# Raspberry_Pi_Circuit_Board.net
KiCad netlist of a schematic drawn in EAGLE
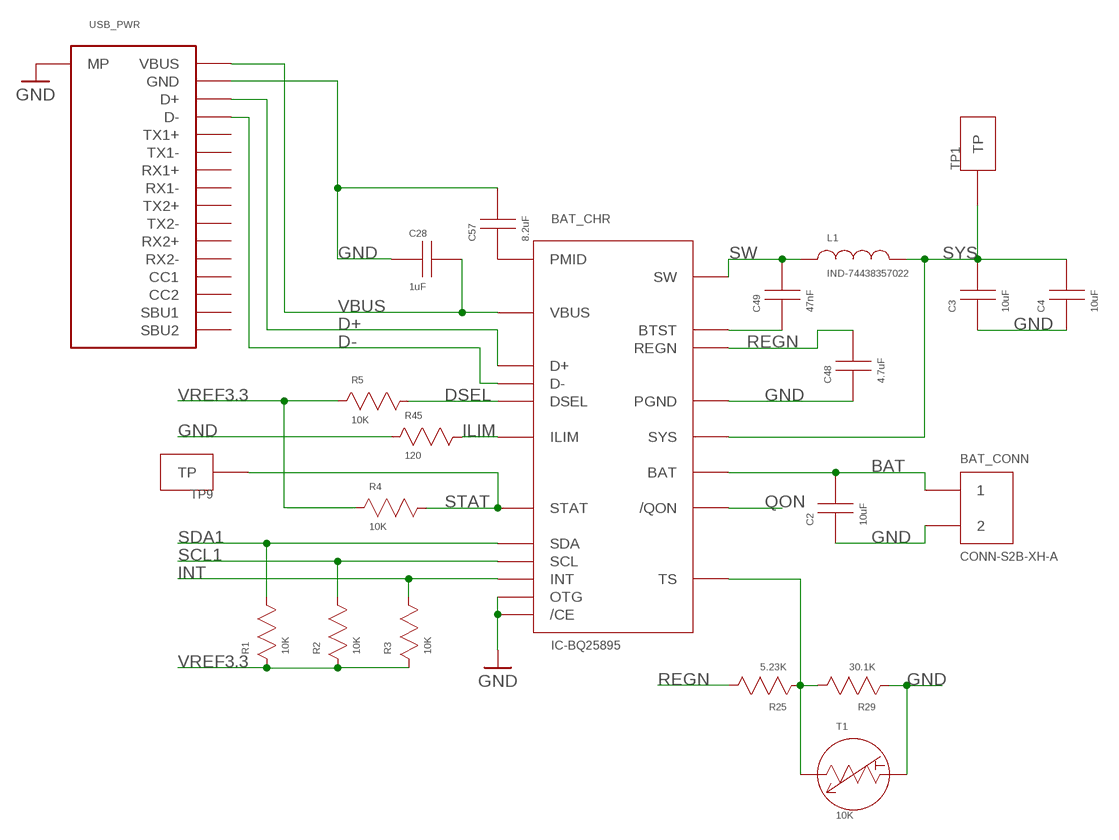
[diagram p0: schematic, sheet 1]
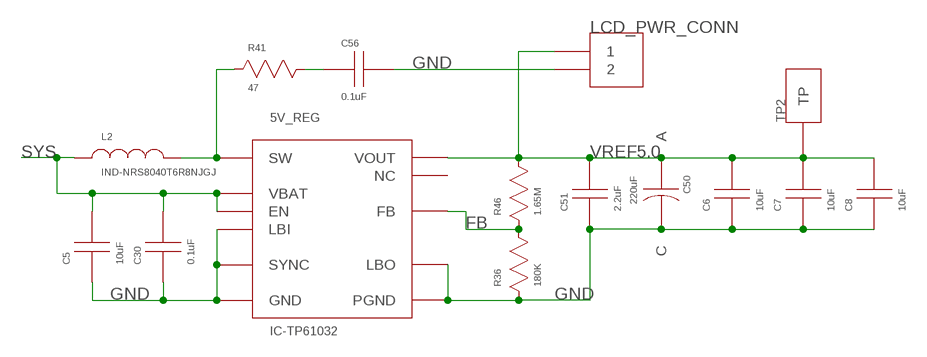
[diagram p1: schematic, sheet 2]
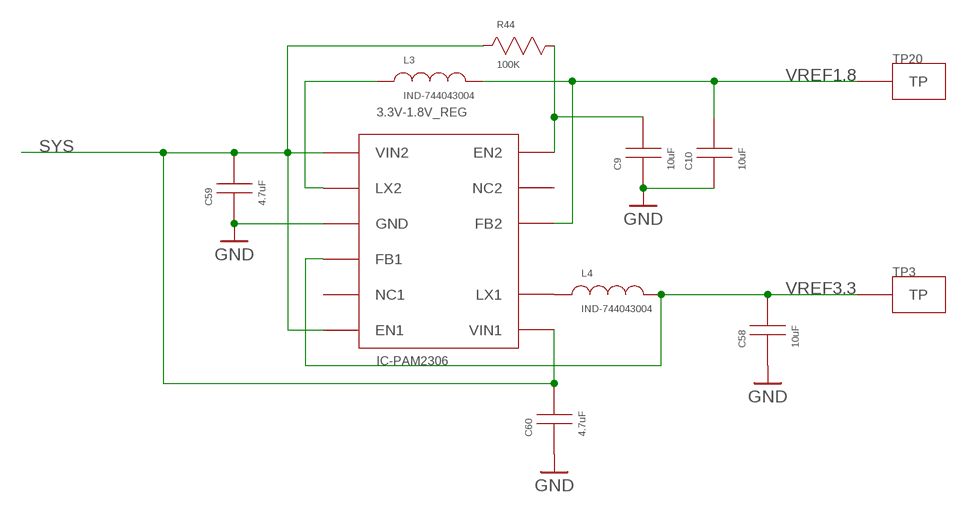
[diagram p2: schematic, sheet 3]
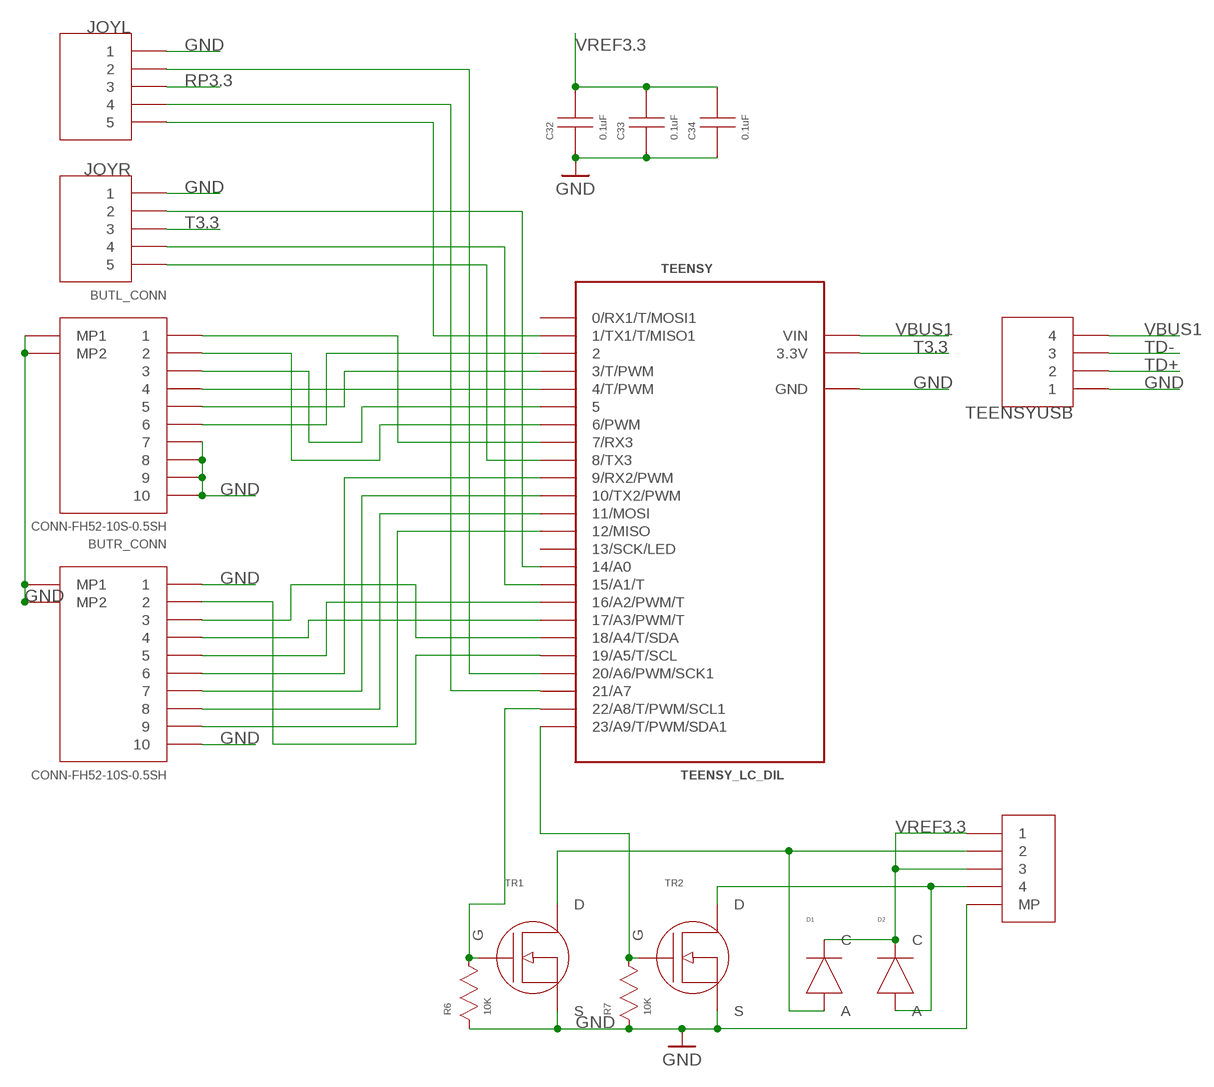
[diagram p3: schematic, sheet 4]
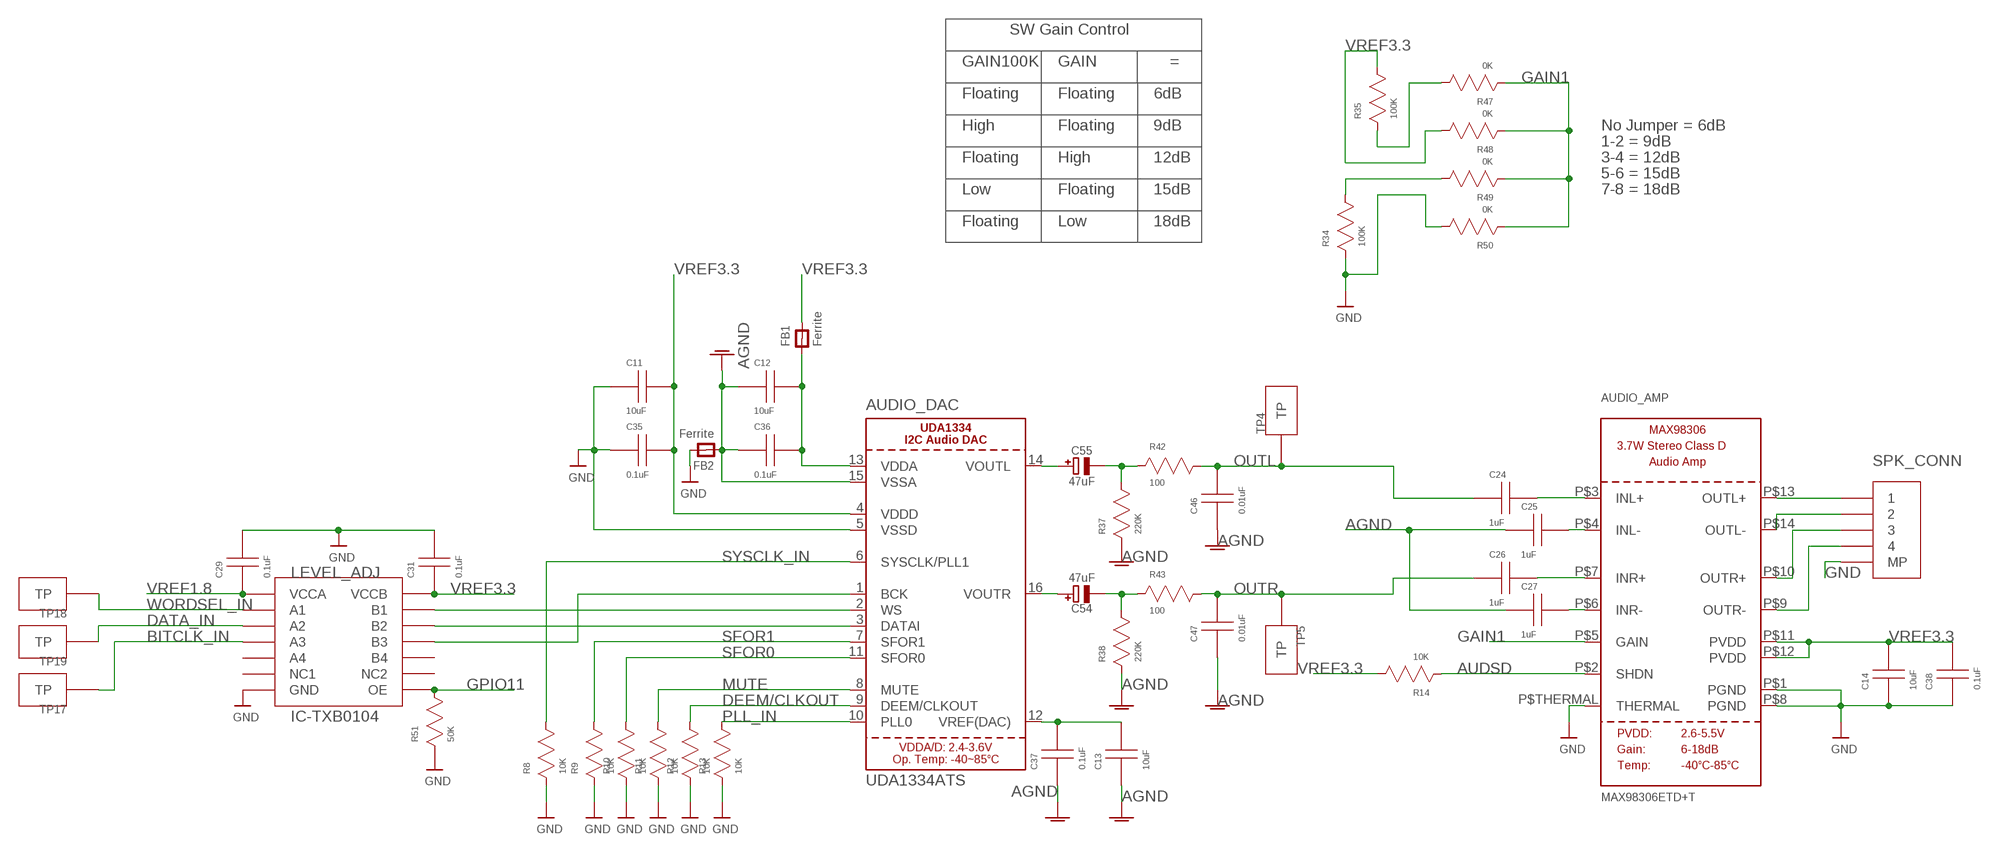
[diagram p4: schematic, sheet 5]
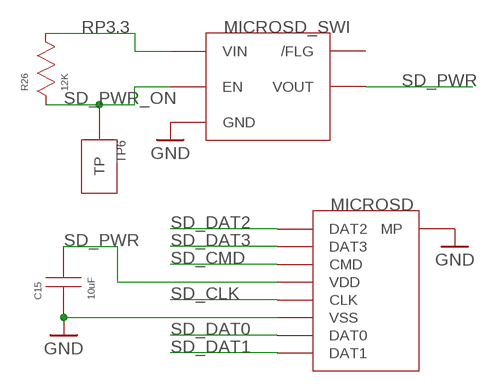
[diagram p5: schematic, sheet 6]
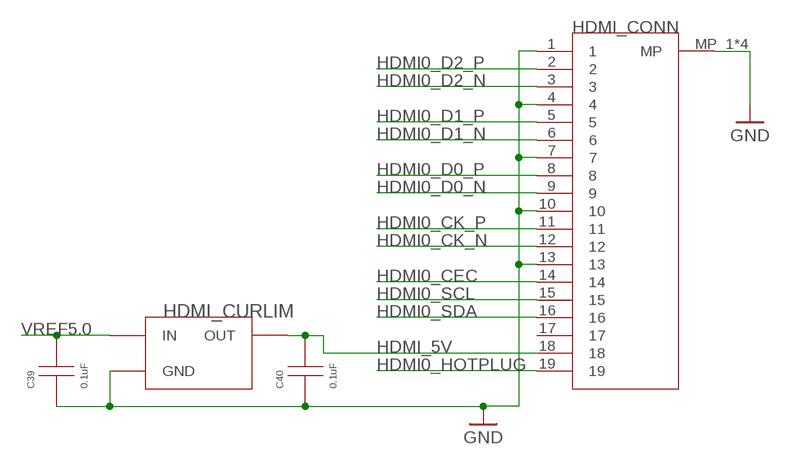
[diagram p6: schematic, sheet 7]
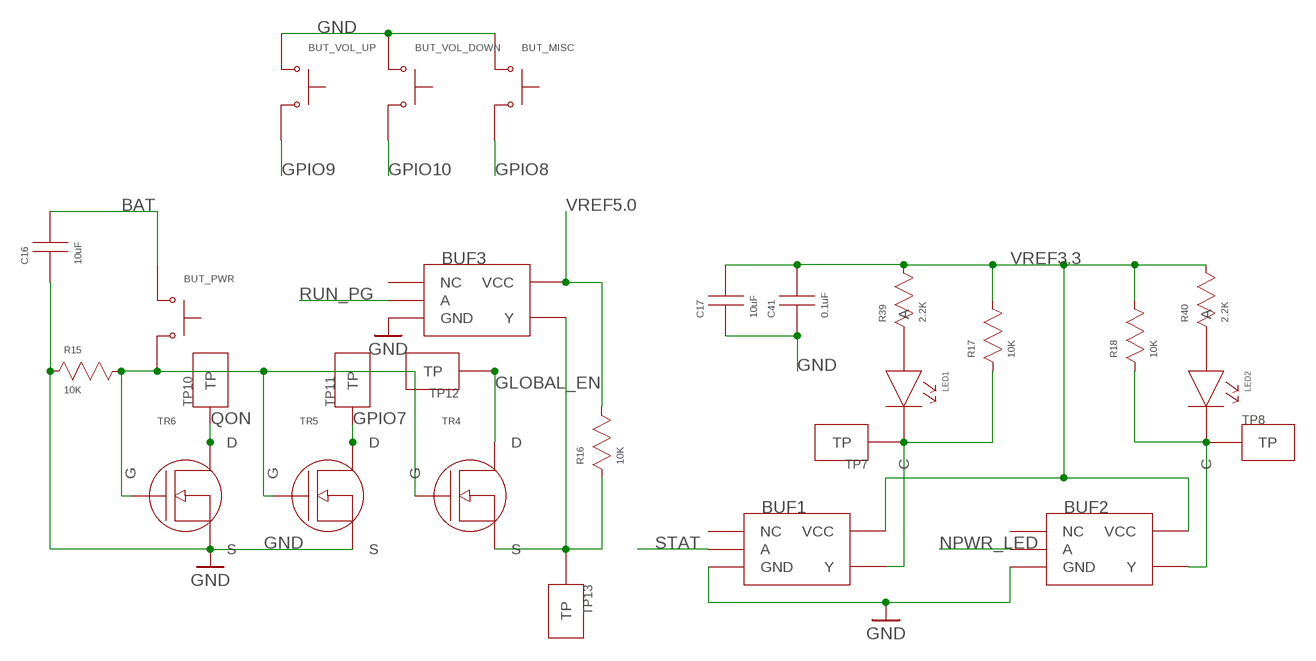
[diagram p7: schematic, sheet 8]
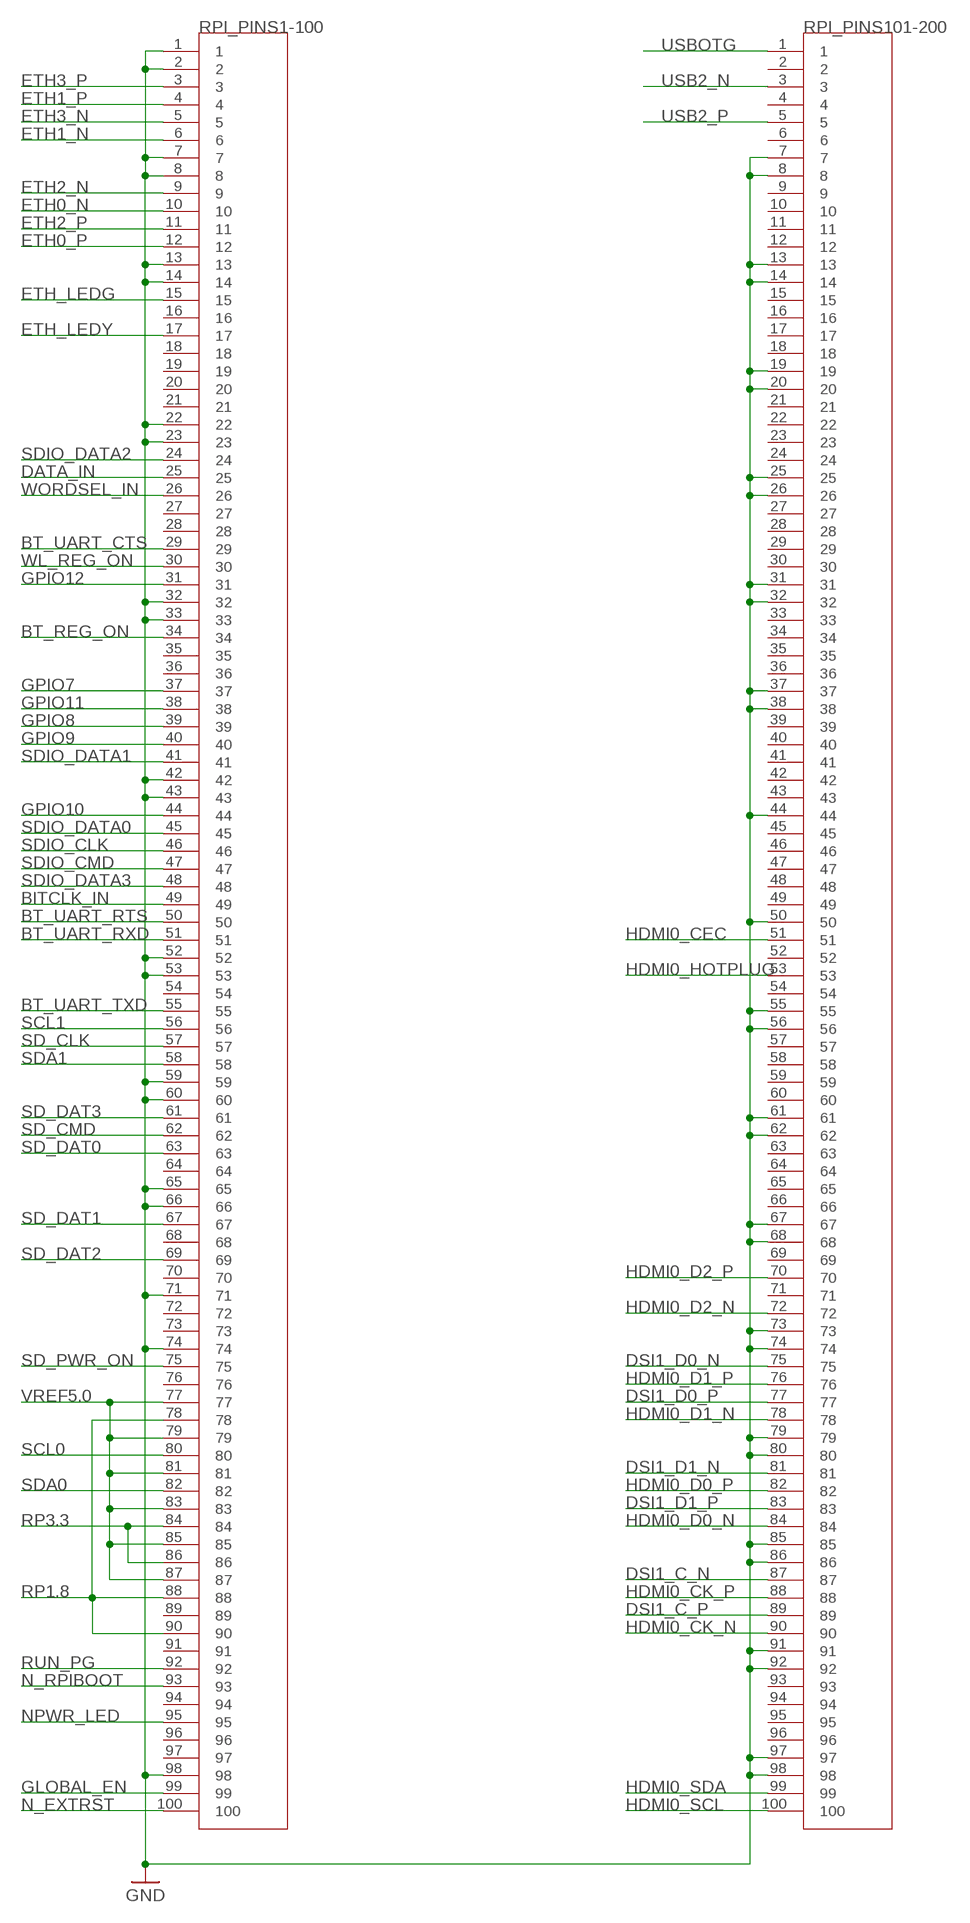
[diagram p8: schematic, sheet 9]
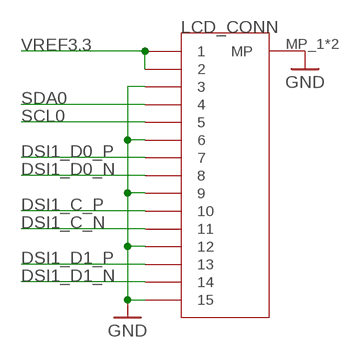
[diagram p9: schematic, sheet 10]
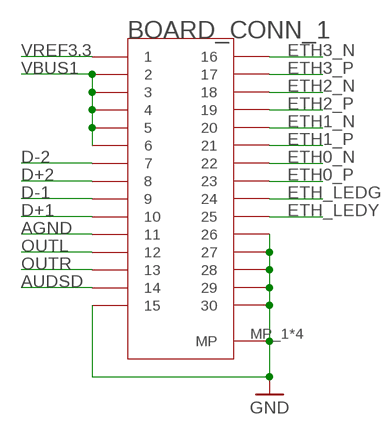
[diagram p10: schematic, sheet 11]
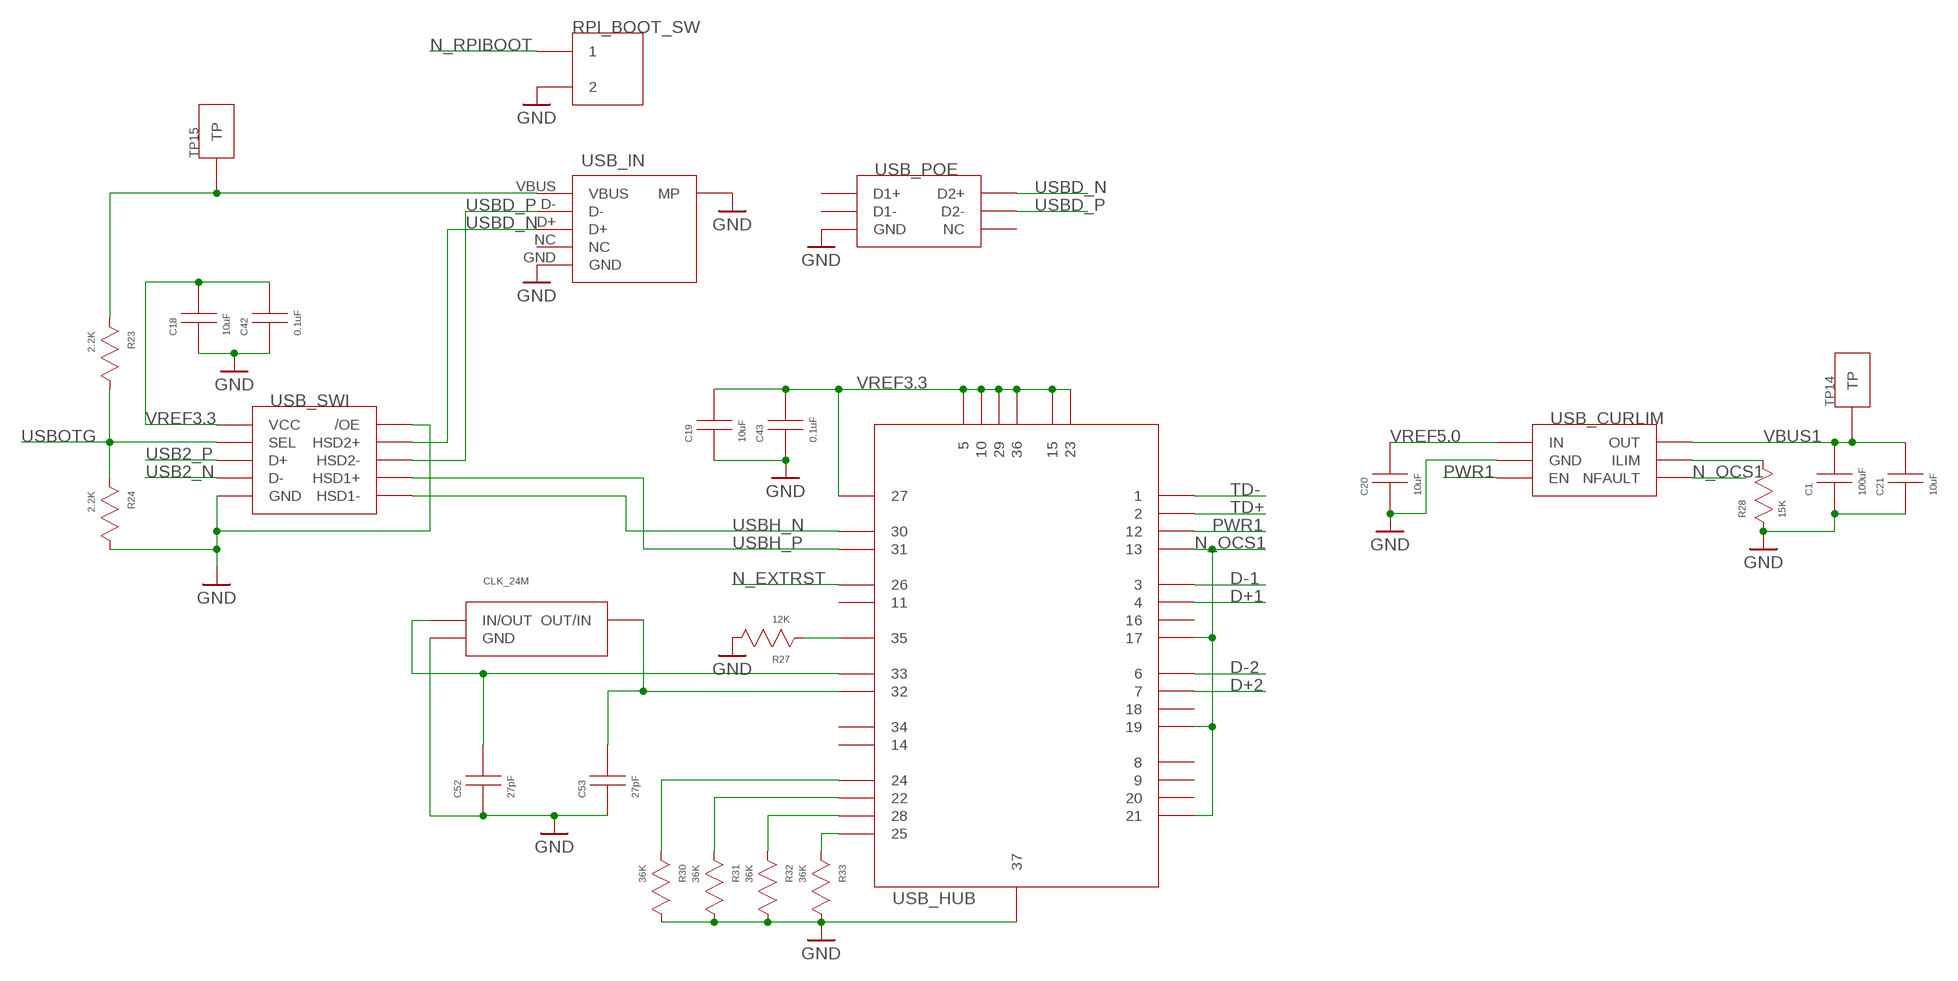
[diagram p11: schematic, sheet 12]
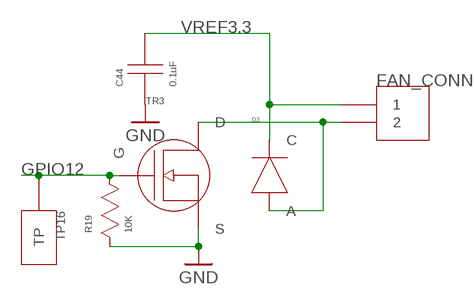
[diagram p12: schematic, sheet 13]
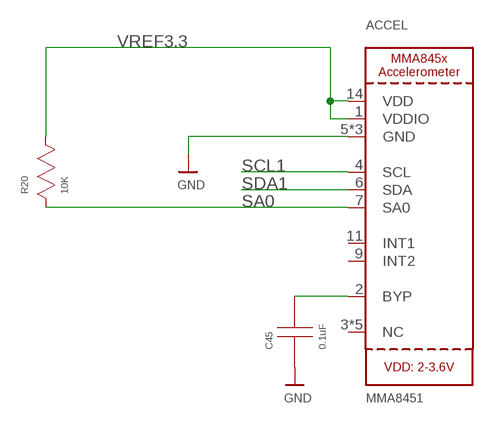
[diagram p13: schematic, sheet 14]
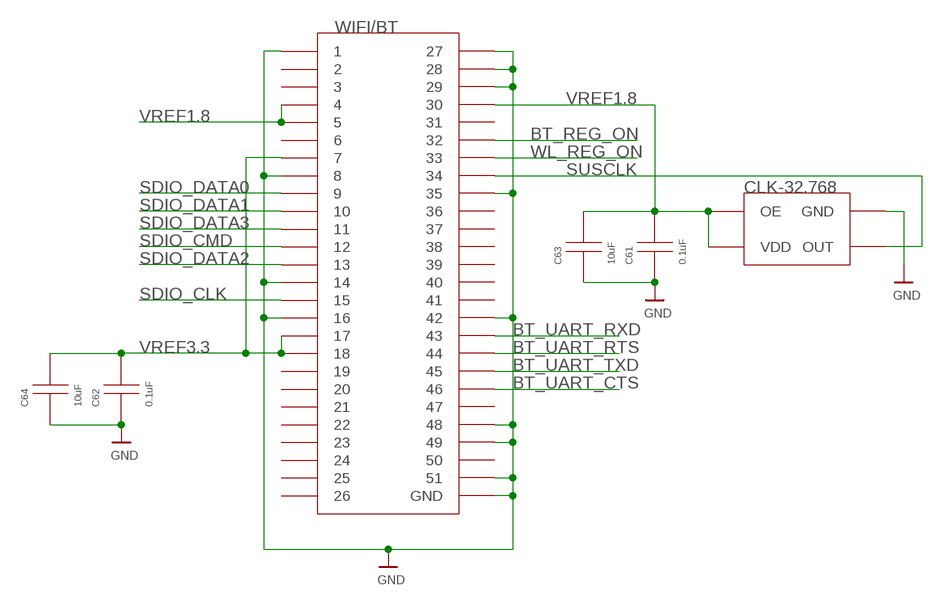
[diagram p14: schematic, sheet 15]

(export (version "E")
  (design (tool "Eeschema 10.0.6"))
  (components
    (comp (ref "C39")
      (value "0.1uF")
      (footprint "eagle-import:CAP-603")
      (libsource (lib "eagle-import") (part "CAP-603"))
    )
    (comp (ref "C40")
      (value "0.1uF")
      (footprint "eagle-import:CAP-603")
      (libsource (lib "eagle-import") (part "CAP-603"))
    )
    (comp (ref "HDMI_CONN")
      (value "HDMI-2001-1-2-21-00-BK")
      (footprint "eagle-import:HDMI-2001-1-2-21-00-BK")
      (libsource (lib "eagle-import") (part "HDMI-2001-1-2-21-00-BK"))
    )
    (comp (ref "HDMI_CURLIM")
      (value "CURLIM-AP2331")
      (footprint "eagle-import:CURLIM-AP2331")
      (libsource (lib "eagle-import") (part "CURLIM-AP2331"))
    )
    (comp (ref "RPI_PINS1-100")
      (value "CONN-DF40_CL0594-5437-8-00_2D")
      (footprint "eagle-import:CONN-DF40_CL0594-5437-8-00_2D")
      (libsource (lib "eagle-import") (part "CONN-DF40_CL0594-5437-8-00_2D"))
    )
    (comp (ref "RPI_PINS101-200")
      (value "CONN-DF40_CL0594-5437-8-00_2D")
      (footprint "eagle-import:CONN-DF40_CL0594-5437-8-00_2D")
      (libsource (lib "eagle-import") (part "CONN-DF40_CL0594-5437-8-00_2D"))
    )
    (comp (ref "BOARD_CONN_1")
      (value "MEZZANINE-AXT630124")
      (footprint "eagle-import:MEZZANINE-AXT630124")
      (libsource (lib "eagle-import") (part "MEZZANINE-AXT630124"))
    )
    (comp (ref "BUF1")
      (value "BUF-74LVC1G07")
      (footprint "eagle-import:BUF-74LVC1G07")
      (libsource (lib "eagle-import") (part "BUF-74LVC1G07"))
    )
    (comp (ref "BUF2")
      (value "BUF-74LVC1G07")
      (footprint "eagle-import:BUF-74LVC1G07")
      (libsource (lib "eagle-import") (part "BUF-74LVC1G07"))
    )
    (comp (ref "BUF3")
      (value "BUF-74LVC1G07")
      (footprint "eagle-import:BUF-74LVC1G07")
      (libsource (lib "eagle-import") (part "BUF-74LVC1G07"))
    )
    (comp (ref "BUT_MISC")
      (value "BUT-KSS331GLFS")
      (footprint "eagle-import:BUT-KSS331GLFS")
      (libsource (lib "eagle-import") (part "BUT-KSS331GLFS"))
    )
    (comp (ref "BUT_PWR")
      (value "BUT-KSS331GLFS")
      (footprint "eagle-import:BUT-KSS331GLFS")
      (libsource (lib "eagle-import") (part "BUT-KSS331GLFS"))
    )
    (comp (ref "BUT_VOL_DOWN")
      (value "BUT-KSS331GLFS")
      (footprint "eagle-import:BUT-KSS331GLFS")
      (libsource (lib "eagle-import") (part "BUT-KSS331GLFS"))
    )
    (comp (ref "BUT_VOL_UP")
      (value "BUT-KSS331GLFS")
      (footprint "eagle-import:BUT-KSS331GLFS")
      (libsource (lib "eagle-import") (part "BUT-KSS331GLFS"))
    )
    (comp (ref "C16")
      (value "10uF")
      (footprint "eagle-import:CAP-603")
      (libsource (lib "eagle-import") (part "Personal_vf.c4yF0r8uTPqxhtoqvO0ekg_CAP-603"))
    )
    (comp (ref "C17")
      (value "10uF")
      (footprint "eagle-import:CAP-603")
      (libsource (lib "eagle-import") (part "Personal_vf.c4yF0r8uTPqxhtoqvO0ekg_CAP-603"))
    )
    (comp (ref "C41")
      (value "0.1uF")
      (footprint "eagle-import:CAP-603")
      (libsource (lib "eagle-import") (part "Personal_vf.c4yF0r8uTPqxhtoqvO0ekg_CAP-603"))
    )
    (comp (ref "LED1")
      (value "LED-SM0805UWC")
      (footprint "eagle-import:LED-SM0805UWC")
      (libsource (lib "eagle-import") (part "LED-SM0805UWC"))
    )
    (comp (ref "LED2")
      (value "LED-SM0805UWC")
      (footprint "eagle-import:LED-SM0805UWC")
      (libsource (lib "eagle-import") (part "LED-SM0805UWC"))
    )
    (comp (ref "R15")
      (value "10K")
      (footprint "eagle-import:RES-603")
      (libsource (lib "eagle-import") (part "Personal_vf.c4yF0r8uTPqxhtoqvO0ekg_RES-603"))
    )
    (comp (ref "R16")
      (value "10K")
      (footprint "eagle-import:RES-603")
      (libsource (lib "eagle-import") (part "Personal_vf.c4yF0r8uTPqxhtoqvO0ekg_RES-603"))
    )
    (comp (ref "R17")
      (value "10K")
      (footprint "eagle-import:RES-603")
      (libsource (lib "eagle-import") (part "RES-603"))
    )
    (comp (ref "R18")
      (value "10K")
      (footprint "eagle-import:RES-603")
      (libsource (lib "eagle-import") (part "RES-603"))
    )
    (comp (ref "R39")
      (value "2.2K")
      (footprint "eagle-import:RES-603")
      (libsource (lib "eagle-import") (part "RES-603"))
    )
    (comp (ref "R40")
      (value "2.2K")
      (footprint "eagle-import:RES-603")
      (libsource (lib "eagle-import") (part "RES-603"))
    )
    (comp (ref "TP7")
      (value "TESTPOINT")
      (footprint "eagle-import:TESTPOINT")
      (libsource (lib "eagle-import") (part "TESTPOINT"))
    )
    (comp (ref "TP8")
      (value "TESTPOINT")
      (footprint "eagle-import:TESTPOINT")
      (libsource (lib "eagle-import") (part "TESTPOINT"))
    )
    (comp (ref "TP10")
      (value "TESTPOINT")
      (footprint "eagle-import:TESTPOINT")
      (libsource (lib "eagle-import") (part "TESTPOINT"))
    )
    (comp (ref "TP11")
      (value "TESTPOINT")
      (footprint "eagle-import:TESTPOINT")
      (libsource (lib "eagle-import") (part "TESTPOINT"))
    )
    (comp (ref "TP12")
      (value "TESTPOINT")
      (footprint "eagle-import:TESTPOINT")
      (libsource (lib "eagle-import") (part "TESTPOINT"))
    )
    (comp (ref "TP13")
      (value "TESTPOINT")
      (footprint "eagle-import:TESTPOINT")
      (libsource (lib "eagle-import") (part "TESTPOINT"))
    )
    (comp (ref "TR4")
      (value "TRAN-DMG2302UKQ")
      (footprint "eagle-import:TRAN-DMG2302UKQ")
      (libsource (lib "eagle-import") (part "TRAN-DMG2302UKQ"))
    )
    (comp (ref "TR5")
      (value "TRAN-DMG2302UKQ")
      (footprint "eagle-import:TRAN-DMG2302UKQ")
      (libsource (lib "eagle-import") (part "TRAN-DMG2302UKQ"))
    )
    (comp (ref "TR6")
      (value "TRAN-DMG2302UKQ")
      (footprint "eagle-import:TRAN-DMG2302UKQ")
      (libsource (lib "eagle-import") (part "TRAN-DMG2302UKQ"))
    )
    (comp (ref "BUTL_CONN")
      (value "CONN-FH52-10S-0.5SH")
      (footprint "eagle-import:CONN-FH52-10S-0.5SH")
      (libsource (lib "eagle-import") (part "CONN-FH52-10S-0.5SH"))
    )
    (comp (ref "BUTR_CONN")
      (value "CONN-FH52-10S-0.5SH")
      (footprint "eagle-import:CONN-FH52-10S-0.5SH")
      (libsource (lib "eagle-import") (part "CONN-FH52-10S-0.5SH"))
    )
    (comp (ref "C32")
      (value "0.1uF")
      (footprint "eagle-import:CAP-603")
      (libsource (lib "eagle-import") (part "CAP-603"))
    )
    (comp (ref "C33")
      (value "0.1uF")
      (footprint "eagle-import:CAP-603")
      (libsource (lib "eagle-import") (part "CAP-603"))
    )
    (comp (ref "C34")
      (value "0.1uF")
      (footprint "eagle-import:CAP-603")
      (libsource (lib "eagle-import") (part "CAP-603"))
    )
    (comp (ref "D1")
      (value "DIODE-X3-WLB1608-2")
      (footprint "eagle-import:DIODE-X3-WLB1608-2")
      (libsource (lib "eagle-import") (part "DIODE-X3-WLB1608-2"))
    )
    (comp (ref "D2")
      (value "DIODE-X3-WLB1608-2")
      (footprint "eagle-import:DIODE-X3-WLB1608-2")
      (libsource (lib "eagle-import") (part "DIODE-X3-WLB1608-2"))
    )
    (comp (ref "JOYL")
      (value "CONN_5PIN")
      (footprint "eagle-import:CONN_5PIN")
      (libsource (lib "eagle-import") (part "CONN_5PIN"))
    )
    (comp (ref "JOYR")
      (value "CONN_5PIN")
      (footprint "eagle-import:CONN_5PIN")
      (libsource (lib "eagle-import") (part "CONN_5PIN"))
    )
    (comp (ref "MOT_CONN")
      (value "CONN-VS4B-ZR-SM4A-TF")
      (footprint "eagle-import:CONN-VS4B-ZR-SM4A-TF")
      (libsource (lib "eagle-import") (part "CONN-VS4B-ZR-SM4A-TF"))
    )
    (comp (ref "R6")
      (value "10K")
      (footprint "eagle-import:RES-603")
      (libsource (lib "eagle-import") (part "Personal_vf.c4yF0r8uTPqxhtoqvO0ekg_RES-603"))
    )
    (comp (ref "R7")
      (value "10K")
      (footprint "eagle-import:RES-603")
      (libsource (lib "eagle-import") (part "Personal_vf.c4yF0r8uTPqxhtoqvO0ekg_RES-603"))
    )
    (comp (ref "TEENSY")
      (value "TEENSY_LC_DIL")
      (footprint "eagle-import:TEENSY_3.0-3.2&LC_DIL")
      (libsource (lib "eagle-import") (part "TEENSY_LC_DIL"))
    )
    (comp (ref "TEENSYUSB")
      (value "CONN_4PIN")
      (footprint "eagle-import:CONN_4PIN")
      (libsource (lib "eagle-import") (part "CONN_4PIN"))
    )
    (comp (ref "TR1")
      (value "TRAN-DMG2302UKQ")
      (footprint "eagle-import:TRAN-DMG2302UKQ")
      (libsource (lib "eagle-import") (part "TRAN-DMG2302UKQ"))
    )
    (comp (ref "TR2")
      (value "TRAN-DMG2302UKQ")
      (footprint "eagle-import:TRAN-DMG2302UKQ")
      (libsource (lib "eagle-import") (part "TRAN-DMG2302UKQ"))
    )
    (comp (ref "3.3V-1.8V_REG")
      (value "IC-PAM2306")
      (footprint "eagle-import:IC-PAM2306")
      (libsource (lib "eagle-import") (part "IC-PAM2306"))
    )
    (comp (ref "C9")
      (value "10uF")
      (footprint "eagle-import:CAP-603")
      (libsource (lib "eagle-import") (part "CAP-603"))
    )
    (comp (ref "C10")
      (value "10uF")
      (footprint "eagle-import:CAP-603")
      (libsource (lib "eagle-import") (part "CAP-603"))
    )
    (comp (ref "C58")
      (value "10uF")
      (footprint "eagle-import:CAP-603")
      (libsource (lib "eagle-import") (part "CAP-603"))
    )
    (comp (ref "C59")
      (value "4.7uF")
      (footprint "eagle-import:CAP-603")
      (libsource (lib "eagle-import") (part "CAP-603"))
    )
    (comp (ref "C60")
      (value "4.7uF")
      (footprint "eagle-import:CAP-603")
      (libsource (lib "eagle-import") (part "CAP-603"))
    )
    (comp (ref "L3")
      (value "IND-744043004")
      (footprint "eagle-import:IND-744043004")
      (libsource (lib "eagle-import") (part "IND-744043004"))
    )
    (comp (ref "L4")
      (value "IND-744043004")
      (footprint "eagle-import:IND-744043004")
      (libsource (lib "eagle-import") (part "IND-744043004"))
    )
    (comp (ref "R44")
      (value "100K")
      (footprint "eagle-import:RES-603")
      (libsource (lib "eagle-import") (part "RES-603"))
    )
    (comp (ref "TP3")
      (value "TESTPOINT")
      (footprint "eagle-import:TESTPOINT")
      (libsource (lib "eagle-import") (part "TESTPOINT"))
    )
    (comp (ref "TP20")
      (value "TESTPOINT")
      (footprint "eagle-import:TESTPOINT")
      (libsource (lib "eagle-import") (part "TESTPOINT"))
    )
    (comp (ref "BAT_CHR")
      (value "IC-BQ25895")
      (footprint "eagle-import:IC-BQ25895")
      (libsource (lib "eagle-import") (part "IC-BQ25895"))
    )
    (comp (ref "BAT_CONN")
      (value "CONN-S2B-XH-A")
      (footprint "eagle-import:CONN-S2B-XH-A")
      (libsource (lib "eagle-import") (part "CONN-S2B-XH-A"))
    )
    (comp (ref "C2")
      (value "10uF")
      (footprint "eagle-import:CAP-603")
      (libsource (lib "eagle-import") (part "CAP-603"))
    )
    (comp (ref "C3")
      (value "10uF")
      (footprint "eagle-import:CAP-603")
      (libsource (lib "eagle-import") (part "CAP-603"))
    )
    (comp (ref "C4")
      (value "10uF")
      (footprint "eagle-import:CAP-603")
      (libsource (lib "eagle-import") (part "CAP-603"))
    )
    (comp (ref "C28")
      (value "1uF")
      (footprint "eagle-import:CAP-603")
      (libsource (lib "eagle-import") (part "CAP-603"))
    )
    (comp (ref "C48")
      (value "4.7uF")
      (footprint "eagle-import:CAP-603")
      (libsource (lib "eagle-import") (part "CAP-603"))
    )
    (comp (ref "C49")
      (value "47nF")
      (footprint "eagle-import:CAP-603")
      (libsource (lib "eagle-import") (part "CAP-603"))
    )
    (comp (ref "C57")
      (value "8.2uF")
      (footprint "eagle-import:CAP-603")
      (libsource (lib "eagle-import") (part "CAP-603"))
    )
    (comp (ref "L1")
      (value "IND-74438357022")
      (footprint "eagle-import:IND-74438357022")
      (libsource (lib "eagle-import") (part "IND-74438357022"))
    )
    (comp (ref "R1")
      (value "10K")
      (footprint "eagle-import:RES-603")
      (libsource (lib "eagle-import") (part "RES-603"))
    )
    (comp (ref "R2")
      (value "10K")
      (footprint "eagle-import:RES-603")
      (libsource (lib "eagle-import") (part "RES-603"))
    )
    (comp (ref "R3")
      (value "10K")
      (footprint "eagle-import:RES-603")
      (libsource (lib "eagle-import") (part "RES-603"))
    )
    (comp (ref "R4")
      (value "10K")
      (footprint "eagle-import:RES-603")
      (libsource (lib "eagle-import") (part "RES-603"))
    )
    (comp (ref "R5")
      (value "10K")
      (footprint "eagle-import:RES-603")
      (libsource (lib "eagle-import") (part "RES-603"))
    )
    (comp (ref "R25")
      (value "5.23K")
      (footprint "eagle-import:RES-603")
      (libsource (lib "eagle-import") (part "RES-603"))
    )
    (comp (ref "R29")
      (value "30.1K")
      (footprint "eagle-import:RES-603")
      (libsource (lib "eagle-import") (part "RES-603"))
    )
    (comp (ref "R45")
      (value "120")
      (footprint "eagle-import:RES-603")
      (libsource (lib "eagle-import") (part "RES-603"))
    )
    (comp (ref "T1")
      (value "10K")
      (footprint "eagle-import:THERM-NTCLE101E3C90173")
      (libsource (lib "eagle-import") (part "THERM-NTCLE101E3C90173"))
    )
    (comp (ref "TP1")
      (value "TESTPOINT")
      (footprint "eagle-import:TESTPOINT")
      (libsource (lib "eagle-import") (part "TESTPOINT"))
    )
    (comp (ref "TP9")
      (value "TESTPOINT")
      (footprint "eagle-import:TESTPOINT")
      (libsource (lib "eagle-import") (part "TESTPOINT"))
    )
    (comp (ref "USB_PWR")
      (value "USBC-USB-C31-S-RA-CS1D-BK-T/R")
      (footprint "eagle-import:USBC-USB-C31-S-RA-CS1D-BK-T_R")
      (libsource (lib "eagle-import") (part "USBC-USB-C31-S-RA-CS1D-BK-T/R"))
    )
    (comp (ref "LCD_CONN")
      (value "FPC-1-84952-5")
      (footprint "eagle-import:FPC-1-84952-5")
      (libsource (lib "eagle-import") (part "FPC-1-84952-5"))
    )
    (comp (ref "ACCEL")
      (value "MMA8451")
      (footprint "eagle-import:MMA845X_QFN_16MM")
      (libsource (lib "eagle-import") (part "ACCEL_MMA845X"))
    )
    (comp (ref "C45")
      (value "0.1uF")
      (footprint "eagle-import:CAP-603")
      (libsource (lib "eagle-import") (part "Personal_vf.c4yF0r8uTPqxhtoqvO0ekg_CAP-603"))
    )
    (comp (ref "R20")
      (value "10K")
      (footprint "eagle-import:RES-603")
      (libsource (lib "eagle-import") (part "Personal_vf.c4yF0r8uTPqxhtoqvO0ekg_RES-603"))
    )
    (comp (ref "C44")
      (value "0.1uF")
      (footprint "eagle-import:CAP-603")
      (libsource (lib "eagle-import") (part "Personal_vf.c4yF0r8uTPqxhtoqvO0ekg_CAP-603"))
    )
    (comp (ref "D3")
      (value "DIODE-X3-WLB1608-2")
      (footprint "eagle-import:DIODE-X3-WLB1608-2")
      (libsource (lib "eagle-import") (part "DIODE-X3-WLB1608-2"))
    )
    (comp (ref "FAN_CONN")
      (value "CONN-282834-2")
      (footprint "eagle-import:CONN-282834-2")
      (libsource (lib "eagle-import") (part "CONN-282834-2"))
    )
    (comp (ref "R19")
      (value "10K")
      (footprint "eagle-import:RES-603")
      (libsource (lib "eagle-import") (part "Personal_vf.c4yF0r8uTPqxhtoqvO0ekg_RES-603"))
    )
    (comp (ref "TP16")
      (value "TESTPOINT")
      (footprint "eagle-import:TESTPOINT")
      (libsource (lib "eagle-import") (part "TESTPOINT"))
    )
    (comp (ref "TR3")
      (value "TRAN-DMG2302UKQ")
      (footprint "eagle-import:TRAN-DMG2302UKQ")
      (libsource (lib "eagle-import") (part "TRAN-DMG2302UKQ"))
    )
    (comp (ref "AUDIO_AMP")
      (value "MAX98306ETD+T")
      (footprint "eagle-import:TDFN14_3X3MM")
      (libsource (lib "eagle-import") (part "AUDIOAMP_MAX98306"))
    )
    (comp (ref "AUDIO_DAC")
      (value "UDA1334ATS")
      (footprint "eagle-import:SSOP16_4.4MM")
      (libsource (lib "eagle-import") (part "AUDIO_I2S_UDA1334{dblquote}{dblquote}"))
    )
    (comp (ref "C11")
      (value "10uF")
      (footprint "eagle-import:CAP-603")
      (libsource (lib "eagle-import") (part "Personal_vf.c4yF0r8uTPqxhtoqvO0ekg_CAP-603"))
    )
    (comp (ref "C12")
      (value "10uF")
      (footprint "eagle-import:CAP-603")
      (libsource (lib "eagle-import") (part "Personal_vf.c4yF0r8uTPqxhtoqvO0ekg_CAP-603"))
    )
    (comp (ref "C13")
      (value "10uF")
      (footprint "eagle-import:CAP-603")
      (libsource (lib "eagle-import") (part "Personal_vf.c4yF0r8uTPqxhtoqvO0ekg_CAP-603"))
    )
    (comp (ref "C14")
      (value "10uF")
      (footprint "eagle-import:CAP-603")
      (libsource (lib "eagle-import") (part "Personal_vf.c4yF0r8uTPqxhtoqvO0ekg_CAP-603"))
    )
    (comp (ref "C24")
      (value "1uF")
      (footprint "eagle-import:CAP-603")
      (libsource (lib "eagle-import") (part "Personal_vf.c4yF0r8uTPqxhtoqvO0ekg_CAP-603"))
    )
    (comp (ref "C25")
      (value "1uF")
      (footprint "eagle-import:CAP-603")
      (libsource (lib "eagle-import") (part "Personal_vf.c4yF0r8uTPqxhtoqvO0ekg_CAP-603"))
    )
    (comp (ref "C26")
      (value "1uF")
      (footprint "eagle-import:CAP-603")
      (libsource (lib "eagle-import") (part "Personal_vf.c4yF0r8uTPqxhtoqvO0ekg_CAP-603"))
    )
    (comp (ref "C27")
      (value "1uF")
      (footprint "eagle-import:CAP-603")
      (libsource (lib "eagle-import") (part "Personal_vf.c4yF0r8uTPqxhtoqvO0ekg_CAP-603"))
    )
    (comp (ref "C29")
      (value "0.1uF")
      (footprint "eagle-import:CAP-603")
      (libsource (lib "eagle-import") (part "Personal_vf.c4yF0r8uTPqxhtoqvO0ekg_CAP-603"))
    )
    (comp (ref "C31")
      (value "0.1uF")
      (footprint "eagle-import:CAP-603")
      (libsource (lib "eagle-import") (part "Personal_vf.c4yF0r8uTPqxhtoqvO0ekg_CAP-603"))
    )
    (comp (ref "C35")
      (value "0.1uF")
      (footprint "eagle-import:CAP-603")
      (libsource (lib "eagle-import") (part "Personal_vf.c4yF0r8uTPqxhtoqvO0ekg_CAP-603"))
    )
    (comp (ref "C36")
      (value "0.1uF")
      (footprint "eagle-import:CAP-603")
      (libsource (lib "eagle-import") (part "Personal_vf.c4yF0r8uTPqxhtoqvO0ekg_CAP-603"))
    )
    (comp (ref "C37")
      (value "0.1uF")
      (footprint "eagle-import:CAP-603")
      (libsource (lib "eagle-import") (part "Personal_vf.c4yF0r8uTPqxhtoqvO0ekg_CAP-603"))
    )
    (comp (ref "C38")
      (value "0.1uF")
      (footprint "eagle-import:CAP-603")
      (libsource (lib "eagle-import") (part "Personal_vf.c4yF0r8uTPqxhtoqvO0ekg_CAP-603"))
    )
    (comp (ref "C46")
      (value "0.01uF")
      (footprint "eagle-import:CAP-603")
      (libsource (lib "eagle-import") (part "Personal_vf.c4yF0r8uTPqxhtoqvO0ekg_CAP-603"))
    )
    (comp (ref "C47")
      (value "0.01uF")
      (footprint "eagle-import:CAP-603")
      (libsource (lib "eagle-import") (part "Personal_vf.c4yF0r8uTPqxhtoqvO0ekg_CAP-603"))
    )
    (comp (ref "C54")
      (value "47uF")
      (footprint "eagle-import:PANASONIC_C")
      (libsource (lib "eagle-import") (part "CAP_ELECTROLYTICPANASONIC_C"))
    )
    (comp (ref "C55")
      (value "47uF")
      (footprint "eagle-import:PANASONIC_C")
      (libsource (lib "eagle-import") (part "CAP_ELECTROLYTICPANASONIC_C"))
    )
    (comp (ref "FB1")
      (value "Ferrite")
      (footprint "eagle-import:0805@1")
      (libsource (lib "eagle-import") (part "FERRITE0805"))
    )
    (comp (ref "FB2")
      (value "Ferrite")
      (footprint "eagle-import:0805@1")
      (libsource (lib "eagle-import") (part "FERRITE0805"))
    )
    (comp (ref "LEVEL_ADJ")
      (value "IC-TXB0104")
      (footprint "eagle-import:IC-TXB0104")
      (libsource (lib "eagle-import") (part "IC-TXB0104"))
    )
    (comp (ref "R8")
      (value "10K")
      (footprint "eagle-import:RES-603")
      (libsource (lib "eagle-import") (part "Personal_vf.c4yF0r8uTPqxhtoqvO0ekg_RES-603"))
    )
    (comp (ref "R9")
      (value "10K")
      (footprint "eagle-import:RES-603")
      (libsource (lib "eagle-import") (part "Personal_vf.c4yF0r8uTPqxhtoqvO0ekg_RES-603"))
    )
    (comp (ref "R10")
      (value "10K")
      (footprint "eagle-import:RES-603")
      (libsource (lib "eagle-import") (part "Personal_vf.c4yF0r8uTPqxhtoqvO0ekg_RES-603"))
    )
    (comp (ref "R11")
      (value "10K")
      (footprint "eagle-import:RES-603")
      (libsource (lib "eagle-import") (part "Personal_vf.c4yF0r8uTPqxhtoqvO0ekg_RES-603"))
    )
    (comp (ref "R12")
      (value "10K")
      (footprint "eagle-import:RES-603")
      (libsource (lib "eagle-import") (part "Personal_vf.c4yF0r8uTPqxhtoqvO0ekg_RES-603"))
    )
    (comp (ref "R13")
      (value "10K")
      (footprint "eagle-import:RES-603")
      (libsource (lib "eagle-import") (part "Personal_vf.c4yF0r8uTPqxhtoqvO0ekg_RES-603"))
    )
    (comp (ref "R14")
      (value "10K")
      (footprint "eagle-import:RES-603")
      (libsource (lib "eagle-import") (part "Personal_vf.c4yF0r8uTPqxhtoqvO0ekg_RES-603"))
    )
    (comp (ref "R34")
      (value "100K")
      (footprint "eagle-import:RES-603")
      (libsource (lib "eagle-import") (part "Personal_vf.c4yF0r8uTPqxhtoqvO0ekg_RES-603"))
    )
    (comp (ref "R35")
      (value "100K")
      (footprint "eagle-import:RES-603")
      (libsource (lib "eagle-import") (part "Personal_vf.c4yF0r8uTPqxhtoqvO0ekg_RES-603"))
    )
    (comp (ref "R37")
      (value "220K")
      (footprint "eagle-import:RES-603")
      (libsource (lib "eagle-import") (part "Personal_vf.c4yF0r8uTPqxhtoqvO0ekg_RES-603"))
    )
    (comp (ref "R38")
      (value "220K")
      (footprint "eagle-import:RES-603")
      (libsource (lib "eagle-import") (part "Personal_vf.c4yF0r8uTPqxhtoqvO0ekg_RES-603"))
    )
    (comp (ref "R42")
      (value "100")
      (footprint "eagle-import:RES-603")
      (libsource (lib "eagle-import") (part "Personal_vf.c4yF0r8uTPqxhtoqvO0ekg_RES-603"))
    )
    (comp (ref "R43")
      (value "100")
      (footprint "eagle-import:RES-603")
      (libsource (lib "eagle-import") (part "Personal_vf.c4yF0r8uTPqxhtoqvO0ekg_RES-603"))
    )
    (comp (ref "R47")
      (value "0K")
      (footprint "eagle-import:RES-603")
      (libsource (lib "eagle-import") (part "Personal_vf.c4yF0r8uTPqxhtoqvO0ekg_RES-603"))
    )
    (comp (ref "R48")
      (value "0K")
      (footprint "eagle-import:RES-603")
      (libsource (lib "eagle-import") (part "Personal_vf.c4yF0r8uTPqxhtoqvO0ekg_RES-603"))
    )
    (comp (ref "R49")
      (value "0K")
      (footprint "eagle-import:RES-603")
      (libsource (lib "eagle-import") (part "Personal_vf.c4yF0r8uTPqxhtoqvO0ekg_RES-603"))
    )
    (comp (ref "R50")
      (value "0K")
      (footprint "eagle-import:RES-603")
      (libsource (lib "eagle-import") (part "Personal_vf.c4yF0r8uTPqxhtoqvO0ekg_RES-603"))
    )
    (comp (ref "R51")
      (value "50K")
      (footprint "eagle-import:RES-603")
      (libsource (lib "eagle-import") (part "Personal_vf.c4yF0r8uTPqxhtoqvO0ekg_RES-603"))
    )
    (comp (ref "SPK_CONN")
      (value "CONN-VS4B-ZR-SM4A-TF")
      (footprint "eagle-import:CONN-VS4B-ZR-SM4A-TF")
      (libsource (lib "eagle-import") (part "CONN-VS4B-ZR-SM4A-TF"))
    )
    (comp (ref "TP4")
      (value "TESTPOINT")
      (footprint "eagle-import:TESTPOINT")
      (libsource (lib "eagle-import") (part "TESTPOINT"))
    )
    (comp (ref "TP5")
      (value "TESTPOINT")
      (footprint "eagle-import:TESTPOINT")
      (libsource (lib "eagle-import") (part "TESTPOINT"))
    )
    (comp (ref "TP17")
      (value "TESTPOINT")
      (footprint "eagle-import:TESTPOINT")
      (libsource (lib "eagle-import") (part "TESTPOINT"))
    )
    (comp (ref "TP18")
      (value "TESTPOINT")
      (footprint "eagle-import:TESTPOINT")
      (libsource (lib "eagle-import") (part "TESTPOINT"))
    )
    (comp (ref "TP19")
      (value "TESTPOINT")
      (footprint "eagle-import:TESTPOINT")
      (libsource (lib "eagle-import") (part "TESTPOINT"))
    )
    (comp (ref "C15")
      (value "10uF")
      (footprint "eagle-import:CAP-603")
      (libsource (lib "eagle-import") (part "CAP-603"))
    )
    (comp (ref "MICROSD")
      (value "MICROSD-5033981892_SD")
      (footprint "eagle-import:MICROSD-5033981892_SD")
      (libsource (lib "eagle-import") (part "MICROSD-5033981892_SD"))
    )
    (comp (ref "MICROSD_SWI")
      (value "IC-RT9742")
      (footprint "eagle-import:IC-RT9742")
      (libsource (lib "eagle-import") (part "IC-RT9742"))
    )
    (comp (ref "R26")
      (value "12K")
      (footprint "eagle-import:RES-603")
      (libsource (lib "eagle-import") (part "Personal_vf.c4yF0r8uTPqxhtoqvO0ekg_RES-603"))
    )
    (comp (ref "TP6")
      (value "TESTPOINT")
      (footprint "eagle-import:TESTPOINT")
      (libsource (lib "eagle-import") (part "TESTPOINT"))
    )
    (comp (ref "C1")
      (value "100uF")
      (footprint "eagle-import:CAP-603")
      (libsource (lib "eagle-import") (part "Personal_vf.c4yF0r8uTPqxhtoqvO0ekg_CAP-603"))
    )
    (comp (ref "C18")
      (value "10uF")
      (footprint "eagle-import:CAP-603")
      (libsource (lib "eagle-import") (part "Personal_vf.c4yF0r8uTPqxhtoqvO0ekg_CAP-603"))
    )
    (comp (ref "C19")
      (value "10uF")
      (footprint "eagle-import:CAP-603")
      (libsource (lib "eagle-import") (part "Personal_vf.c4yF0r8uTPqxhtoqvO0ekg_CAP-603"))
    )
    (comp (ref "C20")
      (value "10uF")
      (footprint "eagle-import:CAP-603")
      (libsource (lib "eagle-import") (part "Personal_vf.c4yF0r8uTPqxhtoqvO0ekg_CAP-603"))
    )
    (comp (ref "C21")
      (value "10uF")
      (footprint "eagle-import:CAP-603")
      (libsource (lib "eagle-import") (part "Personal_vf.c4yF0r8uTPqxhtoqvO0ekg_CAP-603"))
    )
    (comp (ref "C42")
      (value "0.1uF")
      (footprint "eagle-import:CAP-603")
      (libsource (lib "eagle-import") (part "Personal_vf.c4yF0r8uTPqxhtoqvO0ekg_CAP-603"))
    )
    (comp (ref "C43")
      (value "0.1uF")
      (footprint "eagle-import:CAP-603")
      (libsource (lib "eagle-import") (part "Personal_vf.c4yF0r8uTPqxhtoqvO0ekg_CAP-603"))
    )
    (comp (ref "C52")
      (value "27pF")
      (footprint "eagle-import:CAP-603")
      (libsource (lib "eagle-import") (part "Personal_vf.c4yF0r8uTPqxhtoqvO0ekg_CAP-603"))
    )
    (comp (ref "C53")
      (value "27pF")
      (footprint "eagle-import:CAP-603")
      (libsource (lib "eagle-import") (part "Personal_vf.c4yF0r8uTPqxhtoqvO0ekg_CAP-603"))
    )
    (comp (ref "CLK_24M")
      (value "CLK-ECS-240")
      (footprint "eagle-import:CLK-ECS-240")
      (libsource (lib "eagle-import") (part "CLK-ECS-240"))
    )
    (comp (ref "R23")
      (value "2.2K")
      (footprint "eagle-import:RES-603")
      (libsource (lib "eagle-import") (part "RES-603"))
    )
    (comp (ref "R24")
      (value "2.2K")
      (footprint "eagle-import:RES-603")
      (libsource (lib "eagle-import") (part "RES-603"))
    )
    (comp (ref "R27")
      (value "12K")
      (footprint "eagle-import:RES-603")
      (libsource (lib "eagle-import") (part "RES-603"))
    )
    (comp (ref "R28")
      (value "15K")
      (footprint "eagle-import:RES-603")
      (libsource (lib "eagle-import") (part "RES-603"))
    )
    (comp (ref "R30")
      (value "36K")
      (footprint "eagle-import:RES-603")
      (libsource (lib "eagle-import") (part "RES-603"))
    )
    (comp (ref "R31")
      (value "36K")
      (footprint "eagle-import:RES-603")
      (libsource (lib "eagle-import") (part "RES-603"))
    )
    (comp (ref "R32")
      (value "36K")
      (footprint "eagle-import:RES-603")
      (libsource (lib "eagle-import") (part "RES-603"))
    )
    (comp (ref "R33")
      (value "36K")
      (footprint "eagle-import:RES-603")
      (libsource (lib "eagle-import") (part "RES-603"))
    )
    (comp (ref "RPI_BOOT_SW")
      (value "DIP-A6TN-1104")
      (footprint "eagle-import:DIP-A6TN-1104")
      (libsource (lib "eagle-import") (part "DIP-A6TN-1104"))
    )
    (comp (ref "TP14")
      (value "TESTPOINT")
      (footprint "eagle-import:TESTPOINT")
      (libsource (lib "eagle-import") (part "TESTPOINT"))
    )
    (comp (ref "TP15")
      (value "TESTPOINT")
      (footprint "eagle-import:TESTPOINT")
      (libsource (lib "eagle-import") (part "TESTPOINT"))
    )
    (comp (ref "USB_CURLIM")
      (value "CURLIM-AP22653W6")
      (footprint "eagle-import:CURLIM-AP22653W6")
      (libsource (lib "eagle-import") (part "CURLIM-AP22653W6"))
    )
    (comp (ref "USB_HUB")
      (value "USBPORT-USB2514BT-I/M2")
      (footprint "eagle-import:USBPORT-USB2514BT-I_M2")
      (libsource (lib "eagle-import") (part "USBPORT-USB2514BT-I/M2"))
    )
    (comp (ref "USB_IN")
      (value "USB-USB3131-30-0230-A")
      (footprint "eagle-import:USB-USB3131-30-0230-A")
      (libsource (lib "eagle-import") (part "USB-USB3131-30-0230-A"))
    )
    (comp (ref "USB_POE")
      (value "POE_PROT-TPD4EUSB30DQAR")
      (footprint "eagle-import:POE_PROT-TPD4EUSB30DQAR")
      (libsource (lib "eagle-import") (part "POE_PROT-TPD4EUSB30DQAR"))
    )
    (comp (ref "USB_SWI")
      (value "USB_SWITCH-FSUSB42-D")
      (footprint "eagle-import:USB_SWITCH-FSUSB42-D")
      (libsource (lib "eagle-import") (part "USB_SWITCH-FSUSB42-D"))
    )
    (comp (ref "5V_REG")
      (value "IC-TP61032")
      (footprint "eagle-import:IC-TPS61032")
      (libsource (lib "eagle-import") (part "IC-TP61032"))
    )
    (comp (ref "C5")
      (value "10uF")
      (footprint "eagle-import:CAP-603")
      (libsource (lib "eagle-import") (part "CAP-603"))
    )
    (comp (ref "C6")
      (value "10uF")
      (footprint "eagle-import:CAP-603")
      (libsource (lib "eagle-import") (part "Personal_vf.c4yF0r8uTPqxhtoqvO0ekg_CAP-603"))
    )
    (comp (ref "C7")
      (value "10uF")
      (footprint "eagle-import:CAP-603")
      (libsource (lib "eagle-import") (part "Personal_vf.c4yF0r8uTPqxhtoqvO0ekg_CAP-603"))
    )
    (comp (ref "C8")
      (value "10uF")
      (footprint "eagle-import:CAP-603")
      (libsource (lib "eagle-import") (part "Personal_vf.c4yF0r8uTPqxhtoqvO0ekg_CAP-603"))
    )
    (comp (ref "C30")
      (value "0.1uF")
      (footprint "eagle-import:CAP-603")
      (libsource (lib "eagle-import") (part "CAP-603"))
    )
    (comp (ref "C50")
      (value "220uF")
      (footprint "eagle-import:CAP-TAN-1411")
      (libsource (lib "eagle-import") (part "CAP-TAN-1411"))
    )
    (comp (ref "C51")
      (value "2.2uF")
      (footprint "eagle-import:CAP-603")
      (libsource (lib "eagle-import") (part "CAP-603"))
    )
    (comp (ref "C56")
      (value "0.1uF")
      (footprint "eagle-import:CAP-603")
      (libsource (lib "eagle-import") (part "CAP-603"))
    )
    (comp (ref "L2")
      (value "IND-NRS8040T6R8NJGJ")
      (footprint "eagle-import:IND-NRS8040T6R8NJGJ")
      (libsource (lib "eagle-import") (part "IND-NRS8040T6R8NJGJ"))
    )
    (comp (ref "LCD_PWR_CONN")
      (value "CONN-282834-2")
      (footprint "eagle-import:CONN-282834-2")
      (libsource (lib "eagle-import") (part "CONN-282834-2"))
    )
    (comp (ref "R36")
      (value "180K")
      (footprint "eagle-import:RES-603")
      (libsource (lib "eagle-import") (part "RES-603"))
    )
    (comp (ref "R41")
      (value "47")
      (footprint "eagle-import:RES-603")
      (libsource (lib "eagle-import") (part "RES-603"))
    )
    (comp (ref "R46")
      (value "1.65M")
      (footprint "eagle-import:RES-603")
      (libsource (lib "eagle-import") (part "RES-603"))
    )
    (comp (ref "TP2")
      (value "TESTPOINT")
      (footprint "eagle-import:TESTPOINT")
      (libsource (lib "eagle-import") (part "TESTPOINT"))
    )
    (comp (ref "C61")
      (value "0.1uF")
      (footprint "eagle-import:CAP-603")
      (libsource (lib "eagle-import") (part "Personal_vf.c4yF0r8uTPqxhtoqvO0ekg_CAP-603"))
    )
    (comp (ref "C62")
      (value "0.1uF")
      (footprint "eagle-import:CAP-603")
      (libsource (lib "eagle-import") (part "Personal_vf.c4yF0r8uTPqxhtoqvO0ekg_CAP-603"))
    )
    (comp (ref "C63")
      (value "10uF")
      (footprint "eagle-import:CAP-603")
      (libsource (lib "eagle-import") (part "Personal_vf.c4yF0r8uTPqxhtoqvO0ekg_CAP-603"))
    )
    (comp (ref "C64")
      (value "10uF")
      (footprint "eagle-import:CAP-603")
      (libsource (lib "eagle-import") (part "Personal_vf.c4yF0r8uTPqxhtoqvO0ekg_CAP-603"))
    )
    (comp (ref "CLK-32.768")
      (value "CLK-ECS-327")
      (footprint "eagle-import:CLK-ECS-327")
      (libsource (lib "eagle-import") (part "CLK-ECS-327"))
    )
    (comp (ref "WIFI/BT")
      (value "IC-LWB5+")
      (footprint "eagle-import:IC-LWB5+")
      (libsource (lib "eagle-import") (part "IC-LWB5+"))
    )
  )
  (nets
    (net (code "1") (name "AGND") (class "Default")
      (node (ref "AUDIO_DAC") (pin "15") (pinfunction "VSSA_15") (pintype "power_in"))
      (node (ref "BOARD_CONN_1") (pin "11") (pinfunction "11_11") (pintype "bidirectional"))
      (node (ref "C12") (pin "A") (pinfunction "A_A") (pintype "bidirectional"))
      (node (ref "C13") (pin "A") (pinfunction "A_A") (pintype "bidirectional"))
      (node (ref "C25") (pin "A") (pinfunction "A_A") (pintype "bidirectional"))
      (node (ref "C27") (pin "A") (pinfunction "A_A") (pintype "bidirectional"))
      (node (ref "C36") (pin "A") (pinfunction "A_A") (pintype "bidirectional"))
      (node (ref "C37") (pin "A") (pinfunction "A_A") (pintype "bidirectional"))
      (node (ref "C46") (pin "A") (pinfunction "A_A") (pintype "bidirectional"))
      (node (ref "C47") (pin "A") (pinfunction "A_A") (pintype "bidirectional"))
      (node (ref "FB2") (pin "1") (pinfunction "P$1_1") (pintype "passive"))
      (node (ref "R37") (pin "A") (pinfunction "A_A") (pintype "bidirectional"))
      (node (ref "R38") (pin "A") (pinfunction "A_A") (pintype "bidirectional"))
    )
    (net (code "2") (name "AUDSD") (class "Default")
      (node (ref "AUDIO_AMP") (pin "P$2") (pinfunction "SHDN_P$2") (pintype "input"))
      (node (ref "BOARD_CONN_1") (pin "14") (pinfunction "14_14") (pintype "bidirectional"))
      (node (ref "R14") (pin "A") (pinfunction "A_A") (pintype "bidirectional"))
    )
    (net (code "3") (name "BAT") (class "Default")
      (node (ref "BAT_CHR") (pin "BAT1") (pinfunction "BAT_BAT1") (pintype "bidirectional"))
      (node (ref "BAT_CHR") (pin "BAT2") (pinfunction "BAT_BAT2") (pintype "bidirectional"))
      (node (ref "BAT_CONN") (pin "1") (pinfunction "1_1") (pintype "bidirectional"))
      (node (ref "BUT_PWR") (pin "1") (pinfunction "1_1") (pintype "bidirectional"))
      (node (ref "C16") (pin "C") (pinfunction "C_C") (pintype "bidirectional"))
      (node (ref "C2") (pin "C") (pinfunction "C_C") (pintype "bidirectional"))
    )
    (net (code "4") (name "BITCLK_IN") (class "Default")
      (node (ref "LEVEL_ADJ") (pin "A3") (pinfunction "A3_A3") (pintype "bidirectional"))
      (node (ref "RPI_PINS1-100") (pin "49") (pinfunction "49_49") (pintype "bidirectional"))
      (node (ref "TP17") (pin "TP") (pinfunction "TP_TP") (pintype "bidirectional"))
    )
    (net (code "5") (name "BT_REG_ON") (class "Default")
      (node (ref "RPI_PINS1-100") (pin "34") (pinfunction "34_34") (pintype "bidirectional"))
      (node (ref "WIFI/BT") (pin "32") (pinfunction "32_32") (pintype "bidirectional"))
    )
    (net (code "6") (name "BT_UART_CTS") (class "Default")
      (node (ref "RPI_PINS1-100") (pin "29") (pinfunction "29_29") (pintype "bidirectional"))
      (node (ref "WIFI/BT") (pin "46") (pinfunction "46_46") (pintype "bidirectional"))
    )
    (net (code "7") (name "BT_UART_RTS") (class "Default")
      (node (ref "RPI_PINS1-100") (pin "50") (pinfunction "50_50") (pintype "bidirectional"))
      (node (ref "WIFI/BT") (pin "44") (pinfunction "44_44") (pintype "bidirectional"))
    )
    (net (code "8") (name "BT_UART_RXD") (class "Default")
      (node (ref "RPI_PINS1-100") (pin "51") (pinfunction "51_51") (pintype "bidirectional"))
      (node (ref "WIFI/BT") (pin "43") (pinfunction "43_43") (pintype "bidirectional"))
    )
    (net (code "9") (name "BT_UART_TXD") (class "Default")
      (node (ref "RPI_PINS1-100") (pin "55") (pinfunction "55_55") (pintype "bidirectional"))
      (node (ref "WIFI/BT") (pin "45") (pinfunction "45_45") (pintype "bidirectional"))
    )
    (net (code "10") (name "D+") (class "Default")
      (node (ref "BAT_CHR") (pin "D+") (pinfunction "D+_D+") (pintype "bidirectional"))
      (node (ref "USB_PWR") (pin "D+") (pinfunction "D+_D+") (pintype "bidirectional"))
      (node (ref "USB_PWR") (pin "D+_2") (pinfunction "D+_D+_2") (pintype "bidirectional"))
    )
    (net (code "11") (name "D+1") (class "Default")
      (node (ref "BOARD_CONN_1") (pin "10") (pinfunction "10_10") (pintype "bidirectional"))
      (node (ref "USB_HUB") (pin "4") (pinfunction "4_4") (pintype "bidirectional"))
    )
    (net (code "12") (name "D+2") (class "Default")
      (node (ref "BOARD_CONN_1") (pin "8") (pinfunction "8_8") (pintype "bidirectional"))
      (node (ref "USB_HUB") (pin "7") (pinfunction "7_7") (pintype "bidirectional"))
    )
    (net (code "13") (name "D-") (class "Default")
      (node (ref "BAT_CHR") (pin "D-") (pinfunction "D-_D-") (pintype "bidirectional"))
      (node (ref "USB_PWR") (pin "D-") (pinfunction "D-_D-") (pintype "bidirectional"))
      (node (ref "USB_PWR") (pin "D-_2") (pinfunction "D-_D-_2") (pintype "bidirectional"))
    )
    (net (code "14") (name "D-1") (class "Default")
      (node (ref "BOARD_CONN_1") (pin "9") (pinfunction "9_9") (pintype "bidirectional"))
      (node (ref "USB_HUB") (pin "3") (pinfunction "3_3") (pintype "bidirectional"))
    )
    (net (code "15") (name "D-2") (class "Default")
      (node (ref "BOARD_CONN_1") (pin "7") (pinfunction "7_7") (pintype "bidirectional"))
      (node (ref "USB_HUB") (pin "6") (pinfunction "6_6") (pintype "bidirectional"))
    )
    (net (code "16") (name "DATA_IN") (class "Default")
      (node (ref "LEVEL_ADJ") (pin "A2") (pinfunction "A2_A2") (pintype "bidirectional"))
      (node (ref "RPI_PINS1-100") (pin "25") (pinfunction "25_25") (pintype "bidirectional"))
      (node (ref "TP19") (pin "TP") (pinfunction "TP_TP") (pintype "bidirectional"))
    )
    (net (code "17") (name "DEEM{slash}CLKOUT") (class "Default")
      (node (ref "AUDIO_DAC") (pin "9") (pinfunction "DEEM/CLKOUT_9") (pintype "bidirectional"))
      (node (ref "R12") (pin "C") (pinfunction "C_C") (pintype "bidirectional"))
    )
    (net (code "18") (name "DSEL") (class "Default")
      (node (ref "BAT_CHR") (pin "DSEL") (pinfunction "DSEL_DSEL") (pintype "bidirectional"))
      (node (ref "R5") (pin "C") (pinfunction "C_C") (pintype "bidirectional"))
    )
    (net (code "19") (name "DSI1_C_N") (class "Default")
      (node (ref "LCD_CONN") (pin "11") (pinfunction "11_11") (pintype "bidirectional"))
      (node (ref "RPI_PINS101-200") (pin "87") (pinfunction "87_87") (pintype "bidirectional"))
    )
    (net (code "20") (name "DSI1_C_P") (class "Default")
      (node (ref "LCD_CONN") (pin "10") (pinfunction "10_10") (pintype "bidirectional"))
      (node (ref "RPI_PINS101-200") (pin "89") (pinfunction "89_89") (pintype "bidirectional"))
    )
    (net (code "21") (name "DSI1_D0_N") (class "Default")
      (node (ref "LCD_CONN") (pin "8") (pinfunction "8_8") (pintype "bidirectional"))
      (node (ref "RPI_PINS101-200") (pin "75") (pinfunction "75_75") (pintype "bidirectional"))
    )
    (net (code "22") (name "DSI1_D0_P") (class "Default")
      (node (ref "LCD_CONN") (pin "7") (pinfunction "7_7") (pintype "bidirectional"))
      (node (ref "RPI_PINS101-200") (pin "77") (pinfunction "77_77") (pintype "bidirectional"))
    )
    (net (code "23") (name "DSI1_D1_N") (class "Default")
      (node (ref "LCD_CONN") (pin "14") (pinfunction "14_14") (pintype "bidirectional"))
      (node (ref "RPI_PINS101-200") (pin "81") (pinfunction "81_81") (pintype "bidirectional"))
    )
    (net (code "24") (name "DSI1_D1_P") (class "Default")
      (node (ref "LCD_CONN") (pin "13") (pinfunction "13_13") (pintype "bidirectional"))
      (node (ref "RPI_PINS101-200") (pin "83") (pinfunction "83_83") (pintype "bidirectional"))
    )
    (net (code "25") (name "ETH0_N") (class "Default")
      (node (ref "BOARD_CONN_1") (pin "22") (pinfunction "22_22") (pintype "bidirectional"))
      (node (ref "RPI_PINS1-100") (pin "10") (pinfunction "10_10") (pintype "bidirectional"))
    )
    (net (code "26") (name "ETH0_P") (class "Default")
      (node (ref "BOARD_CONN_1") (pin "23") (pinfunction "23_23") (pintype "bidirectional"))
      (node (ref "RPI_PINS1-100") (pin "12") (pinfunction "12_12") (pintype "bidirectional"))
    )
    (net (code "27") (name "ETH1_N") (class "Default")
      (node (ref "BOARD_CONN_1") (pin "20") (pinfunction "20_20") (pintype "bidirectional"))
      (node (ref "RPI_PINS1-100") (pin "6") (pinfunction "6_6") (pintype "bidirectional"))
    )
    (net (code "28") (name "ETH1_P") (class "Default")
      (node (ref "BOARD_CONN_1") (pin "21") (pinfunction "21_21") (pintype "bidirectional"))
      (node (ref "RPI_PINS1-100") (pin "4") (pinfunction "4_4") (pintype "bidirectional"))
    )
    (net (code "29") (name "ETH2_N") (class "Default")
      (node (ref "BOARD_CONN_1") (pin "18") (pinfunction "18_18") (pintype "bidirectional"))
      (node (ref "RPI_PINS1-100") (pin "9") (pinfunction "9_9") (pintype "bidirectional"))
    )
    (net (code "30") (name "ETH2_P") (class "Default")
      (node (ref "BOARD_CONN_1") (pin "19") (pinfunction "19_19") (pintype "bidirectional"))
      (node (ref "RPI_PINS1-100") (pin "11") (pinfunction "11_11") (pintype "bidirectional"))
    )
    (net (code "31") (name "ETH3_N") (class "Default")
      (node (ref "BOARD_CONN_1") (pin "16") (pinfunction "16_16") (pintype "bidirectional"))
      (node (ref "RPI_PINS1-100") (pin "5") (pinfunction "5_5") (pintype "bidirectional"))
    )
    (net (code "32") (name "ETH3_P") (class "Default")
      (node (ref "BOARD_CONN_1") (pin "17") (pinfunction "17_17") (pintype "bidirectional"))
      (node (ref "RPI_PINS1-100") (pin "3") (pinfunction "3_3") (pintype "bidirectional"))
    )
    (net (code "33") (name "ETH_LEDG") (class "Default")
      (node (ref "BOARD_CONN_1") (pin "24") (pinfunction "24_24") (pintype "bidirectional"))
      (node (ref "RPI_PINS1-100") (pin "15") (pinfunction "15_15") (pintype "bidirectional"))
    )
    (net (code "34") (name "ETH_LEDY") (class "Default")
      (node (ref "BOARD_CONN_1") (pin "25") (pinfunction "25_25") (pintype "bidirectional"))
      (node (ref "RPI_PINS1-100") (pin "17") (pinfunction "17_17") (pintype "bidirectional"))
    )
    (net (code "35") (name "FB") (class "Default")
      (node (ref "5V_REG") (pin "FB") (pinfunction "FB_FB") (pintype "bidirectional"))
      (node (ref "R36") (pin "C") (pinfunction "C_C") (pintype "bidirectional"))
      (node (ref "R46") (pin "A") (pinfunction "A_A") (pintype "bidirectional"))
    )
    (net (code "36") (name "GAIN1") (class "Default")
      (node (ref "AUDIO_AMP") (pin "P$5") (pinfunction "GAIN_P$5") (pintype "input"))
      (node (ref "R47") (pin "A") (pinfunction "A_A") (pintype "bidirectional"))
      (node (ref "R48") (pin "A") (pinfunction "A_A") (pintype "bidirectional"))
      (node (ref "R49") (pin "A") (pinfunction "A_A") (pintype "bidirectional"))
      (node (ref "R50") (pin "A") (pinfunction "A_A") (pintype "bidirectional"))
    )
    (net (code "37") (name "GLOBAL_EN") (class "Default")
      (node (ref "RPI_PINS1-100") (pin "99") (pinfunction "99_99") (pintype "bidirectional"))
      (node (ref "TP12") (pin "TP") (pinfunction "TP_TP") (pintype "bidirectional"))
      (node (ref "TR4") (pin "D") (pinfunction "D_D") (pintype "bidirectional"))
    )
    (net (code "38") (name "GND") (class "Default")
      (node (ref "3.3V-1.8V_REG") (pin "GND1") (pinfunction "GND_GND1") (pintype "bidirectional"))
      (node (ref "3.3V-1.8V_REG") (pin "GND2") (pinfunction "GND_GND2") (pintype "bidirectional"))
      (node (ref "3.3V-1.8V_REG") (pin "PWRPAD") (pinfunction "GND_PWRPAD") (pintype "bidirectional"))
      (node (ref "5V_REG") (pin "GND") (pinfunction "GND_GND") (pintype "bidirectional"))
      (node (ref "5V_REG") (pin "LBI") (pinfunction "LBI_LBI") (pintype "bidirectional"))
      (node (ref "5V_REG") (pin "LBO") (pinfunction "LBO_LBO") (pintype "bidirectional"))
      (node (ref "5V_REG") (pin "PGND1") (pinfunction "PGND_PGND1") (pintype "bidirectional"))
      (node (ref "5V_REG") (pin "PGND2") (pinfunction "PGND_PGND2") (pintype "bidirectional"))
      (node (ref "5V_REG") (pin "PGND3") (pinfunction "PGND_PGND3") (pintype "bidirectional"))
      (node (ref "5V_REG") (pin "PWRPAD") (pinfunction "PGND_PWRPAD") (pintype "bidirectional"))
      (node (ref "5V_REG") (pin "SYNC") (pinfunction "SYNC_SYNC") (pintype "bidirectional"))
      (node (ref "ACCEL") (pin "10") (pinfunction "GND_10") (pintype "power_in"))
      (node (ref "ACCEL") (pin "12") (pinfunction "GND_12") (pintype "power_in"))
      (node (ref "ACCEL") (pin "5") (pinfunction "GND_5") (pintype "power_in"))
      (node (ref "AUDIO_AMP") (pin "P$1") (pinfunction "PGND_P$1") (pintype "power_in"))
      (node (ref "AUDIO_AMP") (pin "P$8") (pinfunction "PGND_P$8") (pintype "power_in"))
      (node (ref "AUDIO_AMP") (pin "P$THERMAL") (pinfunction "THERMAL_P$THERMAL") (pintype "power_in"))
      (node (ref "AUDIO_DAC") (pin "5") (pinfunction "VSSD_5") (pintype "power_in"))
      (node (ref "BAT_CHR") (pin "/CE") (pinfunction "/CE_/CE") (pintype "bidirectional"))
      (node (ref "BAT_CHR") (pin "OTG") (pinfunction "OTG_OTG") (pintype "bidirectional"))
      (node (ref "BAT_CHR") (pin "PGND1") (pinfunction "PGND_PGND1") (pintype "bidirectional"))
      (node (ref "BAT_CHR") (pin "PGND2") (pinfunction "PGND_PGND2") (pintype "bidirectional"))
      (node (ref "BAT_CHR") (pin "PWRPAD") (pinfunction "PGND_PWRPAD") (pintype "bidirectional"))
      (node (ref "BAT_CONN") (pin "2") (pinfunction "2_2") (pintype "bidirectional"))
      (node (ref "BOARD_CONN_1") (pin "15") (pinfunction "15_15") (pintype "bidirectional"))
      (node (ref "BOARD_CONN_1") (pin "26") (pinfunction "26_26") (pintype "bidirectional"))
      (node (ref "BOARD_CONN_1") (pin "27") (pinfunction "27_27") (pintype "bidirectional"))
      (node (ref "BOARD_CONN_1") (pin "28") (pinfunction "28_28") (pintype "bidirectional"))
      (node (ref "BOARD_CONN_1") (pin "29") (pinfunction "29_29") (pintype "bidirectional"))
      (node (ref "BOARD_CONN_1") (pin "30") (pinfunction "30_30") (pintype "bidirectional"))
      (node (ref "BOARD_CONN_1") (pin "MP_1") (pinfunction "MP_MP_1") (pintype "bidirectional"))
      (node (ref "BOARD_CONN_1") (pin "MP_2") (pinfunction "MP_MP_2") (pintype "bidirectional"))
      (node (ref "BOARD_CONN_1") (pin "MP_3") (pinfunction "MP_MP_3") (pintype "bidirectional"))
      (node (ref "BOARD_CONN_1") (pin "MP_4") (pinfunction "MP_MP_4") (pintype "bidirectional"))
      (node (ref "BUF1") (pin "GND") (pinfunction "GND_GND") (pintype "bidirectional"))
      (node (ref "BUF2") (pin "GND") (pinfunction "GND_GND") (pintype "bidirectional"))
      (node (ref "BUF3") (pin "GND") (pinfunction "GND_GND") (pintype "bidirectional"))
      (node (ref "BUTL_CONN") (pin "10") (pinfunction "10_10") (pintype "bidirectional"))
      (node (ref "BUTL_CONN") (pin "7") (pinfunction "7_7") (pintype "bidirectional"))
      (node (ref "BUTL_CONN") (pin "8") (pinfunction "8_8") (pintype "bidirectional"))
      (node (ref "BUTL_CONN") (pin "9") (pinfunction "9_9") (pintype "bidirectional"))
      (node (ref "BUTL_CONN") (pin "MP1") (pinfunction "MP1_MP1") (pintype "bidirectional"))
      (node (ref "BUTL_CONN") (pin "MP2") (pinfunction "MP2_MP2") (pintype "bidirectional"))
      (node (ref "BUTR_CONN") (pin "1") (pinfunction "1_1") (pintype "bidirectional"))
      (node (ref "BUTR_CONN") (pin "10") (pinfunction "10_10") (pintype "bidirectional"))
      (node (ref "BUTR_CONN") (pin "MP1") (pinfunction "MP1_MP1") (pintype "bidirectional"))
      (node (ref "BUTR_CONN") (pin "MP2") (pinfunction "MP2_MP2") (pintype "bidirectional"))
      (node (ref "BUT_MISC") (pin "1") (pinfunction "1_1") (pintype "bidirectional"))
      (node (ref "BUT_VOL_DOWN") (pin "1") (pinfunction "1_1") (pintype "bidirectional"))
      (node (ref "BUT_VOL_UP") (pin "1") (pinfunction "1_1") (pintype "bidirectional"))
      (node (ref "C1") (pin "A") (pinfunction "A_A") (pintype "bidirectional"))
      (node (ref "C10") (pin "A") (pinfunction "A_A") (pintype "bidirectional"))
      (node (ref "C11") (pin "A") (pinfunction "A_A") (pintype "bidirectional"))
      (node (ref "C14") (pin "A") (pinfunction "A_A") (pintype "bidirectional"))
      (node (ref "C15") (pin "A") (pinfunction "A_A") (pintype "bidirectional"))
      (node (ref "C16") (pin "A") (pinfunction "A_A") (pintype "bidirectional"))
      (node (ref "C17") (pin "A") (pinfunction "A_A") (pintype "bidirectional"))
      (node (ref "C18") (pin "A") (pinfunction "A_A") (pintype "bidirectional"))
      (node (ref "C19") (pin "A") (pinfunction "A_A") (pintype "bidirectional"))
      (node (ref "C2") (pin "A") (pinfunction "A_A") (pintype "bidirectional"))
      (node (ref "C20") (pin "A") (pinfunction "A_A") (pintype "bidirectional"))
      (node (ref "C21") (pin "A") (pinfunction "A_A") (pintype "bidirectional"))
      (node (ref "C28") (pin "A") (pinfunction "A_A") (pintype "bidirectional"))
      (node (ref "C29") (pin "C") (pinfunction "C_C") (pintype "bidirectional"))
      (node (ref "C3") (pin "A") (pinfunction "A_A") (pintype "bidirectional"))
      (node (ref "C30") (pin "A") (pinfunction "A_A") (pintype "bidirectional"))
      (node (ref "C31") (pin "C") (pinfunction "C_C") (pintype "bidirectional"))
      (node (ref "C32") (pin "A") (pinfunction "A_A") (pintype "bidirectional"))
      (node (ref "C33") (pin "A") (pinfunction "A_A") (pintype "bidirectional"))
      (node (ref "C34") (pin "A") (pinfunction "A_A") (pintype "bidirectional"))
      (node (ref "C35") (pin "A") (pinfunction "A_A") (pintype "bidirectional"))
      (node (ref "C38") (pin "A") (pinfunction "A_A") (pintype "bidirectional"))
      (node (ref "C39") (pin "A") (pinfunction "A_A") (pintype "bidirectional"))
      (node (ref "C4") (pin "A") (pinfunction "A_A") (pintype "bidirectional"))
      (node (ref "C40") (pin "A") (pinfunction "A_A") (pintype "bidirectional"))
      (node (ref "C41") (pin "A") (pinfunction "A_A") (pintype "bidirectional"))
      (node (ref "C42") (pin "A") (pinfunction "A_A") (pintype "bidirectional"))
      (node (ref "C43") (pin "A") (pinfunction "A_A") (pintype "bidirectional"))
      (node (ref "C44") (pin "A") (pinfunction "A_A") (pintype "bidirectional"))
      (node (ref "C45") (pin "A") (pinfunction "A_A") (pintype "bidirectional"))
      (node (ref "C48") (pin "A") (pinfunction "A_A") (pintype "bidirectional"))
      (node (ref "C5") (pin "A") (pinfunction "A_A") (pintype "bidirectional"))
      (node (ref "C50") (pin "C") (pinfunction "C_C") (pintype "bidirectional"))
      (node (ref "C51") (pin "A") (pinfunction "A_A") (pintype "bidirectional"))
      (node (ref "C52") (pin "A") (pinfunction "A_A") (pintype "bidirectional"))
      (node (ref "C53") (pin "A") (pinfunction "A_A") (pintype "bidirectional"))
      (node (ref "C56") (pin "C") (pinfunction "C_C") (pintype "bidirectional"))
      (node (ref "C57") (pin "C") (pinfunction "C_C") (pintype "bidirectional"))
      (node (ref "C58") (pin "A") (pinfunction "A_A") (pintype "bidirectional"))
      (node (ref "C59") (pin "A") (pinfunction "A_A") (pintype "bidirectional"))
      (node (ref "C6") (pin "A") (pinfunction "A_A") (pintype "bidirectional"))
      (node (ref "C60") (pin "A") (pinfunction "A_A") (pintype "bidirectional"))
      (node (ref "C61") (pin "A") (pinfunction "A_A") (pintype "bidirectional"))
      (node (ref "C62") (pin "A") (pinfunction "A_A") (pintype "bidirectional"))
      (node (ref "C63") (pin "A") (pinfunction "A_A") (pintype "bidirectional"))
      (node (ref "C64") (pin "A") (pinfunction "A_A") (pintype "bidirectional"))
      (node (ref "C7") (pin "A") (pinfunction "A_A") (pintype "bidirectional"))
      (node (ref "C8") (pin "A") (pinfunction "A_A") (pintype "bidirectional"))
      (node (ref "C9") (pin "A") (pinfunction "A_A") (pintype "bidirectional"))
      (node (ref "CLK-32.768") (pin "GND") (pinfunction "GND_GND") (pintype "bidirectional"))
      (node (ref "CLK_24M") (pin "GND_1") (pinfunction "GND_GND_1") (pintype "bidirectional"))
      (node (ref "CLK_24M") (pin "GND_2") (pinfunction "GND_GND_2") (pintype "bidirectional"))
      (node (ref "FB2") (pin "2") (pinfunction "P$2_2") (pintype "passive"))
      (node (ref "HDMI_CONN") (pin "1") (pinfunction "1_1") (pintype "bidirectional"))
      (node (ref "HDMI_CONN") (pin "10") (pinfunction "10_10") (pintype "bidirectional"))
      (node (ref "HDMI_CONN") (pin "13") (pinfunction "13_13") (pintype "bidirectional"))
      (node (ref "HDMI_CONN") (pin "4") (pinfunction "4_4") (pintype "bidirectional"))
      (node (ref "HDMI_CONN") (pin "7") (pinfunction "7_7") (pintype "bidirectional"))
      (node (ref "HDMI_CONN") (pin "MP_1") (pinfunction "MP_MP_1") (pintype "bidirectional"))
      (node (ref "HDMI_CONN") (pin "MP_2") (pinfunction "MP_MP_2") (pintype "bidirectional"))
      (node (ref "HDMI_CONN") (pin "MP_3") (pinfunction "MP_MP_3") (pintype "bidirectional"))
      (node (ref "HDMI_CONN") (pin "MP_4") (pinfunction "MP_MP_4") (pintype "bidirectional"))
      (node (ref "HDMI_CURLIM") (pin "GND") (pinfunction "GND_GND") (pintype "bidirectional"))
      (node (ref "JOYL") (pin "1") (pinfunction "1_1") (pintype "bidirectional"))
      (node (ref "JOYR") (pin "1") (pinfunction "1_1") (pintype "bidirectional"))
      (node (ref "LCD_CONN") (pin "12") (pinfunction "12_12") (pintype "bidirectional"))
      (node (ref "LCD_CONN") (pin "15") (pinfunction "15_15") (pintype "bidirectional"))
      (node (ref "LCD_CONN") (pin "3") (pinfunction "3_3") (pintype "bidirectional"))
      (node (ref "LCD_CONN") (pin "6") (pinfunction "6_6") (pintype "bidirectional"))
      (node (ref "LCD_CONN") (pin "9") (pinfunction "9_9") (pintype "bidirectional"))
      (node (ref "LCD_CONN") (pin "MP_1") (pinfunction "MP_MP_1") (pintype "bidirectional"))
      (node (ref "LCD_CONN") (pin "MP_2") (pinfunction "MP_MP_2") (pintype "bidirectional"))
      (node (ref "LCD_PWR_CONN") (pin "2") (pinfunction "2_2") (pintype "bidirectional"))
      (node (ref "LEVEL_ADJ") (pin "GND") (pinfunction "GND_GND") (pintype "bidirectional"))
      (node (ref "MICROSD") (pin "DL") (pinfunction "MP_DL") (pintype "bidirectional"))
      (node (ref "MICROSD") (pin "DS") (pinfunction "MP_DS") (pintype "bidirectional"))
      (node (ref "MICROSD") (pin "MP_1") (pinfunction "MP_MP_1") (pintype "bidirectional"))
      (node (ref "MICROSD") (pin "MP_2") (pinfunction "MP_MP_2") (pintype "bidirectional"))
      (node (ref "MICROSD") (pin "MP_3") (pinfunction "MP_MP_3") (pintype "bidirectional"))
      (node (ref "MICROSD") (pin "MP_4") (pinfunction "MP_MP_4") (pintype "bidirectional"))
      (node (ref "MICROSD") (pin "VSS") (pinfunction "VSS_VSS") (pintype "bidirectional"))
      (node (ref "MICROSD_SWI") (pin "GND") (pinfunction "GND_GND") (pintype "bidirectional"))
      (node (ref "MOT_CONN") (pin "MP_1") (pinfunction "MP_MP_1") (pintype "bidirectional"))
      (node (ref "MOT_CONN") (pin "MP_2") (pinfunction "MP_MP_2") (pintype "bidirectional"))
      (node (ref "R10") (pin "A") (pinfunction "A_A") (pintype "bidirectional"))
      (node (ref "R11") (pin "A") (pinfunction "A_A") (pintype "bidirectional"))
      (node (ref "R12") (pin "A") (pinfunction "A_A") (pintype "bidirectional"))
      (node (ref "R13") (pin "A") (pinfunction "A_A") (pintype "bidirectional"))
      (node (ref "R15") (pin "A") (pinfunction "A_A") (pintype "bidirectional"))
      (node (ref "R19") (pin "A") (pinfunction "A_A") (pintype "bidirectional"))
      (node (ref "R24") (pin "C") (pinfunction "C_C") (pintype "bidirectional"))
      (node (ref "R27") (pin "C") (pinfunction "C_C") (pintype "bidirectional"))
      (node (ref "R28") (pin "A") (pinfunction "A_A") (pintype "bidirectional"))
      (node (ref "R29") (pin "A") (pinfunction "A_A") (pintype "bidirectional"))
      (node (ref "R30") (pin "C") (pinfunction "C_C") (pintype "bidirectional"))
      (node (ref "R31") (pin "C") (pinfunction "C_C") (pintype "bidirectional"))
      (node (ref "R32") (pin "C") (pinfunction "C_C") (pintype "bidirectional"))
      (node (ref "R33") (pin "C") (pinfunction "C_C") (pintype "bidirectional"))
      (node (ref "R34") (pin "A") (pinfunction "A_A") (pintype "bidirectional"))
      (node (ref "R36") (pin "A") (pinfunction "A_A") (pintype "bidirectional"))
      (node (ref "R45") (pin "A") (pinfunction "A_A") (pintype "bidirectional"))
      (node (ref "R50") (pin "C") (pinfunction "C_C") (pintype "bidirectional"))
      (node (ref "R51") (pin "A") (pinfunction "A_A") (pintype "bidirectional"))
      (node (ref "R6") (pin "A") (pinfunction "A_A") (pintype "bidirectional"))
      (node (ref "R7") (pin "A") (pinfunction "A_A") (pintype "bidirectional"))
      (node (ref "R8") (pin "A") (pinfunction "A_A") (pintype "bidirectional"))
      (node (ref "R9") (pin "A") (pinfunction "A_A") (pintype "bidirectional"))
      (node (ref "RPI_BOOT_SW") (pin "2") (pinfunction "2_2") (pintype "bidirectional"))
      (node (ref "RPI_PINS1-100") (pin "1") (pinfunction "1_1") (pintype "bidirectional"))
      (node (ref "RPI_PINS1-100") (pin "13") (pinfunction "13_13") (pintype "bidirectional"))
      (node (ref "RPI_PINS1-100") (pin "14") (pinfunction "14_14") (pintype "bidirectional"))
      (node (ref "RPI_PINS1-100") (pin "2") (pinfunction "2_2") (pintype "bidirectional"))
      (node (ref "RPI_PINS1-100") (pin "22") (pinfunction "22_22") (pintype "bidirectional"))
      (node (ref "RPI_PINS1-100") (pin "23") (pinfunction "23_23") (pintype "bidirectional"))
      (node (ref "RPI_PINS1-100") (pin "32") (pinfunction "32_32") (pintype "bidirectional"))
      (node (ref "RPI_PINS1-100") (pin "33") (pinfunction "33_33") (pintype "bidirectional"))
      (node (ref "RPI_PINS1-100") (pin "42") (pinfunction "42_42") (pintype "bidirectional"))
      (node (ref "RPI_PINS1-100") (pin "43") (pinfunction "43_43") (pintype "bidirectional"))
      (node (ref "RPI_PINS1-100") (pin "52") (pinfunction "52_52") (pintype "bidirectional"))
      (node (ref "RPI_PINS1-100") (pin "53") (pinfunction "53_53") (pintype "bidirectional"))
      (node (ref "RPI_PINS1-100") (pin "59") (pinfunction "59_59") (pintype "bidirectional"))
      (node (ref "RPI_PINS1-100") (pin "60") (pinfunction "60_60") (pintype "bidirectional"))
      (node (ref "RPI_PINS1-100") (pin "65") (pinfunction "65_65") (pintype "bidirectional"))
      (node (ref "RPI_PINS1-100") (pin "66") (pinfunction "66_66") (pintype "bidirectional"))
      (node (ref "RPI_PINS1-100") (pin "7") (pinfunction "7_7") (pintype "bidirectional"))
      (node (ref "RPI_PINS1-100") (pin "71") (pinfunction "71_71") (pintype "bidirectional"))
      (node (ref "RPI_PINS1-100") (pin "74") (pinfunction "74_74") (pintype "bidirectional"))
      (node (ref "RPI_PINS1-100") (pin "8") (pinfunction "8_8") (pintype "bidirectional"))
      (node (ref "RPI_PINS1-100") (pin "98") (pinfunction "98_98") (pintype "bidirectional"))
      (node (ref "RPI_PINS101-200") (pin "13") (pinfunction "13_13") (pintype "bidirectional"))
      (node (ref "RPI_PINS101-200") (pin "14") (pinfunction "14_14") (pintype "bidirectional"))
      (node (ref "RPI_PINS101-200") (pin "19") (pinfunction "19_19") (pintype "bidirectional"))
      (node (ref "RPI_PINS101-200") (pin "20") (pinfunction "20_20") (pintype "bidirectional"))
      (node (ref "RPI_PINS101-200") (pin "25") (pinfunction "25_25") (pintype "bidirectional"))
      (node (ref "RPI_PINS101-200") (pin "26") (pinfunction "26_26") (pintype "bidirectional"))
      (node (ref "RPI_PINS101-200") (pin "31") (pinfunction "31_31") (pintype "bidirectional"))
      (node (ref "RPI_PINS101-200") (pin "32") (pinfunction "32_32") (pintype "bidirectional"))
      (node (ref "RPI_PINS101-200") (pin "37") (pinfunction "37_37") (pintype "bidirectional"))
      (node (ref "RPI_PINS101-200") (pin "38") (pinfunction "38_38") (pintype "bidirectional"))
      (node (ref "RPI_PINS101-200") (pin "44") (pinfunction "44_44") (pintype "bidirectional"))
      (node (ref "RPI_PINS101-200") (pin "50") (pinfunction "50_50") (pintype "bidirectional"))
      (node (ref "RPI_PINS101-200") (pin "55") (pinfunction "55_55") (pintype "bidirectional"))
      (node (ref "RPI_PINS101-200") (pin "56") (pinfunction "56_56") (pintype "bidirectional"))
      (node (ref "RPI_PINS101-200") (pin "61") (pinfunction "61_61") (pintype "bidirectional"))
      (node (ref "RPI_PINS101-200") (pin "62") (pinfunction "62_62") (pintype "bidirectional"))
      (node (ref "RPI_PINS101-200") (pin "67") (pinfunction "67_67") (pintype "bidirectional"))
      (node (ref "RPI_PINS101-200") (pin "68") (pinfunction "68_68") (pintype "bidirectional"))
      (node (ref "RPI_PINS101-200") (pin "7") (pinfunction "7_7") (pintype "bidirectional"))
      (node (ref "RPI_PINS101-200") (pin "73") (pinfunction "73_73") (pintype "bidirectional"))
      (node (ref "RPI_PINS101-200") (pin "74") (pinfunction "74_74") (pintype "bidirectional"))
      (node (ref "RPI_PINS101-200") (pin "79") (pinfunction "79_79") (pintype "bidirectional"))
      (node (ref "RPI_PINS101-200") (pin "8") (pinfunction "8_8") (pintype "bidirectional"))
      (node (ref "RPI_PINS101-200") (pin "80") (pinfunction "80_80") (pintype "bidirectional"))
      (node (ref "RPI_PINS101-200") (pin "85") (pinfunction "85_85") (pintype "bidirectional"))
      (node (ref "RPI_PINS101-200") (pin "86") (pinfunction "86_86") (pintype "bidirectional"))
      (node (ref "RPI_PINS101-200") (pin "91") (pinfunction "91_91") (pintype "bidirectional"))
      (node (ref "RPI_PINS101-200") (pin "92") (pinfunction "92_92") (pintype "bidirectional"))
      (node (ref "RPI_PINS101-200") (pin "97") (pinfunction "97_97") (pintype "bidirectional"))
      (node (ref "RPI_PINS101-200") (pin "98") (pinfunction "98_98") (pintype "bidirectional"))
      (node (ref "SPK_CONN") (pin "MP_1") (pinfunction "MP_MP_1") (pintype "bidirectional"))
      (node (ref "SPK_CONN") (pin "MP_2") (pinfunction "MP_MP_2") (pintype "bidirectional"))
      (node (ref "T1") (pin "2") (pinfunction "2_2") (pintype "bidirectional"))
      (node (ref "TEENSY") (pin "AGND") (pinfunction "GND_AGND") (pintype "power_in"))
      (node (ref "TEENSY") (pin "GND") (pinfunction "GND_GND") (pintype "power_in"))
      (node (ref "TEENSYUSB") (pin "1") (pinfunction "1_1") (pintype "bidirectional"))
      (node (ref "TR1") (pin "S") (pinfunction "S_S") (pintype "bidirectional"))
      (node (ref "TR2") (pin "S") (pinfunction "S_S") (pintype "bidirectional"))
      (node (ref "TR3") (pin "S") (pinfunction "S_S") (pintype "bidirectional"))
      (node (ref "TR5") (pin "S") (pinfunction "S_S") (pintype "bidirectional"))
      (node (ref "TR6") (pin "S") (pinfunction "S_S") (pintype "bidirectional"))
      (node (ref "USB_CURLIM") (pin "GND") (pinfunction "GND_GND") (pintype "bidirectional"))
      (node (ref "USB_HUB") (pin "37") (pinfunction "37_37") (pintype "bidirectional"))
      (node (ref "USB_IN") (pin "GND") (pinfunction "GND_GND") (pintype "bidirectional"))
      (node (ref "USB_IN") (pin "MP_1") (pinfunction "MP_MP_1") (pintype "bidirectional"))
      (node (ref "USB_IN") (pin "MP_2") (pinfunction "MP_MP_2") (pintype "bidirectional"))
      (node (ref "USB_POE") (pin "GND_1") (pinfunction "GND_GND_1") (pintype "bidirectional"))
      (node (ref "USB_POE") (pin "GND_2") (pinfunction "GND_GND_2") (pintype "bidirectional"))
      (node (ref "USB_PWR") (pin "GND_1") (pinfunction "GND_GND_1") (pintype "bidirectional"))
      (node (ref "USB_PWR") (pin "GND_2") (pinfunction "GND_GND_2") (pintype "bidirectional"))
      (node (ref "USB_PWR") (pin "GND_3") (pinfunction "GND_GND_3") (pintype "bidirectional"))
      (node (ref "USB_PWR") (pin "GND_4") (pinfunction "GND_GND_4") (pintype "bidirectional"))
      (node (ref "USB_PWR") (pin "MP_1") (pinfunction "MP_MP_1") (pintype "bidirectional"))
      (node (ref "USB_PWR") (pin "MP_2") (pinfunction "MP_MP_2") (pintype "bidirectional"))
      (node (ref "USB_PWR") (pin "MP_3") (pinfunction "MP_MP_3") (pintype "bidirectional"))
      (node (ref "USB_PWR") (pin "MP_4") (pinfunction "MP_MP_4") (pintype "bidirectional"))
      (node (ref "USB_SWI") (pin "/OE") (pinfunction "/OE_/OE") (pintype "bidirectional"))
      (node (ref "USB_SWI") (pin "GND") (pinfunction "GND_GND") (pintype "bidirectional"))
      (node (ref "WIFI/BT") (pin "1") (pinfunction "1_1") (pintype "bidirectional"))
      (node (ref "WIFI/BT") (pin "14") (pinfunction "14_14") (pintype "bidirectional"))
      (node (ref "WIFI/BT") (pin "16") (pinfunction "16_16") (pintype "bidirectional"))
      (node (ref "WIFI/BT") (pin "27") (pinfunction "27_27") (pintype "bidirectional"))
      (node (ref "WIFI/BT") (pin "28") (pinfunction "28_28") (pintype "bidirectional"))
      (node (ref "WIFI/BT") (pin "29") (pinfunction "29_29") (pintype "bidirectional"))
      (node (ref "WIFI/BT") (pin "35") (pinfunction "35_35") (pintype "bidirectional"))
      (node (ref "WIFI/BT") (pin "42") (pinfunction "42_42") (pintype "bidirectional"))
      (node (ref "WIFI/BT") (pin "48") (pinfunction "48_48") (pintype "bidirectional"))
      (node (ref "WIFI/BT") (pin "49") (pinfunction "49_49") (pintype "bidirectional"))
      (node (ref "WIFI/BT") (pin "51") (pinfunction "51_51") (pintype "bidirectional"))
      (node (ref "WIFI/BT") (pin "8") (pinfunction "8_8") (pintype "bidirectional"))
      (node (ref "WIFI/BT") (pin "G1") (pinfunction "GND_G1") (pintype "bidirectional"))
      (node (ref "WIFI/BT") (pin "G10") (pinfunction "GND_G10") (pintype "bidirectional"))
      (node (ref "WIFI/BT") (pin "G11") (pinfunction "GND_G11") (pintype "bidirectional"))
      (node (ref "WIFI/BT") (pin "G12") (pinfunction "GND_G12") (pintype "bidirectional"))
      (node (ref "WIFI/BT") (pin "G13") (pinfunction "GND_G13") (pintype "bidirectional"))
      (node (ref "WIFI/BT") (pin "G14") (pinfunction "GND_G14") (pintype "bidirectional"))
      (node (ref "WIFI/BT") (pin "G15") (pinfunction "GND_G15") (pintype "bidirectional"))
      (node (ref "WIFI/BT") (pin "G16") (pinfunction "GND_G16") (pintype "bidirectional"))
      (node (ref "WIFI/BT") (pin "G17") (pinfunction "GND_G17") (pintype "bidirectional"))
      (node (ref "WIFI/BT") (pin "G2") (pinfunction "GND_G2") (pintype "bidirectional"))
      (node (ref "WIFI/BT") (pin "G3") (pinfunction "GND_G3") (pintype "bidirectional"))
      (node (ref "WIFI/BT") (pin "G4") (pinfunction "GND_G4") (pintype "bidirectional"))
      (node (ref "WIFI/BT") (pin "G5") (pinfunction "GND_G5") (pintype "bidirectional"))
      (node (ref "WIFI/BT") (pin "G6") (pinfunction "GND_G6") (pintype "bidirectional"))
      (node (ref "WIFI/BT") (pin "G7") (pinfunction "GND_G7") (pintype "bidirectional"))
      (node (ref "WIFI/BT") (pin "G8") (pinfunction "GND_G8") (pintype "bidirectional"))
      (node (ref "WIFI/BT") (pin "G9") (pinfunction "GND_G9") (pintype "bidirectional"))
    )
    (net (code "39") (name "GPIO7") (class "Default")
      (node (ref "RPI_PINS1-100") (pin "37") (pinfunction "37_37") (pintype "bidirectional"))
      (node (ref "TP11") (pin "TP") (pinfunction "TP_TP") (pintype "bidirectional"))
      (node (ref "TR5") (pin "D") (pinfunction "D_D") (pintype "bidirectional"))
    )
    (net (code "40") (name "GPIO8") (class "Default")
      (node (ref "BUT_MISC") (pin "2") (pinfunction "2_2") (pintype "bidirectional"))
      (node (ref "RPI_PINS1-100") (pin "39") (pinfunction "39_39") (pintype "bidirectional"))
    )
    (net (code "41") (name "GPIO9") (class "Default")
      (node (ref "BUT_VOL_UP") (pin "2") (pinfunction "2_2") (pintype "bidirectional"))
      (node (ref "RPI_PINS1-100") (pin "40") (pinfunction "40_40") (pintype "bidirectional"))
    )
    (net (code "42") (name "GPIO10") (class "Default")
      (node (ref "BUT_VOL_DOWN") (pin "2") (pinfunction "2_2") (pintype "bidirectional"))
      (node (ref "RPI_PINS1-100") (pin "44") (pinfunction "44_44") (pintype "bidirectional"))
    )
    (net (code "43") (name "GPIO11") (class "Default")
      (node (ref "LEVEL_ADJ") (pin "OE") (pinfunction "OE_OE") (pintype "bidirectional"))
      (node (ref "R51") (pin "C") (pinfunction "C_C") (pintype "bidirectional"))
      (node (ref "RPI_PINS1-100") (pin "38") (pinfunction "38_38") (pintype "bidirectional"))
    )
    (net (code "44") (name "GPIO12") (class "Default")
      (node (ref "R19") (pin "C") (pinfunction "C_C") (pintype "bidirectional"))
      (node (ref "RPI_PINS1-100") (pin "31") (pinfunction "31_31") (pintype "bidirectional"))
      (node (ref "TP16") (pin "TP") (pinfunction "TP_TP") (pintype "bidirectional"))
      (node (ref "TR3") (pin "G") (pinfunction "G_G") (pintype "bidirectional"))
    )
    (net (code "45") (name "HDMI0_CEC") (class "Default")
      (node (ref "HDMI_CONN") (pin "14") (pinfunction "14_14") (pintype "bidirectional"))
      (node (ref "RPI_PINS101-200") (pin "51") (pinfunction "51_51") (pintype "bidirectional"))
    )
    (net (code "46") (name "HDMI0_CK_N") (class "Default")
      (node (ref "HDMI_CONN") (pin "12") (pinfunction "12_12") (pintype "bidirectional"))
      (node (ref "RPI_PINS101-200") (pin "90") (pinfunction "90_90") (pintype "bidirectional"))
    )
    (net (code "47") (name "HDMI0_CK_P") (class "Default")
      (node (ref "HDMI_CONN") (pin "11") (pinfunction "11_11") (pintype "bidirectional"))
      (node (ref "RPI_PINS101-200") (pin "88") (pinfunction "88_88") (pintype "bidirectional"))
    )
    (net (code "48") (name "HDMI0_D0_N") (class "Default")
      (node (ref "HDMI_CONN") (pin "9") (pinfunction "9_9") (pintype "bidirectional"))
      (node (ref "RPI_PINS101-200") (pin "84") (pinfunction "84_84") (pintype "bidirectional"))
    )
    (net (code "49") (name "HDMI0_D0_P") (class "Default")
      (node (ref "HDMI_CONN") (pin "8") (pinfunction "8_8") (pintype "bidirectional"))
      (node (ref "RPI_PINS101-200") (pin "82") (pinfunction "82_82") (pintype "bidirectional"))
    )
    (net (code "50") (name "HDMI0_D1_N") (class "Default")
      (node (ref "HDMI_CONN") (pin "6") (pinfunction "6_6") (pintype "bidirectional"))
      (node (ref "RPI_PINS101-200") (pin "78") (pinfunction "78_78") (pintype "bidirectional"))
    )
    (net (code "51") (name "HDMI0_D1_P") (class "Default")
      (node (ref "HDMI_CONN") (pin "5") (pinfunction "5_5") (pintype "bidirectional"))
      (node (ref "RPI_PINS101-200") (pin "76") (pinfunction "76_76") (pintype "bidirectional"))
    )
    (net (code "52") (name "HDMI0_D2_N") (class "Default")
      (node (ref "HDMI_CONN") (pin "3") (pinfunction "3_3") (pintype "bidirectional"))
      (node (ref "RPI_PINS101-200") (pin "72") (pinfunction "72_72") (pintype "bidirectional"))
    )
    (net (code "53") (name "HDMI0_D2_P") (class "Default")
      (node (ref "HDMI_CONN") (pin "2") (pinfunction "2_2") (pintype "bidirectional"))
      (node (ref "RPI_PINS101-200") (pin "70") (pinfunction "70_70") (pintype "bidirectional"))
    )
    (net (code "54") (name "HDMI0_HOTPLUG") (class "Default")
      (node (ref "HDMI_CONN") (pin "19") (pinfunction "19_19") (pintype "bidirectional"))
      (node (ref "RPI_PINS101-200") (pin "53") (pinfunction "53_53") (pintype "bidirectional"))
    )
    (net (code "55") (name "HDMI0_SCL") (class "Default")
      (node (ref "HDMI_CONN") (pin "15") (pinfunction "15_15") (pintype "bidirectional"))
      (node (ref "RPI_PINS101-200") (pin "100") (pinfunction "100_100") (pintype "bidirectional"))
    )
    (net (code "56") (name "HDMI0_SDA") (class "Default")
      (node (ref "HDMI_CONN") (pin "16") (pinfunction "16_16") (pintype "bidirectional"))
      (node (ref "RPI_PINS101-200") (pin "99") (pinfunction "99_99") (pintype "bidirectional"))
    )
    (net (code "57") (name "HDMI_5V") (class "Default")
      (node (ref "C40") (pin "C") (pinfunction "C_C") (pintype "bidirectional"))
      (node (ref "HDMI_CONN") (pin "18") (pinfunction "18_18") (pintype "bidirectional"))
      (node (ref "HDMI_CURLIM") (pin "OUT") (pinfunction "OUT_OUT") (pintype "bidirectional"))
    )
    (net (code "58") (name "ILIM") (class "Default")
      (node (ref "BAT_CHR") (pin "ILIM") (pinfunction "ILIM_ILIM") (pintype "bidirectional"))
      (node (ref "R45") (pin "C") (pinfunction "C_C") (pintype "bidirectional"))
    )
    (net (code "59") (name "INT") (class "Default")
      (node (ref "BAT_CHR") (pin "INT") (pinfunction "INT_INT") (pintype "bidirectional"))
      (node (ref "R3") (pin "C") (pinfunction "C_C") (pintype "bidirectional"))
    )
    (net (code "60") (name "MUTE") (class "Default")
      (node (ref "AUDIO_DAC") (pin "8") (pinfunction "MUTE_8") (pintype "input"))
      (node (ref "R11") (pin "C") (pinfunction "C_C") (pintype "bidirectional"))
    )
    (net (code "61") (name "NPWR_LED") (class "Default")
      (node (ref "BUF2") (pin "A") (pinfunction "A_A") (pintype "bidirectional"))
      (node (ref "RPI_PINS1-100") (pin "95") (pinfunction "95_95") (pintype "bidirectional"))
    )
    (net (code "62") (name "N_EXTRST") (class "Default")
      (node (ref "RPI_PINS1-100") (pin "100") (pinfunction "100_100") (pintype "bidirectional"))
      (node (ref "USB_HUB") (pin "26") (pinfunction "26_26") (pintype "bidirectional"))
    )
    (net (code "63") (name "N_OCS1") (class "Default")
      (node (ref "USB_CURLIM") (pin "NFAULT") (pinfunction "NFAULT_NFAULT") (pintype "bidirectional"))
      (node (ref "USB_HUB") (pin "13") (pinfunction "13_13") (pintype "bidirectional"))
      (node (ref "USB_HUB") (pin "17") (pinfunction "17_17") (pintype "bidirectional"))
      (node (ref "USB_HUB") (pin "19") (pinfunction "19_19") (pintype "bidirectional"))
      (node (ref "USB_HUB") (pin "21") (pinfunction "21_21") (pintype "bidirectional"))
    )
    (net (code "64") (name "N_RPIBOOT") (class "Default")
      (node (ref "RPI_BOOT_SW") (pin "1") (pinfunction "1_1") (pintype "bidirectional"))
      (node (ref "RPI_PINS1-100") (pin "93") (pinfunction "93_93") (pintype "bidirectional"))
    )
    (net (code "65") (name "Net-(3.3V-1.8V_REG-PadEN2)") (class "Default")
      (node (ref "3.3V-1.8V_REG") (pin "EN2") (pinfunction "EN2_EN2") (pintype "bidirectional"))
      (node (ref "C9") (pin "C") (pinfunction "C_C") (pintype "bidirectional"))
      (node (ref "R44") (pin "C") (pinfunction "C_C") (pintype "bidirectional"))
    )
    (net (code "66") (name "Net-(3.3V-1.8V_REG-PadLX1)") (class "Default")
      (node (ref "3.3V-1.8V_REG") (pin "LX1") (pinfunction "LX1_LX1") (pintype "bidirectional"))
      (node (ref "L4") (pin "A") (pinfunction "A_A") (pintype "bidirectional"))
    )
    (net (code "67") (name "Net-(3.3V-1.8V_REG-PadLX2)") (class "Default")
      (node (ref "3.3V-1.8V_REG") (pin "LX2") (pinfunction "LX2_LX2") (pintype "bidirectional"))
      (node (ref "L3") (pin "A") (pinfunction "A_A") (pintype "bidirectional"))
    )
    (net (code "68") (name "Net-(5V_REG-SW-PadSW1)") (class "Default")
      (node (ref "5V_REG") (pin "SW1") (pinfunction "SW_SW1") (pintype "bidirectional"))
      (node (ref "5V_REG") (pin "SW2") (pinfunction "SW_SW2") (pintype "bidirectional"))
      (node (ref "L2") (pin "C") (pinfunction "C_C") (pintype "bidirectional"))
      (node (ref "R41") (pin "A") (pinfunction "A_A") (pintype "bidirectional"))
    )
    (net (code "69") (name "Net-(ACCEL-BYP)") (class "Default")
      (node (ref "ACCEL") (pin "2") (pinfunction "BYP_2") (pintype "input"))
      (node (ref "C45") (pin "C") (pinfunction "C_C") (pintype "bidirectional"))
    )
    (net (code "70") (name "Net-(AUDIO_AMP-INL+)") (class "Default")
      (node (ref "AUDIO_AMP") (pin "P$3") (pinfunction "INL+_P$3") (pintype "input"))
      (node (ref "C24") (pin "C") (pinfunction "C_C") (pintype "bidirectional"))
    )
    (net (code "71") (name "Net-(AUDIO_AMP-INL-)") (class "Default")
      (node (ref "AUDIO_AMP") (pin "P$4") (pinfunction "INL-_P$4") (pintype "input"))
      (node (ref "C25") (pin "C") (pinfunction "C_C") (pintype "bidirectional"))
    )
    (net (code "72") (name "Net-(AUDIO_AMP-INR+)") (class "Default")
      (node (ref "AUDIO_AMP") (pin "P$7") (pinfunction "INR+_P$7") (pintype "input"))
      (node (ref "C26") (pin "C") (pinfunction "C_C") (pintype "bidirectional"))
    )
    (net (code "73") (name "Net-(AUDIO_AMP-INR-)") (class "Default")
      (node (ref "AUDIO_AMP") (pin "P$6") (pinfunction "INR-_P$6") (pintype "input"))
      (node (ref "C27") (pin "C") (pinfunction "C_C") (pintype "bidirectional"))
    )
    (net (code "74") (name "Net-(AUDIO_AMP-OUTL+)") (class "Default")
      (node (ref "AUDIO_AMP") (pin "P$13") (pinfunction "OUTL+_P$13") (pintype "output"))
      (node (ref "SPK_CONN") (pin "1") (pinfunction "1_1") (pintype "bidirectional"))
    )
    (net (code "75") (name "Net-(AUDIO_AMP-OUTL-)") (class "Default")
      (node (ref "AUDIO_AMP") (pin "P$14") (pinfunction "OUTL-_P$14") (pintype "output"))
      (node (ref "SPK_CONN") (pin "2") (pinfunction "2_2") (pintype "bidirectional"))
    )
    (net (code "76") (name "Net-(AUDIO_AMP-OUTR+)") (class "Default")
      (node (ref "AUDIO_AMP") (pin "P$10") (pinfunction "OUTR+_P$10") (pintype "output"))
      (node (ref "SPK_CONN") (pin "3") (pinfunction "3_3") (pintype "bidirectional"))
    )
    (net (code "77") (name "Net-(AUDIO_AMP-OUTR-)") (class "Default")
      (node (ref "AUDIO_AMP") (pin "P$9") (pinfunction "OUTR-_P$9") (pintype "output"))
      (node (ref "SPK_CONN") (pin "4") (pinfunction "4_4") (pintype "bidirectional"))
    )
    (net (code "78") (name "Net-(AUDIO_DAC-BCK)") (class "Default")
      (node (ref "AUDIO_DAC") (pin "1") (pinfunction "BCK_1") (pintype "input"))
      (node (ref "LEVEL_ADJ") (pin "B3") (pinfunction "B3_B3") (pintype "bidirectional"))
    )
    (net (code "79") (name "Net-(AUDIO_DAC-DATAI)") (class "Default")
      (node (ref "AUDIO_DAC") (pin "3") (pinfunction "DATAI_3") (pintype "input"))
      (node (ref "LEVEL_ADJ") (pin "B2") (pinfunction "B2_B2") (pintype "bidirectional"))
    )
    (net (code "80") (name "Net-(AUDIO_DAC-VDDA)") (class "Default")
      (node (ref "AUDIO_DAC") (pin "13") (pinfunction "VDDA_13") (pintype "power_in"))
      (node (ref "C12") (pin "C") (pinfunction "C_C") (pintype "bidirectional"))
      (node (ref "C36") (pin "C") (pinfunction "C_C") (pintype "bidirectional"))
      (node (ref "FB1") (pin "1") (pinfunction "P$1_1") (pintype "passive"))
    )
    (net (code "81") (name "Net-(AUDIO_DAC-VOUTL)") (class "Default")
      (node (ref "AUDIO_DAC") (pin "14") (pinfunction "VOUTL_14") (pintype "output"))
      (node (ref "C55") (pin "+") (pinfunction "+_+") (pintype "passive"))
    )
    (net (code "82") (name "Net-(AUDIO_DAC-VOUTR)") (class "Default")
      (node (ref "AUDIO_DAC") (pin "16") (pinfunction "VOUTR_16") (pintype "output"))
      (node (ref "C54") (pin "+") (pinfunction "+_+") (pintype "passive"))
    )
    (net (code "83") (name "Net-(AUDIO_DAC-VREF(DAC))") (class "Default")
      (node (ref "AUDIO_DAC") (pin "12") (pinfunction "VREF(DAC)_12") (pintype "output"))
      (node (ref "C13") (pin "C") (pinfunction "C_C") (pintype "bidirectional"))
      (node (ref "C37") (pin "C") (pinfunction "C_C") (pintype "bidirectional"))
    )
    (net (code "84") (name "Net-(AUDIO_DAC-WS)") (class "Default")
      (node (ref "AUDIO_DAC") (pin "2") (pinfunction "WS_2") (pintype "input"))
      (node (ref "LEVEL_ADJ") (pin "B1") (pinfunction "B1_B1") (pintype "bidirectional"))
    )
    (net (code "85") (name "Net-(BAT_CHR-PadBTST)") (class "Default")
      (node (ref "BAT_CHR") (pin "BTST") (pinfunction "BTST_BTST") (pintype "bidirectional"))
      (node (ref "C49") (pin "A") (pinfunction "A_A") (pintype "bidirectional"))
    )
    (net (code "86") (name "Net-(BAT_CHR-PadPMID)") (class "Default")
      (node (ref "BAT_CHR") (pin "PMID") (pinfunction "PMID_PMID") (pintype "bidirectional"))
      (node (ref "C57") (pin "A") (pinfunction "A_A") (pintype "bidirectional"))
    )
    (net (code "87") (name "Net-(BAT_CHR-PadTS)") (class "Default")
      (node (ref "BAT_CHR") (pin "TS") (pinfunction "TS_TS") (pintype "bidirectional"))
      (node (ref "R25") (pin "A") (pinfunction "A_A") (pintype "bidirectional"))
      (node (ref "R29") (pin "C") (pinfunction "C_C") (pintype "bidirectional"))
      (node (ref "T1") (pin "1") (pinfunction "1_1") (pintype "bidirectional"))
    )
    (net (code "88") (name "Net-(BUF1-PadY)") (class "Default")
      (node (ref "BUF1") (pin "Y") (pinfunction "Y_Y") (pintype "bidirectional"))
      (node (ref "LED1") (pin "C") (pinfunction "C_C") (pintype "bidirectional"))
      (node (ref "R17") (pin "A") (pinfunction "A_A") (pintype "bidirectional"))
      (node (ref "TP7") (pin "TP") (pinfunction "TP_TP") (pintype "bidirectional"))
    )
    (net (code "89") (name "Net-(BUF2-PadY)") (class "Default")
      (node (ref "BUF2") (pin "Y") (pinfunction "Y_Y") (pintype "bidirectional"))
      (node (ref "LED2") (pin "C") (pinfunction "C_C") (pintype "bidirectional"))
      (node (ref "R18") (pin "A") (pinfunction "A_A") (pintype "bidirectional"))
      (node (ref "TP8") (pin "TP") (pinfunction "TP_TP") (pintype "bidirectional"))
    )
    (net (code "90") (name "Net-(BUF3-PadY)") (class "Default")
      (node (ref "BUF3") (pin "Y") (pinfunction "Y_Y") (pintype "bidirectional"))
      (node (ref "R16") (pin "A") (pinfunction "A_A") (pintype "bidirectional"))
      (node (ref "TP13") (pin "TP") (pinfunction "TP_TP") (pintype "bidirectional"))
      (node (ref "TR4") (pin "S") (pinfunction "S_S") (pintype "bidirectional"))
    )
    (net (code "91") (name "Net-(BUTL_CONN-Pad3)") (class "Default")
      (node (ref "BUTL_CONN") (pin "3") (pinfunction "3_3") (pintype "bidirectional"))
      (node (ref "TEENSY") (pin "5") (pinfunction "5_5") (pintype "bidirectional"))
    )
    (net (code "92") (name "Net-(BUTL_CONN-Pad6)") (class "Default")
      (node (ref "BUTL_CONN") (pin "6") (pinfunction "6_6") (pintype "bidirectional"))
      (node (ref "TEENSY") (pin "2") (pinfunction "2_2") (pintype "bidirectional"))
    )
    (net (code "93") (name "Net-(BUT_PWR-Pad2)") (class "Default")
      (node (ref "BUT_PWR") (pin "2") (pinfunction "2_2") (pintype "bidirectional"))
      (node (ref "R15") (pin "C") (pinfunction "C_C") (pintype "bidirectional"))
      (node (ref "TR4") (pin "G") (pinfunction "G_G") (pintype "bidirectional"))
      (node (ref "TR5") (pin "G") (pinfunction "G_G") (pintype "bidirectional"))
      (node (ref "TR6") (pin "G") (pinfunction "G_G") (pintype "bidirectional"))
    )
    (net (code "94") (name "Net-(C52-PadC)") (class "Default")
      (node (ref "C52") (pin "C") (pinfunction "C_C") (pintype "bidirectional"))
      (node (ref "CLK_24M") (pin "IN/OUT") (pinfunction "IN/OUT_IN/OUT") (pintype "bidirectional"))
      (node (ref "USB_HUB") (pin "33") (pinfunction "33_33") (pintype "bidirectional"))
    )
    (net (code "95") (name "Net-(C53-PadC)") (class "Default")
      (node (ref "C53") (pin "C") (pinfunction "C_C") (pintype "bidirectional"))
      (node (ref "CLK_24M") (pin "OUT/IN") (pinfunction "OUT/IN_OUT/IN") (pintype "bidirectional"))
      (node (ref "USB_HUB") (pin "32") (pinfunction "32_32") (pintype "bidirectional"))
    )
    (net (code "96") (name "Net-(C54-Pad-)") (class "Default")
      (node (ref "C54") (pin "-") (pinfunction "-_-") (pintype "passive"))
      (node (ref "R38") (pin "C") (pinfunction "C_C") (pintype "bidirectional"))
      (node (ref "R43") (pin "A") (pinfunction "A_A") (pintype "bidirectional"))
    )
    (net (code "97") (name "Net-(C55-Pad-)") (class "Default")
      (node (ref "C55") (pin "-") (pinfunction "-_-") (pintype "passive"))
      (node (ref "R37") (pin "C") (pinfunction "C_C") (pintype "bidirectional"))
      (node (ref "R42") (pin "A") (pinfunction "A_A") (pintype "bidirectional"))
    )
    (net (code "98") (name "Net-(C56-PadA)") (class "Default")
      (node (ref "C56") (pin "A") (pinfunction "A_A") (pintype "bidirectional"))
      (node (ref "R41") (pin "C") (pinfunction "C_C") (pintype "bidirectional"))
    )
    (net (code "99") (name "Net-(D1-PadA)") (class "Default")
      (node (ref "D1") (pin "A") (pinfunction "A_A") (pintype "bidirectional"))
      (node (ref "MOT_CONN") (pin "2") (pinfunction "2_2") (pintype "bidirectional"))
      (node (ref "TR1") (pin "D") (pinfunction "D_D") (pintype "bidirectional"))
    )
    (net (code "100") (name "Net-(D2-PadA)") (class "Default")
      (node (ref "D2") (pin "A") (pinfunction "A_A") (pintype "bidirectional"))
      (node (ref "MOT_CONN") (pin "4") (pinfunction "4_4") (pintype "bidirectional"))
      (node (ref "TR2") (pin "D") (pinfunction "D_D") (pintype "bidirectional"))
    )
    (net (code "101") (name "Net-(D3-PadA)") (class "Default")
      (node (ref "D3") (pin "A") (pinfunction "A_A") (pintype "bidirectional"))
      (node (ref "FAN_CONN") (pin "2") (pinfunction "2_2") (pintype "bidirectional"))
      (node (ref "TR3") (pin "D") (pinfunction "D_D") (pintype "bidirectional"))
    )
    (net (code "102") (name "Net-(JOYL-Pad4)") (class "Default")
      (node (ref "JOYL") (pin "4") (pinfunction "4_4") (pintype "bidirectional"))
      (node (ref "TEENSY") (pin "21/A7") (pinfunction "21/A7_21/A7") (pintype "bidirectional"))
    )
    (net (code "103") (name "Net-(JOYR-Pad2)") (class "Default")
      (node (ref "JOYR") (pin "2") (pinfunction "2_2") (pintype "bidirectional"))
      (node (ref "TEENSY") (pin "14/A0") (pinfunction "14/A0_14/A0") (pintype "bidirectional"))
    )
    (net (code "104") (name "Net-(LED1-PadA)") (class "Default")
      (node (ref "LED1") (pin "A") (pinfunction "A_A") (pintype "bidirectional"))
      (node (ref "R39") (pin "A") (pinfunction "A_A") (pintype "bidirectional"))
    )
    (net (code "105") (name "Net-(LED2-PadA)") (class "Default")
      (node (ref "LED2") (pin "A") (pinfunction "A_A") (pintype "bidirectional"))
      (node (ref "R40") (pin "A") (pinfunction "A_A") (pintype "bidirectional"))
    )
    (net (code "106") (name "Net-(R23-PadA)") (class "Default")
      (node (ref "R23") (pin "A") (pinfunction "A_A") (pintype "bidirectional"))
      (node (ref "TP15") (pin "TP") (pinfunction "TP_TP") (pintype "bidirectional"))
      (node (ref "USB_IN") (pin "VBUS") (pinfunction "VBUS_VBUS") (pintype "bidirectional"))
    )
    (net (code "107") (name "Net-(R27-PadA)") (class "Default")
      (node (ref "R27") (pin "A") (pinfunction "A_A") (pintype "bidirectional"))
      (node (ref "USB_HUB") (pin "35") (pinfunction "35_35") (pintype "bidirectional"))
    )
    (net (code "108") (name "Net-(R28-PadC)") (class "Default")
      (node (ref "R28") (pin "C") (pinfunction "C_C") (pintype "bidirectional"))
      (node (ref "USB_CURLIM") (pin "ILIM") (pinfunction "ILIM_ILIM") (pintype "bidirectional"))
    )
    (net (code "109") (name "Net-(R30-PadA)") (class "Default")
      (node (ref "R30") (pin "A") (pinfunction "A_A") (pintype "bidirectional"))
      (node (ref "USB_HUB") (pin "24") (pinfunction "24_24") (pintype "bidirectional"))
    )
    (net (code "110") (name "Net-(R31-PadA)") (class "Default")
      (node (ref "R31") (pin "A") (pinfunction "A_A") (pintype "bidirectional"))
      (node (ref "USB_HUB") (pin "22") (pinfunction "22_22") (pintype "bidirectional"))
    )
    (net (code "111") (name "Net-(R32-PadA)") (class "Default")
      (node (ref "R32") (pin "A") (pinfunction "A_A") (pintype "bidirectional"))
      (node (ref "USB_HUB") (pin "28") (pinfunction "28_28") (pintype "bidirectional"))
    )
    (net (code "112") (name "Net-(R33-PadA)") (class "Default")
      (node (ref "R33") (pin "A") (pinfunction "A_A") (pintype "bidirectional"))
      (node (ref "USB_HUB") (pin "25") (pinfunction "25_25") (pintype "bidirectional"))
    )
    (net (code "113") (name "Net-(R34-PadC)") (class "Default")
      (node (ref "R34") (pin "C") (pinfunction "C_C") (pintype "bidirectional"))
      (node (ref "R49") (pin "C") (pinfunction "C_C") (pintype "bidirectional"))
    )
    (net (code "114") (name "Net-(R35-PadA)") (class "Default")
      (node (ref "R35") (pin "A") (pinfunction "A_A") (pintype "bidirectional"))
      (node (ref "R47") (pin "C") (pinfunction "C_C") (pintype "bidirectional"))
    )
    (net (code "115") (name "Net-(TEENSY-1{slash}TX1{slash}T{slash}MISO1)") (class "Default")
      (node (ref "JOYL") (pin "5") (pinfunction "5_5") (pintype "bidirectional"))
      (node (ref "TEENSY") (pin "1") (pinfunction "1/TX1/T/MISO1_1") (pintype "bidirectional"))
    )
    (net (code "116") (name "Net-(TEENSY-3{slash}T{slash}PWM)") (class "Default")
      (node (ref "BUTL_CONN") (pin "5") (pinfunction "5_5") (pintype "bidirectional"))
      (node (ref "TEENSY") (pin "3") (pinfunction "3/T/PWM_3") (pintype "bidirectional"))
    )
    (net (code "117") (name "Net-(TEENSY-4{slash}T{slash}PWM)") (class "Default")
      (node (ref "BUTL_CONN") (pin "4") (pinfunction "4_4") (pintype "bidirectional"))
      (node (ref "TEENSY") (pin "4") (pinfunction "4/T/PWM_4") (pintype "bidirectional"))
    )
    (net (code "118") (name "Net-(TEENSY-6{slash}PWM)") (class "Default")
      (node (ref "BUTL_CONN") (pin "2") (pinfunction "2_2") (pintype "bidirectional"))
      (node (ref "TEENSY") (pin "6") (pinfunction "6/PWM_6") (pintype "bidirectional"))
    )
    (net (code "119") (name "Net-(TEENSY-7{slash}RX3)") (class "Default")
      (node (ref "BUTL_CONN") (pin "1") (pinfunction "1_1") (pintype "bidirectional"))
      (node (ref "TEENSY") (pin "7") (pinfunction "7/RX3_7") (pintype "bidirectional"))
    )
    (net (code "120") (name "Net-(TEENSY-8{slash}TX3)") (class "Default")
      (node (ref "JOYR") (pin "5") (pinfunction "5_5") (pintype "bidirectional"))
      (node (ref "TEENSY") (pin "8") (pinfunction "8/TX3_8") (pintype "bidirectional"))
    )
    (net (code "121") (name "Net-(TEENSY-9{slash}RX2{slash}PWM)") (class "Default")
      (node (ref "BUTR_CONN") (pin "6") (pinfunction "6_6") (pintype "bidirectional"))
      (node (ref "TEENSY") (pin "9") (pinfunction "9/RX2/PWM_9") (pintype "bidirectional"))
    )
    (net (code "122") (name "Net-(TEENSY-10{slash}TX2{slash}PWM)") (class "Default")
      (node (ref "BUTR_CONN") (pin "7") (pinfunction "7_7") (pintype "bidirectional"))
      (node (ref "TEENSY") (pin "10") (pinfunction "10/TX2/PWM_10") (pintype "bidirectional"))
    )
    (net (code "123") (name "Net-(TEENSY-11{slash}MOSI)") (class "Default")
      (node (ref "BUTR_CONN") (pin "8") (pinfunction "8_8") (pintype "bidirectional"))
      (node (ref "TEENSY") (pin "11") (pinfunction "11/MOSI_11") (pintype "bidirectional"))
    )
    (net (code "124") (name "Net-(TEENSY-12{slash}MISO)") (class "Default")
      (node (ref "BUTR_CONN") (pin "9") (pinfunction "9_9") (pintype "bidirectional"))
      (node (ref "TEENSY") (pin "12") (pinfunction "12/MISO_12") (pintype "bidirectional"))
    )
    (net (code "125") (name "Net-(TEENSY-15{slash}A1{slash}T)") (class "Default")
      (node (ref "JOYR") (pin "4") (pinfunction "4_4") (pintype "bidirectional"))
      (node (ref "TEENSY") (pin "15/A1") (pinfunction "15/A1/T_15/A1") (pintype "bidirectional"))
    )
    (net (code "126") (name "Net-(TEENSY-16{slash}A2{slash}PWM{slash}T)") (class "Default")
      (node (ref "BUTR_CONN") (pin "5") (pinfunction "5_5") (pintype "bidirectional"))
      (node (ref "TEENSY") (pin "16/A2") (pinfunction "16/A2/PWM/T_16/A2") (pintype "bidirectional"))
    )
    (net (code "127") (name "Net-(TEENSY-17{slash}A3{slash}PWM{slash}T)") (class "Default")
      (node (ref "BUTR_CONN") (pin "4") (pinfunction "4_4") (pintype "bidirectional"))
      (node (ref "TEENSY") (pin "17/A3") (pinfunction "17/A3/PWM/T_17/A3") (pintype "bidirectional"))
    )
    (net (code "128") (name "Net-(TEENSY-18{slash}A4{slash}T{slash}SDA)") (class "Default")
      (node (ref "BUTR_CONN") (pin "3") (pinfunction "3_3") (pintype "bidirectional"))
      (node (ref "TEENSY") (pin "18/A4") (pinfunction "18/A4/T/SDA_18/A4") (pintype "bidirectional"))
    )
    (net (code "129") (name "Net-(TEENSY-19{slash}A5{slash}T{slash}SCL)") (class "Default")
      (node (ref "BUTR_CONN") (pin "2") (pinfunction "2_2") (pintype "bidirectional"))
      (node (ref "TEENSY") (pin "19/A5") (pinfunction "19/A5/T/SCL_19/A5") (pintype "bidirectional"))
    )
    (net (code "130") (name "Net-(TEENSY-20{slash}A6{slash}PWM{slash}SCK1)") (class "Default")
      (node (ref "JOYL") (pin "2") (pinfunction "2_2") (pintype "bidirectional"))
      (node (ref "TEENSY") (pin "20/A6") (pinfunction "20/A6/PWM/SCK1_20/A6") (pintype "bidirectional"))
    )
    (net (code "131") (name "Net-(TEENSY-22{slash}A8{slash}T{slash}PWM{slash}SCL1)") (class "Default")
      (node (ref "R6") (pin "C") (pinfunction "C_C") (pintype "bidirectional"))
      (node (ref "TEENSY") (pin "22/A8") (pinfunction "22/A8/T/PWM/SCL1_22/A8") (pintype "bidirectional"))
      (node (ref "TR1") (pin "G") (pinfunction "G_G") (pintype "bidirectional"))
    )
    (net (code "132") (name "Net-(TEENSY-23{slash}A9{slash}T{slash}PWM{slash}SDA1)") (class "Default")
      (node (ref "R7") (pin "C") (pinfunction "C_C") (pintype "bidirectional"))
      (node (ref "TEENSY") (pin "23/A9") (pinfunction "23/A9/T/PWM/SDA1_23/A9") (pintype "bidirectional"))
      (node (ref "TR2") (pin "G") (pinfunction "G_G") (pintype "bidirectional"))
    )
    (net (code "133") (name "OUTL") (class "Default")
      (node (ref "BOARD_CONN_1") (pin "12") (pinfunction "12_12") (pintype "bidirectional"))
      (node (ref "C24") (pin "A") (pinfunction "A_A") (pintype "bidirectional"))
      (node (ref "C46") (pin "C") (pinfunction "C_C") (pintype "bidirectional"))
      (node (ref "R42") (pin "C") (pinfunction "C_C") (pintype "bidirectional"))
      (node (ref "TP4") (pin "TP") (pinfunction "TP_TP") (pintype "bidirectional"))
    )
    (net (code "134") (name "OUTR") (class "Default")
      (node (ref "BOARD_CONN_1") (pin "13") (pinfunction "13_13") (pintype "bidirectional"))
      (node (ref "C26") (pin "A") (pinfunction "A_A") (pintype "bidirectional"))
      (node (ref "C47") (pin "C") (pinfunction "C_C") (pintype "bidirectional"))
      (node (ref "R43") (pin "C") (pinfunction "C_C") (pintype "bidirectional"))
      (node (ref "TP5") (pin "TP") (pinfunction "TP_TP") (pintype "bidirectional"))
    )
    (net (code "135") (name "PLL_IN") (class "Default")
      (node (ref "AUDIO_DAC") (pin "10") (pinfunction "PLL0_10") (pintype "input"))
      (node (ref "R13") (pin "C") (pinfunction "C_C") (pintype "bidirectional"))
    )
    (net (code "136") (name "PWR1") (class "Default")
      (node (ref "USB_CURLIM") (pin "EN") (pinfunction "EN_EN") (pintype "bidirectional"))
      (node (ref "USB_HUB") (pin "12") (pinfunction "12_12") (pintype "bidirectional"))
    )
    (net (code "137") (name "QON") (class "Default")
      (node (ref "BAT_CHR") (pin "/QON") (pinfunction "/QON_/QON") (pintype "bidirectional"))
      (node (ref "TP10") (pin "TP") (pinfunction "TP_TP") (pintype "bidirectional"))
      (node (ref "TR6") (pin "D") (pinfunction "D_D") (pintype "bidirectional"))
    )
    (net (code "138") (name "REGN") (class "Default")
      (node (ref "BAT_CHR") (pin "REGN") (pinfunction "REGN_REGN") (pintype "bidirectional"))
      (node (ref "C48") (pin "C") (pinfunction "C_C") (pintype "bidirectional"))
      (node (ref "R25") (pin "C") (pinfunction "C_C") (pintype "bidirectional"))
    )
    (net (code "139") (name "RP1.8") (class "Default")
      (node (ref "RPI_PINS1-100") (pin "78") (pinfunction "78_78") (pintype "bidirectional"))
      (node (ref "RPI_PINS1-100") (pin "88") (pinfunction "88_88") (pintype "bidirectional"))
      (node (ref "RPI_PINS1-100") (pin "90") (pinfunction "90_90") (pintype "bidirectional"))
    )
    (net (code "140") (name "RP3.3") (class "Default")
      (node (ref "JOYL") (pin "3") (pinfunction "3_3") (pintype "bidirectional"))
      (node (ref "MICROSD_SWI") (pin "VIN") (pinfunction "VIN_VIN") (pintype "bidirectional"))
      (node (ref "R26") (pin "C") (pinfunction "C_C") (pintype "bidirectional"))
      (node (ref "RPI_PINS1-100") (pin "84") (pinfunction "84_84") (pintype "bidirectional"))
      (node (ref "RPI_PINS1-100") (pin "86") (pinfunction "86_86") (pintype "bidirectional"))
    )
    (net (code "141") (name "RUN_PG") (class "Default")
      (node (ref "BUF3") (pin "A") (pinfunction "A_A") (pintype "bidirectional"))
      (node (ref "RPI_PINS1-100") (pin "92") (pinfunction "92_92") (pintype "bidirectional"))
    )
    (net (code "142") (name "SA0") (class "Default")
      (node (ref "ACCEL") (pin "7") (pinfunction "SA0_7") (pintype "input"))
      (node (ref "R20") (pin "A") (pinfunction "A_A") (pintype "bidirectional"))
    )
    (net (code "143") (name "SCL0") (class "Default")
      (node (ref "LCD_CONN") (pin "5") (pinfunction "5_5") (pintype "bidirectional"))
      (node (ref "RPI_PINS1-100") (pin "80") (pinfunction "80_80") (pintype "bidirectional"))
    )
    (net (code "144") (name "SCL1") (class "Default")
      (node (ref "ACCEL") (pin "4") (pinfunction "SCL_4") (pintype "open_collector"))
      (node (ref "BAT_CHR") (pin "SCL") (pinfunction "SCL_SCL") (pintype "bidirectional"))
      (node (ref "R2") (pin "C") (pinfunction "C_C") (pintype "bidirectional"))
      (node (ref "RPI_PINS1-100") (pin "56") (pinfunction "56_56") (pintype "bidirectional"))
    )
    (net (code "145") (name "SDA0") (class "Default")
      (node (ref "LCD_CONN") (pin "4") (pinfunction "4_4") (pintype "bidirectional"))
      (node (ref "RPI_PINS1-100") (pin "82") (pinfunction "82_82") (pintype "bidirectional"))
    )
    (net (code "146") (name "SDA1") (class "Default")
      (node (ref "ACCEL") (pin "6") (pinfunction "SDA_6") (pintype "open_collector"))
      (node (ref "BAT_CHR") (pin "SDA") (pinfunction "SDA_SDA") (pintype "bidirectional"))
      (node (ref "R1") (pin "C") (pinfunction "C_C") (pintype "bidirectional"))
      (node (ref "RPI_PINS1-100") (pin "58") (pinfunction "58_58") (pintype "bidirectional"))
    )
    (net (code "147") (name "SDIO_CLK") (class "Default")
      (node (ref "RPI_PINS1-100") (pin "46") (pinfunction "46_46") (pintype "bidirectional"))
      (node (ref "WIFI/BT") (pin "15") (pinfunction "15_15") (pintype "bidirectional"))
    )
    (net (code "148") (name "SDIO_CMD") (class "Default")
      (node (ref "RPI_PINS1-100") (pin "47") (pinfunction "47_47") (pintype "bidirectional"))
      (node (ref "WIFI/BT") (pin "12") (pinfunction "12_12") (pintype "bidirectional"))
    )
    (net (code "149") (name "SDIO_DATA0") (class "Default")
      (node (ref "RPI_PINS1-100") (pin "45") (pinfunction "45_45") (pintype "bidirectional"))
      (node (ref "WIFI/BT") (pin "9") (pinfunction "9_9") (pintype "bidirectional"))
    )
    (net (code "150") (name "SDIO_DATA1") (class "Default")
      (node (ref "RPI_PINS1-100") (pin "41") (pinfunction "41_41") (pintype "bidirectional"))
      (node (ref "WIFI/BT") (pin "10") (pinfunction "10_10") (pintype "bidirectional"))
    )
    (net (code "151") (name "SDIO_DATA2") (class "Default")
      (node (ref "RPI_PINS1-100") (pin "24") (pinfunction "24_24") (pintype "bidirectional"))
      (node (ref "WIFI/BT") (pin "13") (pinfunction "13_13") (pintype "bidirectional"))
    )
    (net (code "152") (name "SDIO_DATA3") (class "Default")
      (node (ref "RPI_PINS1-100") (pin "48") (pinfunction "48_48") (pintype "bidirectional"))
      (node (ref "WIFI/BT") (pin "11") (pinfunction "11_11") (pintype "bidirectional"))
    )
    (net (code "153") (name "SD_CLK") (class "Default")
      (node (ref "MICROSD") (pin "CLK") (pinfunction "CLK_CLK") (pintype "bidirectional"))
      (node (ref "RPI_PINS1-100") (pin "57") (pinfunction "57_57") (pintype "bidirectional"))
    )
    (net (code "154") (name "SD_CMD") (class "Default")
      (node (ref "MICROSD") (pin "CMD") (pinfunction "CMD_CMD") (pintype "bidirectional"))
      (node (ref "RPI_PINS1-100") (pin "62") (pinfunction "62_62") (pintype "bidirectional"))
    )
    (net (code "155") (name "SD_DAT0") (class "Default")
      (node (ref "MICROSD") (pin "DAT0") (pinfunction "DAT0_DAT0") (pintype "bidirectional"))
      (node (ref "RPI_PINS1-100") (pin "63") (pinfunction "63_63") (pintype "bidirectional"))
    )
    (net (code "156") (name "SD_DAT1") (class "Default")
      (node (ref "MICROSD") (pin "DAT1") (pinfunction "DAT1_DAT1") (pintype "bidirectional"))
      (node (ref "RPI_PINS1-100") (pin "67") (pinfunction "67_67") (pintype "bidirectional"))
    )
    (net (code "157") (name "SD_DAT2") (class "Default")
      (node (ref "MICROSD") (pin "DAT2") (pinfunction "DAT2_DAT2") (pintype "bidirectional"))
      (node (ref "RPI_PINS1-100") (pin "69") (pinfunction "69_69") (pintype "bidirectional"))
    )
    (net (code "158") (name "SD_DAT3") (class "Default")
      (node (ref "MICROSD") (pin "DAT3") (pinfunction "DAT3_DAT3") (pintype "bidirectional"))
      (node (ref "RPI_PINS1-100") (pin "61") (pinfunction "61_61") (pintype "bidirectional"))
    )
    (net (code "159") (name "SD_PWR") (class "Default")
      (node (ref "C15") (pin "C") (pinfunction "C_C") (pintype "bidirectional"))
      (node (ref "MICROSD") (pin "VDD") (pinfunction "VDD_VDD") (pintype "bidirectional"))
      (node (ref "MICROSD_SWI") (pin "VOUT") (pinfunction "VOUT_VOUT") (pintype "bidirectional"))
    )
    (net (code "160") (name "SD_PWR_ON") (class "Default")
      (node (ref "MICROSD_SWI") (pin "EN") (pinfunction "EN_EN") (pintype "bidirectional"))
      (node (ref "R26") (pin "A") (pinfunction "A_A") (pintype "bidirectional"))
      (node (ref "RPI_PINS1-100") (pin "75") (pinfunction "75_75") (pintype "bidirectional"))
      (node (ref "TP6") (pin "TP") (pinfunction "TP_TP") (pintype "bidirectional"))
    )
    (net (code "161") (name "SFOR0") (class "Default")
      (node (ref "AUDIO_DAC") (pin "11") (pinfunction "SFOR0_11") (pintype "input"))
      (node (ref "R10") (pin "C") (pinfunction "C_C") (pintype "bidirectional"))
    )
    (net (code "162") (name "SFOR1") (class "Default")
      (node (ref "AUDIO_DAC") (pin "7") (pinfunction "SFOR1_7") (pintype "input"))
      (node (ref "R9") (pin "C") (pinfunction "C_C") (pintype "bidirectional"))
    )
    (net (code "163") (name "STAT") (class "Default")
      (node (ref "BAT_CHR") (pin "STAT") (pinfunction "STAT_STAT") (pintype "bidirectional"))
      (node (ref "BUF1") (pin "A") (pinfunction "A_A") (pintype "bidirectional"))
      (node (ref "R4") (pin "C") (pinfunction "C_C") (pintype "bidirectional"))
      (node (ref "TP9") (pin "TP") (pinfunction "TP_TP") (pintype "bidirectional"))
    )
    (net (code "164") (name "SUSCLK") (class "Default")
      (node (ref "CLK-32.768") (pin "OUT") (pinfunction "OUT_OUT") (pintype "bidirectional"))
      (node (ref "WIFI/BT") (pin "34") (pinfunction "34_34") (pintype "bidirectional"))
    )
    (net (code "165") (name "SW") (class "Default")
      (node (ref "BAT_CHR") (pin "SW1") (pinfunction "SW_SW1") (pintype "bidirectional"))
      (node (ref "BAT_CHR") (pin "SW2") (pinfunction "SW_SW2") (pintype "bidirectional"))
      (node (ref "C49") (pin "C") (pinfunction "C_C") (pintype "bidirectional"))
      (node (ref "L1") (pin "A") (pinfunction "A_A") (pintype "bidirectional"))
    )
    (net (code "166") (name "SYS") (class "Default")
      (node (ref "3.3V-1.8V_REG") (pin "EN1") (pinfunction "EN1_EN1") (pintype "bidirectional"))
      (node (ref "3.3V-1.8V_REG") (pin "VIN1") (pinfunction "VIN1_VIN1") (pintype "bidirectional"))
      (node (ref "3.3V-1.8V_REG") (pin "VIN2") (pinfunction "VIN2_VIN2") (pintype "bidirectional"))
      (node (ref "5V_REG") (pin "EN") (pinfunction "EN_EN") (pintype "bidirectional"))
      (node (ref "5V_REG") (pin "VBAT") (pinfunction "VBAT_VBAT") (pintype "bidirectional"))
      (node (ref "BAT_CHR") (pin "SYS1") (pinfunction "SYS_SYS1") (pintype "bidirectional"))
      (node (ref "BAT_CHR") (pin "SYS2") (pinfunction "SYS_SYS2") (pintype "bidirectional"))
      (node (ref "C3") (pin "C") (pinfunction "C_C") (pintype "bidirectional"))
      (node (ref "C30") (pin "C") (pinfunction "C_C") (pintype "bidirectional"))
      (node (ref "C4") (pin "C") (pinfunction "C_C") (pintype "bidirectional"))
      (node (ref "C5") (pin "C") (pinfunction "C_C") (pintype "bidirectional"))
      (node (ref "C59") (pin "C") (pinfunction "C_C") (pintype "bidirectional"))
      (node (ref "C60") (pin "C") (pinfunction "C_C") (pintype "bidirectional"))
      (node (ref "L1") (pin "C") (pinfunction "C_C") (pintype "bidirectional"))
      (node (ref "L2") (pin "A") (pinfunction "A_A") (pintype "bidirectional"))
      (node (ref "R44") (pin "A") (pinfunction "A_A") (pintype "bidirectional"))
      (node (ref "TP1") (pin "TP") (pinfunction "TP_TP") (pintype "bidirectional"))
    )
    (net (code "167") (name "SYSCLK_IN") (class "Default")
      (node (ref "AUDIO_DAC") (pin "6") (pinfunction "SYSCLK/PLL1_6") (pintype "input"))
      (node (ref "R8") (pin "C") (pinfunction "C_C") (pintype "bidirectional"))
    )
    (net (code "168") (name "T3.3") (class "Default")
      (node (ref "JOYR") (pin "3") (pinfunction "3_3") (pintype "bidirectional"))
      (node (ref "TEENSY") (pin "3.3V") (pinfunction "3.3V_3.3V") (pintype "power_in"))
    )
    (net (code "169") (name "TD+") (class "Default")
      (node (ref "TEENSYUSB") (pin "2") (pinfunction "2_2") (pintype "bidirectional"))
      (node (ref "USB_HUB") (pin "2") (pinfunction "2_2") (pintype "bidirectional"))
    )
    (net (code "170") (name "TD-") (class "Default")
      (node (ref "TEENSYUSB") (pin "3") (pinfunction "3_3") (pintype "bidirectional"))
      (node (ref "USB_HUB") (pin "1") (pinfunction "1_1") (pintype "bidirectional"))
    )
    (net (code "171") (name "USB2_N") (class "Default")
      (node (ref "RPI_PINS101-200") (pin "3") (pinfunction "3_3") (pintype "bidirectional"))
      (node (ref "USB_SWI") (pin "D-") (pinfunction "D-_D-") (pintype "bidirectional"))
    )
    (net (code "172") (name "USB2_P") (class "Default")
      (node (ref "RPI_PINS101-200") (pin "5") (pinfunction "5_5") (pintype "bidirectional"))
      (node (ref "USB_SWI") (pin "D+") (pinfunction "D+_D+") (pintype "bidirectional"))
    )
    (net (code "173") (name "USBD_N") (class "Default")
      (node (ref "USB_IN") (pin "D+") (pinfunction "D+_D+") (pintype "bidirectional"))
      (node (ref "USB_POE") (pin "D2+") (pinfunction "D2+_D2+") (pintype "bidirectional"))
      (node (ref "USB_SWI") (pin "HSD2+") (pinfunction "HSD2+_HSD2+") (pintype "bidirectional"))
    )
    (net (code "174") (name "USBD_P") (class "Default")
      (node (ref "USB_IN") (pin "D-") (pinfunction "D-_D-") (pintype "bidirectional"))
      (node (ref "USB_POE") (pin "D2-") (pinfunction "D2-_D2-") (pintype "bidirectional"))
      (node (ref "USB_SWI") (pin "HSD2-") (pinfunction "HSD2-_HSD2-") (pintype "bidirectional"))
    )
    (net (code "175") (name "USBH_N") (class "Default")
      (node (ref "USB_HUB") (pin "30") (pinfunction "30_30") (pintype "bidirectional"))
      (node (ref "USB_SWI") (pin "HSD1-") (pinfunction "HSD1-_HSD1-") (pintype "bidirectional"))
    )
    (net (code "176") (name "USBH_P") (class "Default")
      (node (ref "USB_HUB") (pin "31") (pinfunction "31_31") (pintype "bidirectional"))
      (node (ref "USB_SWI") (pin "HSD1+") (pinfunction "HSD1+_HSD1+") (pintype "bidirectional"))
    )
    (net (code "177") (name "USBOTG") (class "Default")
      (node (ref "R23") (pin "C") (pinfunction "C_C") (pintype "bidirectional"))
      (node (ref "R24") (pin "A") (pinfunction "A_A") (pintype "bidirectional"))
      (node (ref "RPI_PINS101-200") (pin "1") (pinfunction "1_1") (pintype "bidirectional"))
      (node (ref "USB_SWI") (pin "SEL") (pinfunction "SEL_SEL") (pintype "bidirectional"))
    )
    (net (code "178") (name "VBUS") (class "Default")
      (node (ref "BAT_CHR") (pin "VBUS") (pinfunction "VBUS_VBUS") (pintype "bidirectional"))
      (node (ref "C28") (pin "C") (pinfunction "C_C") (pintype "bidirectional"))
      (node (ref "USB_PWR") (pin "VBUS_1") (pinfunction "VBUS_VBUS_1") (pintype "bidirectional"))
      (node (ref "USB_PWR") (pin "VBUS_2") (pinfunction "VBUS_VBUS_2") (pintype "bidirectional"))
      (node (ref "USB_PWR") (pin "VBUS_3") (pinfunction "VBUS_VBUS_3") (pintype "bidirectional"))
      (node (ref "USB_PWR") (pin "VBUS_4") (pinfunction "VBUS_VBUS_4") (pintype "bidirectional"))
    )
    (net (code "179") (name "VBUS1") (class "Default")
      (node (ref "BOARD_CONN_1") (pin "2") (pinfunction "2_2") (pintype "bidirectional"))
      (node (ref "BOARD_CONN_1") (pin "3") (pinfunction "3_3") (pintype "bidirectional"))
      (node (ref "BOARD_CONN_1") (pin "4") (pinfunction "4_4") (pintype "bidirectional"))
      (node (ref "BOARD_CONN_1") (pin "5") (pinfunction "5_5") (pintype "bidirectional"))
      (node (ref "BOARD_CONN_1") (pin "6") (pinfunction "6_6") (pintype "bidirectional"))
      (node (ref "C1") (pin "C") (pinfunction "C_C") (pintype "bidirectional"))
      (node (ref "C21") (pin "C") (pinfunction "C_C") (pintype "bidirectional"))
      (node (ref "TEENSY") (pin "VIN") (pinfunction "VIN_VIN") (pintype "power_in"))
      (node (ref "TEENSYUSB") (pin "4") (pinfunction "4_4") (pintype "bidirectional"))
      (node (ref "TP14") (pin "TP") (pinfunction "TP_TP") (pintype "bidirectional"))
      (node (ref "USB_CURLIM") (pin "OUT") (pinfunction "OUT_OUT") (pintype "bidirectional"))
    )
    (net (code "180") (name "VREF1.8") (class "Default")
      (node (ref "3.3V-1.8V_REG") (pin "FB2") (pinfunction "FB2_FB2") (pintype "bidirectional"))
      (node (ref "C10") (pin "C") (pinfunction "C_C") (pintype "bidirectional"))
      (node (ref "C29") (pin "A") (pinfunction "A_A") (pintype "bidirectional"))
      (node (ref "C61") (pin "C") (pinfunction "C_C") (pintype "bidirectional"))
      (node (ref "C63") (pin "C") (pinfunction "C_C") (pintype "bidirectional"))
      (node (ref "CLK-32.768") (pin "OE") (pinfunction "OE_OE") (pintype "bidirectional"))
      (node (ref "CLK-32.768") (pin "VDD") (pinfunction "VDD_VDD") (pintype "bidirectional"))
      (node (ref "L3") (pin "C") (pinfunction "C_C") (pintype "bidirectional"))
      (node (ref "LEVEL_ADJ") (pin "VCCA") (pinfunction "VCCA_VCCA") (pintype "bidirectional"))
      (node (ref "TP20") (pin "TP") (pinfunction "TP_TP") (pintype "bidirectional"))
      (node (ref "WIFI/BT") (pin "30") (pinfunction "30_30") (pintype "bidirectional"))
      (node (ref "WIFI/BT") (pin "4") (pinfunction "4_4") (pintype "bidirectional"))
      (node (ref "WIFI/BT") (pin "5") (pinfunction "5_5") (pintype "bidirectional"))
    )
    (net (code "181") (name "VREF3.3") (class "Default")
      (node (ref "3.3V-1.8V_REG") (pin "FB1") (pinfunction "FB1_FB1") (pintype "bidirectional"))
      (node (ref "ACCEL") (pin "1") (pinfunction "VDDIO_1") (pintype "power_in"))
      (node (ref "ACCEL") (pin "14") (pinfunction "VDD_14") (pintype "power_in"))
      (node (ref "AUDIO_AMP") (pin "P$11") (pinfunction "PVDD_P$11") (pintype "power_in"))
      (node (ref "AUDIO_AMP") (pin "P$12") (pinfunction "PVDD_P$12") (pintype "power_in"))
      (node (ref "AUDIO_DAC") (pin "4") (pinfunction "VDDD_4") (pintype "power_in"))
      (node (ref "BOARD_CONN_1") (pin "1") (pinfunction "1_1") (pintype "bidirectional"))
      (node (ref "BUF1") (pin "VCC") (pinfunction "VCC_VCC") (pintype "bidirectional"))
      (node (ref "BUF2") (pin "VCC") (pinfunction "VCC_VCC") (pintype "bidirectional"))
      (node (ref "C11") (pin "C") (pinfunction "C_C") (pintype "bidirectional"))
      (node (ref "C14") (pin "C") (pinfunction "C_C") (pintype "bidirectional"))
      (node (ref "C17") (pin "C") (pinfunction "C_C") (pintype "bidirectional"))
      (node (ref "C18") (pin "C") (pinfunction "C_C") (pintype "bidirectional"))
      (node (ref "C19") (pin "C") (pinfunction "C_C") (pintype "bidirectional"))
      (node (ref "C31") (pin "A") (pinfunction "A_A") (pintype "bidirectional"))
      (node (ref "C32") (pin "C") (pinfunction "C_C") (pintype "bidirectional"))
      (node (ref "C33") (pin "C") (pinfunction "C_C") (pintype "bidirectional"))
      (node (ref "C34") (pin "C") (pinfunction "C_C") (pintype "bidirectional"))
      (node (ref "C35") (pin "C") (pinfunction "C_C") (pintype "bidirectional"))
      (node (ref "C38") (pin "C") (pinfunction "C_C") (pintype "bidirectional"))
      (node (ref "C41") (pin "C") (pinfunction "C_C") (pintype "bidirectional"))
      (node (ref "C42") (pin "C") (pinfunction "C_C") (pintype "bidirectional"))
      (node (ref "C43") (pin "C") (pinfunction "C_C") (pintype "bidirectional"))
      (node (ref "C44") (pin "C") (pinfunction "C_C") (pintype "bidirectional"))
      (node (ref "C58") (pin "C") (pinfunction "C_C") (pintype "bidirectional"))
      (node (ref "C62") (pin "C") (pinfunction "C_C") (pintype "bidirectional"))
      (node (ref "C64") (pin "C") (pinfunction "C_C") (pintype "bidirectional"))
      (node (ref "D1") (pin "C") (pinfunction "C_C") (pintype "bidirectional"))
      (node (ref "D2") (pin "C") (pinfunction "C_C") (pintype "bidirectional"))
      (node (ref "D3") (pin "C") (pinfunction "C_C") (pintype "bidirectional"))
      (node (ref "FAN_CONN") (pin "1") (pinfunction "1_1") (pintype "bidirectional"))
      (node (ref "FB1") (pin "2") (pinfunction "P$2_2") (pintype "passive"))
      (node (ref "L4") (pin "C") (pinfunction "C_C") (pintype "bidirectional"))
      (node (ref "LCD_CONN") (pin "1") (pinfunction "1_1") (pintype "bidirectional"))
      (node (ref "LCD_CONN") (pin "2") (pinfunction "2_2") (pintype "bidirectional"))
      (node (ref "LEVEL_ADJ") (pin "VCCB") (pinfunction "VCCB_VCCB") (pintype "bidirectional"))
      (node (ref "MOT_CONN") (pin "1") (pinfunction "1_1") (pintype "bidirectional"))
      (node (ref "MOT_CONN") (pin "3") (pinfunction "3_3") (pintype "bidirectional"))
      (node (ref "R1") (pin "A") (pinfunction "A_A") (pintype "bidirectional"))
      (node (ref "R14") (pin "C") (pinfunction "C_C") (pintype "bidirectional"))
      (node (ref "R17") (pin "C") (pinfunction "C_C") (pintype "bidirectional"))
      (node (ref "R18") (pin "C") (pinfunction "C_C") (pintype "bidirectional"))
      (node (ref "R2") (pin "A") (pinfunction "A_A") (pintype "bidirectional"))
      (node (ref "R20") (pin "C") (pinfunction "C_C") (pintype "bidirectional"))
      (node (ref "R3") (pin "A") (pinfunction "A_A") (pintype "bidirectional"))
      (node (ref "R35") (pin "C") (pinfunction "C_C") (pintype "bidirectional"))
      (node (ref "R39") (pin "C") (pinfunction "C_C") (pintype "bidirectional"))
      (node (ref "R4") (pin "A") (pinfunction "A_A") (pintype "bidirectional"))
      (node (ref "R40") (pin "C") (pinfunction "C_C") (pintype "bidirectional"))
      (node (ref "R48") (pin "C") (pinfunction "C_C") (pintype "bidirectional"))
      (node (ref "R5") (pin "A") (pinfunction "A_A") (pintype "bidirectional"))
      (node (ref "TP3") (pin "TP") (pinfunction "TP_TP") (pintype "bidirectional"))
      (node (ref "USB_HUB") (pin "10") (pinfunction "10_10") (pintype "bidirectional"))
      (node (ref "USB_HUB") (pin "15") (pinfunction "15_15") (pintype "bidirectional"))
      (node (ref "USB_HUB") (pin "23") (pinfunction "23_23") (pintype "bidirectional"))
      (node (ref "USB_HUB") (pin "27") (pinfunction "27_27") (pintype "bidirectional"))
      (node (ref "USB_HUB") (pin "29") (pinfunction "29_29") (pintype "bidirectional"))
      (node (ref "USB_HUB") (pin "36") (pinfunction "36_36") (pintype "bidirectional"))
      (node (ref "USB_HUB") (pin "5") (pinfunction "5_5") (pintype "bidirectional"))
      (node (ref "USB_SWI") (pin "VCC") (pinfunction "VCC_VCC") (pintype "bidirectional"))
      (node (ref "WIFI/BT") (pin "17") (pinfunction "17_17") (pintype "bidirectional"))
      (node (ref "WIFI/BT") (pin "18") (pinfunction "18_18") (pintype "bidirectional"))
      (node (ref "WIFI/BT") (pin "7") (pinfunction "7_7") (pintype "bidirectional"))
    )
    (net (code "182") (name "VREF5.0") (class "Default")
      (node (ref "5V_REG") (pin "VOUT1") (pinfunction "VOUT_VOUT1") (pintype "bidirectional"))
      (node (ref "5V_REG") (pin "VOUT2") (pinfunction "VOUT_VOUT2") (pintype "bidirectional"))
      (node (ref "5V_REG") (pin "VOUT3") (pinfunction "VOUT_VOUT3") (pintype "bidirectional"))
      (node (ref "BUF3") (pin "VCC") (pinfunction "VCC_VCC") (pintype "bidirectional"))
      (node (ref "C20") (pin "C") (pinfunction "C_C") (pintype "bidirectional"))
      (node (ref "C39") (pin "C") (pinfunction "C_C") (pintype "bidirectional"))
      (node (ref "C50") (pin "A") (pinfunction "A_A") (pintype "bidirectional"))
      (node (ref "C51") (pin "C") (pinfunction "C_C") (pintype "bidirectional"))
      (node (ref "C6") (pin "C") (pinfunction "C_C") (pintype "bidirectional"))
      (node (ref "C7") (pin "C") (pinfunction "C_C") (pintype "bidirectional"))
      (node (ref "C8") (pin "C") (pinfunction "C_C") (pintype "bidirectional"))
      (node (ref "HDMI_CURLIM") (pin "IN") (pinfunction "IN_IN") (pintype "bidirectional"))
      (node (ref "LCD_PWR_CONN") (pin "1") (pinfunction "1_1") (pintype "bidirectional"))
      (node (ref "R16") (pin "C") (pinfunction "C_C") (pintype "bidirectional"))
      (node (ref "R46") (pin "C") (pinfunction "C_C") (pintype "bidirectional"))
      (node (ref "RPI_PINS1-100") (pin "77") (pinfunction "77_77") (pintype "bidirectional"))
      (node (ref "RPI_PINS1-100") (pin "79") (pinfunction "79_79") (pintype "bidirectional"))
      (node (ref "RPI_PINS1-100") (pin "81") (pinfunction "81_81") (pintype "bidirectional"))
      (node (ref "RPI_PINS1-100") (pin "83") (pinfunction "83_83") (pintype "bidirectional"))
      (node (ref "RPI_PINS1-100") (pin "85") (pinfunction "85_85") (pintype "bidirectional"))
      (node (ref "RPI_PINS1-100") (pin "87") (pinfunction "87_87") (pintype "bidirectional"))
      (node (ref "TP2") (pin "TP") (pinfunction "TP_TP") (pintype "bidirectional"))
      (node (ref "USB_CURLIM") (pin "IN") (pinfunction "IN_IN") (pintype "bidirectional"))
    )
    (net (code "183") (name "WL_REG_ON") (class "Default")
      (node (ref "RPI_PINS1-100") (pin "30") (pinfunction "30_30") (pintype "bidirectional"))
      (node (ref "WIFI/BT") (pin "33") (pinfunction "33_33") (pintype "bidirectional"))
    )
    (net (code "184") (name "WORDSEL_IN") (class "Default")
      (node (ref "LEVEL_ADJ") (pin "A1") (pinfunction "A1_A1") (pintype "bidirectional"))
      (node (ref "RPI_PINS1-100") (pin "26") (pinfunction "26_26") (pintype "bidirectional"))
      (node (ref "TP18") (pin "TP") (pinfunction "TP_TP") (pintype "bidirectional"))
    )
    (net (code "185") (name "unconnected-(3.3V-1.8V_REG-PadNC1)") (class "Default")
      (node (ref "3.3V-1.8V_REG") (pin "NC1") (pinfunction "NC1_NC1") (pintype "no_connect"))
    )
    (net (code "186") (name "unconnected-(3.3V-1.8V_REG-PadNC2)") (class "Default")
      (node (ref "3.3V-1.8V_REG") (pin "NC2") (pinfunction "NC2_NC2") (pintype "no_connect"))
    )
    (net (code "187") (name "unconnected-(5V_REG-PadNC)") (class "Default")
      (node (ref "5V_REG") (pin "NC") (pinfunction "NC_NC") (pintype "no_connect"))
    )
    (net (code "188") (name "unconnected-(ACCEL-INT1-Pad11)") (class "Default")
      (node (ref "ACCEL") (pin "11") (pinfunction "INT1_11") (pintype "output"))
    )
    (net (code "189") (name "unconnected-(ACCEL-INT2-Pad9)") (class "Default")
      (node (ref "ACCEL") (pin "9") (pinfunction "INT2_9") (pintype "output"))
    )
    (net (code "190") (name "unconnected-(ACCEL-NC-Pad3)") (class "Default")
      (node (ref "ACCEL") (pin "3") (pinfunction "NC_3") (pintype "no_connect"))
    )
    (net (code "191") (name "unconnected-(ACCEL-NC-Pad8)") (class "Default")
      (node (ref "ACCEL") (pin "8") (pinfunction "NC_8") (pintype "no_connect"))
    )
    (net (code "192") (name "unconnected-(ACCEL-NC-Pad13)") (class "Default")
      (node (ref "ACCEL") (pin "13") (pinfunction "NC_13") (pintype "no_connect"))
    )
    (net (code "193") (name "unconnected-(ACCEL-NC-Pad15)") (class "Default")
      (node (ref "ACCEL") (pin "15") (pinfunction "NC_15") (pintype "no_connect"))
    )
    (net (code "194") (name "unconnected-(ACCEL-NC-Pad16)") (class "Default")
      (node (ref "ACCEL") (pin "16") (pinfunction "NC_16") (pintype "no_connect"))
    )
    (net (code "195") (name "unconnected-(BUF1-PadNC)") (class "Default")
      (node (ref "BUF1") (pin "NC") (pinfunction "NC_NC") (pintype "no_connect"))
    )
    (net (code "196") (name "unconnected-(BUF2-PadNC)") (class "Default")
      (node (ref "BUF2") (pin "NC") (pinfunction "NC_NC") (pintype "no_connect"))
    )
    (net (code "197") (name "unconnected-(BUF3-PadNC)") (class "Default")
      (node (ref "BUF3") (pin "NC") (pinfunction "NC_NC") (pintype "no_connect"))
    )
    (net (code "198") (name "unconnected-(HDMI_CONN-Pad17)") (class "Default")
      (node (ref "HDMI_CONN") (pin "17") (pinfunction "17_17") (pintype "bidirectional"))
    )
    (net (code "199") (name "unconnected-(LEVEL_ADJ-PadA4)") (class "Default")
      (node (ref "LEVEL_ADJ") (pin "A4") (pinfunction "A4_A4") (pintype "bidirectional"))
    )
    (net (code "200") (name "unconnected-(LEVEL_ADJ-PadB4)") (class "Default")
      (node (ref "LEVEL_ADJ") (pin "B4") (pinfunction "B4_B4") (pintype "bidirectional"))
    )
    (net (code "201") (name "unconnected-(LEVEL_ADJ-PadNC1)") (class "Default")
      (node (ref "LEVEL_ADJ") (pin "NC1") (pinfunction "NC1_NC1") (pintype "no_connect"))
    )
    (net (code "202") (name "unconnected-(LEVEL_ADJ-PadNC2)") (class "Default")
      (node (ref "LEVEL_ADJ") (pin "NC2") (pinfunction "NC2_NC2") (pintype "no_connect"))
    )
    (net (code "203") (name "unconnected-(MICROSD_SWI-Pad{slash}FLG)") (class "Default")
      (node (ref "MICROSD_SWI") (pin "/FLG") (pinfunction "/FLG_/FLG") (pintype "bidirectional"))
    )
    (net (code "204") (name "unconnected-(RPI_PINS1-100-Pad16)") (class "Default")
      (node (ref "RPI_PINS1-100") (pin "16") (pinfunction "16_16") (pintype "bidirectional"))
    )
    (net (code "205") (name "unconnected-(RPI_PINS1-100-Pad18)") (class "Default")
      (node (ref "RPI_PINS1-100") (pin "18") (pinfunction "18_18") (pintype "bidirectional"))
    )
    (net (code "206") (name "unconnected-(RPI_PINS1-100-Pad19)") (class "Default")
      (node (ref "RPI_PINS1-100") (pin "19") (pinfunction "19_19") (pintype "bidirectional"))
    )
    (net (code "207") (name "unconnected-(RPI_PINS1-100-Pad20)") (class "Default")
      (node (ref "RPI_PINS1-100") (pin "20") (pinfunction "20_20") (pintype "bidirectional"))
    )
    (net (code "208") (name "unconnected-(RPI_PINS1-100-Pad21)") (class "Default")
      (node (ref "RPI_PINS1-100") (pin "21") (pinfunction "21_21") (pintype "bidirectional"))
    )
    (net (code "209") (name "unconnected-(RPI_PINS1-100-Pad27)") (class "Default")
      (node (ref "RPI_PINS1-100") (pin "27") (pinfunction "27_27") (pintype "bidirectional"))
    )
    (net (code "210") (name "unconnected-(RPI_PINS1-100-Pad28)") (class "Default")
      (node (ref "RPI_PINS1-100") (pin "28") (pinfunction "28_28") (pintype "bidirectional"))
    )
    (net (code "211") (name "unconnected-(RPI_PINS1-100-Pad35)") (class "Default")
      (node (ref "RPI_PINS1-100") (pin "35") (pinfunction "35_35") (pintype "bidirectional"))
    )
    (net (code "212") (name "unconnected-(RPI_PINS1-100-Pad36)") (class "Default")
      (node (ref "RPI_PINS1-100") (pin "36") (pinfunction "36_36") (pintype "bidirectional"))
    )
    (net (code "213") (name "unconnected-(RPI_PINS1-100-Pad54)") (class "Default")
      (node (ref "RPI_PINS1-100") (pin "54") (pinfunction "54_54") (pintype "bidirectional"))
    )
    (net (code "214") (name "unconnected-(RPI_PINS1-100-Pad64)") (class "Default")
      (node (ref "RPI_PINS1-100") (pin "64") (pinfunction "64_64") (pintype "bidirectional"))
    )
    (net (code "215") (name "unconnected-(RPI_PINS1-100-Pad68)") (class "Default")
      (node (ref "RPI_PINS1-100") (pin "68") (pinfunction "68_68") (pintype "bidirectional"))
    )
    (net (code "216") (name "unconnected-(RPI_PINS1-100-Pad70)") (class "Default")
      (node (ref "RPI_PINS1-100") (pin "70") (pinfunction "70_70") (pintype "bidirectional"))
    )
    (net (code "217") (name "unconnected-(RPI_PINS1-100-Pad72)") (class "Default")
      (node (ref "RPI_PINS1-100") (pin "72") (pinfunction "72_72") (pintype "bidirectional"))
    )
    (net (code "218") (name "unconnected-(RPI_PINS1-100-Pad73)") (class "Default")
      (node (ref "RPI_PINS1-100") (pin "73") (pinfunction "73_73") (pintype "bidirectional"))
    )
    (net (code "219") (name "unconnected-(RPI_PINS1-100-Pad76)") (class "Default")
      (node (ref "RPI_PINS1-100") (pin "76") (pinfunction "76_76") (pintype "bidirectional"))
    )
    (net (code "220") (name "unconnected-(RPI_PINS1-100-Pad89)") (class "Default")
      (node (ref "RPI_PINS1-100") (pin "89") (pinfunction "89_89") (pintype "bidirectional"))
    )
    (net (code "221") (name "unconnected-(RPI_PINS1-100-Pad91)") (class "Default")
      (node (ref "RPI_PINS1-100") (pin "91") (pinfunction "91_91") (pintype "bidirectional"))
    )
    (net (code "222") (name "unconnected-(RPI_PINS1-100-Pad94)") (class "Default")
      (node (ref "RPI_PINS1-100") (pin "94") (pinfunction "94_94") (pintype "bidirectional"))
    )
    (net (code "223") (name "unconnected-(RPI_PINS1-100-Pad96)") (class "Default")
      (node (ref "RPI_PINS1-100") (pin "96") (pinfunction "96_96") (pintype "bidirectional"))
    )
    (net (code "224") (name "unconnected-(RPI_PINS1-100-Pad97)") (class "Default")
      (node (ref "RPI_PINS1-100") (pin "97") (pinfunction "97_97") (pintype "bidirectional"))
    )
    (net (code "225") (name "unconnected-(RPI_PINS101-200-Pad2)") (class "Default")
      (node (ref "RPI_PINS101-200") (pin "2") (pinfunction "2_2") (pintype "bidirectional"))
    )
    (net (code "226") (name "unconnected-(RPI_PINS101-200-Pad4)") (class "Default")
      (node (ref "RPI_PINS101-200") (pin "4") (pinfunction "4_4") (pintype "bidirectional"))
    )
    (net (code "227") (name "unconnected-(RPI_PINS101-200-Pad6)") (class "Default")
      (node (ref "RPI_PINS101-200") (pin "6") (pinfunction "6_6") (pintype "bidirectional"))
    )
    (net (code "228") (name "unconnected-(RPI_PINS101-200-Pad9)") (class "Default")
      (node (ref "RPI_PINS101-200") (pin "9") (pinfunction "9_9") (pintype "bidirectional"))
    )
    (net (code "229") (name "unconnected-(RPI_PINS101-200-Pad10)") (class "Default")
      (node (ref "RPI_PINS101-200") (pin "10") (pinfunction "10_10") (pintype "bidirectional"))
    )
    (net (code "230") (name "unconnected-(RPI_PINS101-200-Pad11)") (class "Default")
      (node (ref "RPI_PINS101-200") (pin "11") (pinfunction "11_11") (pintype "bidirectional"))
    )
    (net (code "231") (name "unconnected-(RPI_PINS101-200-Pad12)") (class "Default")
      (node (ref "RPI_PINS101-200") (pin "12") (pinfunction "12_12") (pintype "bidirectional"))
    )
    (net (code "232") (name "unconnected-(RPI_PINS101-200-Pad15)") (class "Default")
      (node (ref "RPI_PINS101-200") (pin "15") (pinfunction "15_15") (pintype "bidirectional"))
    )
    (net (code "233") (name "unconnected-(RPI_PINS101-200-Pad16)") (class "Default")
      (node (ref "RPI_PINS101-200") (pin "16") (pinfunction "16_16") (pintype "bidirectional"))
    )
    (net (code "234") (name "unconnected-(RPI_PINS101-200-Pad17)") (class "Default")
      (node (ref "RPI_PINS101-200") (pin "17") (pinfunction "17_17") (pintype "bidirectional"))
    )
    (net (code "235") (name "unconnected-(RPI_PINS101-200-Pad18)") (class "Default")
      (node (ref "RPI_PINS101-200") (pin "18") (pinfunction "18_18") (pintype "bidirectional"))
    )
    (net (code "236") (name "unconnected-(RPI_PINS101-200-Pad21)") (class "Default")
      (node (ref "RPI_PINS101-200") (pin "21") (pinfunction "21_21") (pintype "bidirectional"))
    )
    (net (code "237") (name "unconnected-(RPI_PINS101-200-Pad22)") (class "Default")
      (node (ref "RPI_PINS101-200") (pin "22") (pinfunction "22_22") (pintype "bidirectional"))
    )
    (net (code "238") (name "unconnected-(RPI_PINS101-200-Pad23)") (class "Default")
      (node (ref "RPI_PINS101-200") (pin "23") (pinfunction "23_23") (pintype "bidirectional"))
    )
    (net (code "239") (name "unconnected-(RPI_PINS101-200-Pad24)") (class "Default")
      (node (ref "RPI_PINS101-200") (pin "24") (pinfunction "24_24") (pintype "bidirectional"))
    )
    (net (code "240") (name "unconnected-(RPI_PINS101-200-Pad27)") (class "Default")
      (node (ref "RPI_PINS101-200") (pin "27") (pinfunction "27_27") (pintype "bidirectional"))
    )
    (net (code "241") (name "unconnected-(RPI_PINS101-200-Pad28)") (class "Default")
      (node (ref "RPI_PINS101-200") (pin "28") (pinfunction "28_28") (pintype "bidirectional"))
    )
    (net (code "242") (name "unconnected-(RPI_PINS101-200-Pad29)") (class "Default")
      (node (ref "RPI_PINS101-200") (pin "29") (pinfunction "29_29") (pintype "bidirectional"))
    )
    (net (code "243") (name "unconnected-(RPI_PINS101-200-Pad30)") (class "Default")
      (node (ref "RPI_PINS101-200") (pin "30") (pinfunction "30_30") (pintype "bidirectional"))
    )
    (net (code "244") (name "unconnected-(RPI_PINS101-200-Pad33)") (class "Default")
      (node (ref "RPI_PINS101-200") (pin "33") (pinfunction "33_33") (pintype "bidirectional"))
    )
    (net (code "245") (name "unconnected-(RPI_PINS101-200-Pad34)") (class "Default")
      (node (ref "RPI_PINS101-200") (pin "34") (pinfunction "34_34") (pintype "bidirectional"))
    )
    (net (code "246") (name "unconnected-(RPI_PINS101-200-Pad35)") (class "Default")
      (node (ref "RPI_PINS101-200") (pin "35") (pinfunction "35_35") (pintype "bidirectional"))
    )
    (net (code "247") (name "unconnected-(RPI_PINS101-200-Pad36)") (class "Default")
      (node (ref "RPI_PINS101-200") (pin "36") (pinfunction "36_36") (pintype "bidirectional"))
    )
    (net (code "248") (name "unconnected-(RPI_PINS101-200-Pad39)") (class "Default")
      (node (ref "RPI_PINS101-200") (pin "39") (pinfunction "39_39") (pintype "bidirectional"))
    )
    (net (code "249") (name "unconnected-(RPI_PINS101-200-Pad40)") (class "Default")
      (node (ref "RPI_PINS101-200") (pin "40") (pinfunction "40_40") (pintype "bidirectional"))
    )
    (net (code "250") (name "unconnected-(RPI_PINS101-200-Pad41)") (class "Default")
      (node (ref "RPI_PINS101-200") (pin "41") (pinfunction "41_41") (pintype "bidirectional"))
    )
    (net (code "251") (name "unconnected-(RPI_PINS101-200-Pad42)") (class "Default")
      (node (ref "RPI_PINS101-200") (pin "42") (pinfunction "42_42") (pintype "bidirectional"))
    )
    (net (code "252") (name "unconnected-(RPI_PINS101-200-Pad43)") (class "Default")
      (node (ref "RPI_PINS101-200") (pin "43") (pinfunction "43_43") (pintype "bidirectional"))
    )
    (net (code "253") (name "unconnected-(RPI_PINS101-200-Pad45)") (class "Default")
      (node (ref "RPI_PINS101-200") (pin "45") (pinfunction "45_45") (pintype "bidirectional"))
    )
    (net (code "254") (name "unconnected-(RPI_PINS101-200-Pad46)") (class "Default")
      (node (ref "RPI_PINS101-200") (pin "46") (pinfunction "46_46") (pintype "bidirectional"))
    )
    (net (code "255") (name "unconnected-(RPI_PINS101-200-Pad47)") (class "Default")
      (node (ref "RPI_PINS101-200") (pin "47") (pinfunction "47_47") (pintype "bidirectional"))
    )
    (net (code "256") (name "unconnected-(RPI_PINS101-200-Pad48)") (class "Default")
      (node (ref "RPI_PINS101-200") (pin "48") (pinfunction "48_48") (pintype "bidirectional"))
    )
    (net (code "257") (name "unconnected-(RPI_PINS101-200-Pad49)") (class "Default")
      (node (ref "RPI_PINS101-200") (pin "49") (pinfunction "49_49") (pintype "bidirectional"))
    )
    (net (code "258") (name "unconnected-(RPI_PINS101-200-Pad52)") (class "Default")
      (node (ref "RPI_PINS101-200") (pin "52") (pinfunction "52_52") (pintype "bidirectional"))
    )
    (net (code "259") (name "unconnected-(RPI_PINS101-200-Pad54)") (class "Default")
      (node (ref "RPI_PINS101-200") (pin "54") (pinfunction "54_54") (pintype "bidirectional"))
    )
    (net (code "260") (name "unconnected-(RPI_PINS101-200-Pad57)") (class "Default")
      (node (ref "RPI_PINS101-200") (pin "57") (pinfunction "57_57") (pintype "bidirectional"))
    )
    (net (code "261") (name "unconnected-(RPI_PINS101-200-Pad58)") (class "Default")
      (node (ref "RPI_PINS101-200") (pin "58") (pinfunction "58_58") (pintype "bidirectional"))
    )
    (net (code "262") (name "unconnected-(RPI_PINS101-200-Pad59)") (class "Default")
      (node (ref "RPI_PINS101-200") (pin "59") (pinfunction "59_59") (pintype "bidirectional"))
    )
    (net (code "263") (name "unconnected-(RPI_PINS101-200-Pad60)") (class "Default")
      (node (ref "RPI_PINS101-200") (pin "60") (pinfunction "60_60") (pintype "bidirectional"))
    )
    (net (code "264") (name "unconnected-(RPI_PINS101-200-Pad63)") (class "Default")
      (node (ref "RPI_PINS101-200") (pin "63") (pinfunction "63_63") (pintype "bidirectional"))
    )
    (net (code "265") (name "unconnected-(RPI_PINS101-200-Pad64)") (class "Default")
      (node (ref "RPI_PINS101-200") (pin "64") (pinfunction "64_64") (pintype "bidirectional"))
    )
    (net (code "266") (name "unconnected-(RPI_PINS101-200-Pad65)") (class "Default")
      (node (ref "RPI_PINS101-200") (pin "65") (pinfunction "65_65") (pintype "bidirectional"))
    )
    (net (code "267") (name "unconnected-(RPI_PINS101-200-Pad66)") (class "Default")
      (node (ref "RPI_PINS101-200") (pin "66") (pinfunction "66_66") (pintype "bidirectional"))
    )
    (net (code "268") (name "unconnected-(RPI_PINS101-200-Pad69)") (class "Default")
      (node (ref "RPI_PINS101-200") (pin "69") (pinfunction "69_69") (pintype "bidirectional"))
    )
    (net (code "269") (name "unconnected-(RPI_PINS101-200-Pad71)") (class "Default")
      (node (ref "RPI_PINS101-200") (pin "71") (pinfunction "71_71") (pintype "bidirectional"))
    )
    (net (code "270") (name "unconnected-(RPI_PINS101-200-Pad93)") (class "Default")
      (node (ref "RPI_PINS101-200") (pin "93") (pinfunction "93_93") (pintype "bidirectional"))
    )
    (net (code "271") (name "unconnected-(RPI_PINS101-200-Pad94)") (class "Default")
      (node (ref "RPI_PINS101-200") (pin "94") (pinfunction "94_94") (pintype "bidirectional"))
    )
    (net (code "272") (name "unconnected-(RPI_PINS101-200-Pad95)") (class "Default")
      (node (ref "RPI_PINS101-200") (pin "95") (pinfunction "95_95") (pintype "bidirectional"))
    )
    (net (code "273") (name "unconnected-(RPI_PINS101-200-Pad96)") (class "Default")
      (node (ref "RPI_PINS101-200") (pin "96") (pinfunction "96_96") (pintype "bidirectional"))
    )
    (net (code "274") (name "unconnected-(TEENSY-0{slash}RX1{slash}T{slash}MOSI1-Pad0)") (class "Default")
      (node (ref "TEENSY") (pin "0") (pinfunction "0/RX1/T/MOSI1_0") (pintype "bidirectional"))
    )
    (net (code "275") (name "unconnected-(TEENSY-13{slash}SCK{slash}LED-Pad13)") (class "Default")
      (node (ref "TEENSY") (pin "13") (pinfunction "13/SCK/LED_13") (pintype "bidirectional"))
    )
    (net (code "276") (name "unconnected-(USB_HUB-Pad8)") (class "Default")
      (node (ref "USB_HUB") (pin "8") (pinfunction "8_8") (pintype "bidirectional"))
    )
    (net (code "277") (name "unconnected-(USB_HUB-Pad9)") (class "Default")
      (node (ref "USB_HUB") (pin "9") (pinfunction "9_9") (pintype "bidirectional"))
    )
    (net (code "278") (name "unconnected-(USB_HUB-Pad11)") (class "Default")
      (node (ref "USB_HUB") (pin "11") (pinfunction "11_11") (pintype "no_connect"))
    )
    (net (code "279") (name "unconnected-(USB_HUB-Pad14)") (class "Default")
      (node (ref "USB_HUB") (pin "14") (pinfunction "14_14") (pintype "no_connect"))
    )
    (net (code "280") (name "unconnected-(USB_HUB-Pad16)") (class "Default")
      (node (ref "USB_HUB") (pin "16") (pinfunction "16_16") (pintype "bidirectional"))
    )
    (net (code "281") (name "unconnected-(USB_HUB-Pad18)") (class "Default")
      (node (ref "USB_HUB") (pin "18") (pinfunction "18_18") (pintype "bidirectional"))
    )
    (net (code "282") (name "unconnected-(USB_HUB-Pad20)") (class "Default")
      (node (ref "USB_HUB") (pin "20") (pinfunction "20_20") (pintype "bidirectional"))
    )
    (net (code "283") (name "unconnected-(USB_HUB-Pad34)") (class "Default")
      (node (ref "USB_HUB") (pin "34") (pinfunction "34_34") (pintype "no_connect"))
    )
    (net (code "284") (name "unconnected-(USB_IN-PadNC)") (class "Default")
      (node (ref "USB_IN") (pin "NC") (pinfunction "NC_NC") (pintype "no_connect"))
    )
    (net (code "285") (name "unconnected-(USB_POE-NC-PadNC_1)") (class "Default")
      (node (ref "USB_POE") (pin "NC_1") (pinfunction "NC_NC_1") (pintype "no_connect"))
    )
    (net (code "286") (name "unconnected-(USB_POE-NC-PadNC_2)") (class "Default")
      (node (ref "USB_POE") (pin "NC_2") (pinfunction "NC_NC_2") (pintype "no_connect"))
    )
    (net (code "287") (name "unconnected-(USB_POE-NC-PadNC_3)") (class "Default")
      (node (ref "USB_POE") (pin "NC_3") (pinfunction "NC_NC_3") (pintype "no_connect"))
    )
    (net (code "288") (name "unconnected-(USB_POE-NC-PadNC_4)") (class "Default")
      (node (ref "USB_POE") (pin "NC_4") (pinfunction "NC_NC_4") (pintype "no_connect"))
    )
    (net (code "289") (name "unconnected-(USB_POE-PadD1+)") (class "Default")
      (node (ref "USB_POE") (pin "D1+") (pinfunction "D1+_D1+") (pintype "bidirectional"))
    )
    (net (code "290") (name "unconnected-(USB_POE-PadD1-)") (class "Default")
      (node (ref "USB_POE") (pin "D1-") (pinfunction "D1-_D1-") (pintype "bidirectional"))
    )
    (net (code "291") (name "unconnected-(USB_PWR-PadCC1)") (class "Default")
      (node (ref "USB_PWR") (pin "CC1") (pinfunction "CC1_CC1") (pintype "bidirectional"))
    )
    (net (code "292") (name "unconnected-(USB_PWR-PadCC2)") (class "Default")
      (node (ref "USB_PWR") (pin "CC2") (pinfunction "CC2_CC2") (pintype "bidirectional"))
    )
    (net (code "293") (name "unconnected-(USB_PWR-PadRX1+)") (class "Default")
      (node (ref "USB_PWR") (pin "RX1+") (pinfunction "RX1+_RX1+") (pintype "bidirectional"))
    )
    (net (code "294") (name "unconnected-(USB_PWR-PadRX1-)") (class "Default")
      (node (ref "USB_PWR") (pin "RX1-") (pinfunction "RX1-_RX1-") (pintype "bidirectional"))
    )
    (net (code "295") (name "unconnected-(USB_PWR-PadRX2+)") (class "Default")
      (node (ref "USB_PWR") (pin "RX2+") (pinfunction "RX2+_RX2+") (pintype "bidirectional"))
    )
    (net (code "296") (name "unconnected-(USB_PWR-PadRX2-)") (class "Default")
      (node (ref "USB_PWR") (pin "RX2-") (pinfunction "RX2-_RX2-") (pintype "bidirectional"))
    )
    (net (code "297") (name "unconnected-(USB_PWR-PadSBU1)") (class "Default")
      (node (ref "USB_PWR") (pin "SBU1") (pinfunction "SBU1_SBU1") (pintype "bidirectional"))
    )
    (net (code "298") (name "unconnected-(USB_PWR-PadSBU2)") (class "Default")
      (node (ref "USB_PWR") (pin "SBU2") (pinfunction "SBU2_SBU2") (pintype "bidirectional"))
    )
    (net (code "299") (name "unconnected-(USB_PWR-PadTX1+)") (class "Default")
      (node (ref "USB_PWR") (pin "TX1+") (pinfunction "TX1+_TX1+") (pintype "bidirectional"))
    )
    (net (code "300") (name "unconnected-(USB_PWR-PadTX1-)") (class "Default")
      (node (ref "USB_PWR") (pin "TX1-") (pinfunction "TX1-_TX1-") (pintype "bidirectional"))
    )
    (net (code "301") (name "unconnected-(USB_PWR-PadTX2+)") (class "Default")
      (node (ref "USB_PWR") (pin "TX2+") (pinfunction "TX2+_TX2+") (pintype "bidirectional"))
    )
    (net (code "302") (name "unconnected-(USB_PWR-PadTX2-)") (class "Default")
      (node (ref "USB_PWR") (pin "TX2-") (pinfunction "TX2-_TX2-") (pintype "bidirectional"))
    )
    (net (code "303") (name "unconnected-(WIFI/BT-Pad2)") (class "Default")
      (node (ref "WIFI/BT") (pin "2") (pinfunction "2_2") (pintype "bidirectional"))
    )
    (net (code "304") (name "unconnected-(WIFI/BT-Pad3)") (class "Default")
      (node (ref "WIFI/BT") (pin "3") (pinfunction "3_3") (pintype "bidirectional"))
    )
    (net (code "305") (name "unconnected-(WIFI/BT-Pad6)") (class "Default")
      (node (ref "WIFI/BT") (pin "6") (pinfunction "6_6") (pintype "bidirectional"))
    )
    (net (code "306") (name "unconnected-(WIFI/BT-Pad19)") (class "Default")
      (node (ref "WIFI/BT") (pin "19") (pinfunction "19_19") (pintype "bidirectional"))
    )
    (net (code "307") (name "unconnected-(WIFI/BT-Pad20)") (class "Default")
      (node (ref "WIFI/BT") (pin "20") (pinfunction "20_20") (pintype "bidirectional"))
    )
    (net (code "308") (name "unconnected-(WIFI/BT-Pad21)") (class "Default")
      (node (ref "WIFI/BT") (pin "21") (pinfunction "21_21") (pintype "bidirectional"))
    )
    (net (code "309") (name "unconnected-(WIFI/BT-Pad22)") (class "Default")
      (node (ref "WIFI/BT") (pin "22") (pinfunction "22_22") (pintype "bidirectional"))
    )
    (net (code "310") (name "unconnected-(WIFI/BT-Pad23)") (class "Default")
      (node (ref "WIFI/BT") (pin "23") (pinfunction "23_23") (pintype "bidirectional"))
    )
    (net (code "311") (name "unconnected-(WIFI/BT-Pad24)") (class "Default")
      (node (ref "WIFI/BT") (pin "24") (pinfunction "24_24") (pintype "bidirectional"))
    )
    (net (code "312") (name "unconnected-(WIFI/BT-Pad25)") (class "Default")
      (node (ref "WIFI/BT") (pin "25") (pinfunction "25_25") (pintype "bidirectional"))
    )
    (net (code "313") (name "unconnected-(WIFI/BT-Pad26)") (class "Default")
      (node (ref "WIFI/BT") (pin "26") (pinfunction "26_26") (pintype "bidirectional"))
    )
    (net (code "314") (name "unconnected-(WIFI/BT-Pad31)") (class "Default")
      (node (ref "WIFI/BT") (pin "31") (pinfunction "31_31") (pintype "bidirectional"))
    )
    (net (code "315") (name "unconnected-(WIFI/BT-Pad36)") (class "Default")
      (node (ref "WIFI/BT") (pin "36") (pinfunction "36_36") (pintype "bidirectional"))
    )
    (net (code "316") (name "unconnected-(WIFI/BT-Pad37)") (class "Default")
      (node (ref "WIFI/BT") (pin "37") (pinfunction "37_37") (pintype "bidirectional"))
    )
    (net (code "317") (name "unconnected-(WIFI/BT-Pad38)") (class "Default")
      (node (ref "WIFI/BT") (pin "38") (pinfunction "38_38") (pintype "bidirectional"))
    )
    (net (code "318") (name "unconnected-(WIFI/BT-Pad39)") (class "Default")
      (node (ref "WIFI/BT") (pin "39") (pinfunction "39_39") (pintype "bidirectional"))
    )
    (net (code "319") (name "unconnected-(WIFI/BT-Pad40)") (class "Default")
      (node (ref "WIFI/BT") (pin "40") (pinfunction "40_40") (pintype "bidirectional"))
    )
    (net (code "320") (name "unconnected-(WIFI/BT-Pad41)") (class "Default")
      (node (ref "WIFI/BT") (pin "41") (pinfunction "41_41") (pintype "bidirectional"))
    )
    (net (code "321") (name "unconnected-(WIFI/BT-Pad47)") (class "Default")
      (node (ref "WIFI/BT") (pin "47") (pinfunction "47_47") (pintype "bidirectional"))
    )
    (net (code "322") (name "unconnected-(WIFI/BT-Pad50)") (class "Default")
      (node (ref "WIFI/BT") (pin "50") (pinfunction "50_50") (pintype "bidirectional"))
    )
  )
)
